# Grid.net
KiCad netlist of a schematic drawn in EAGLE
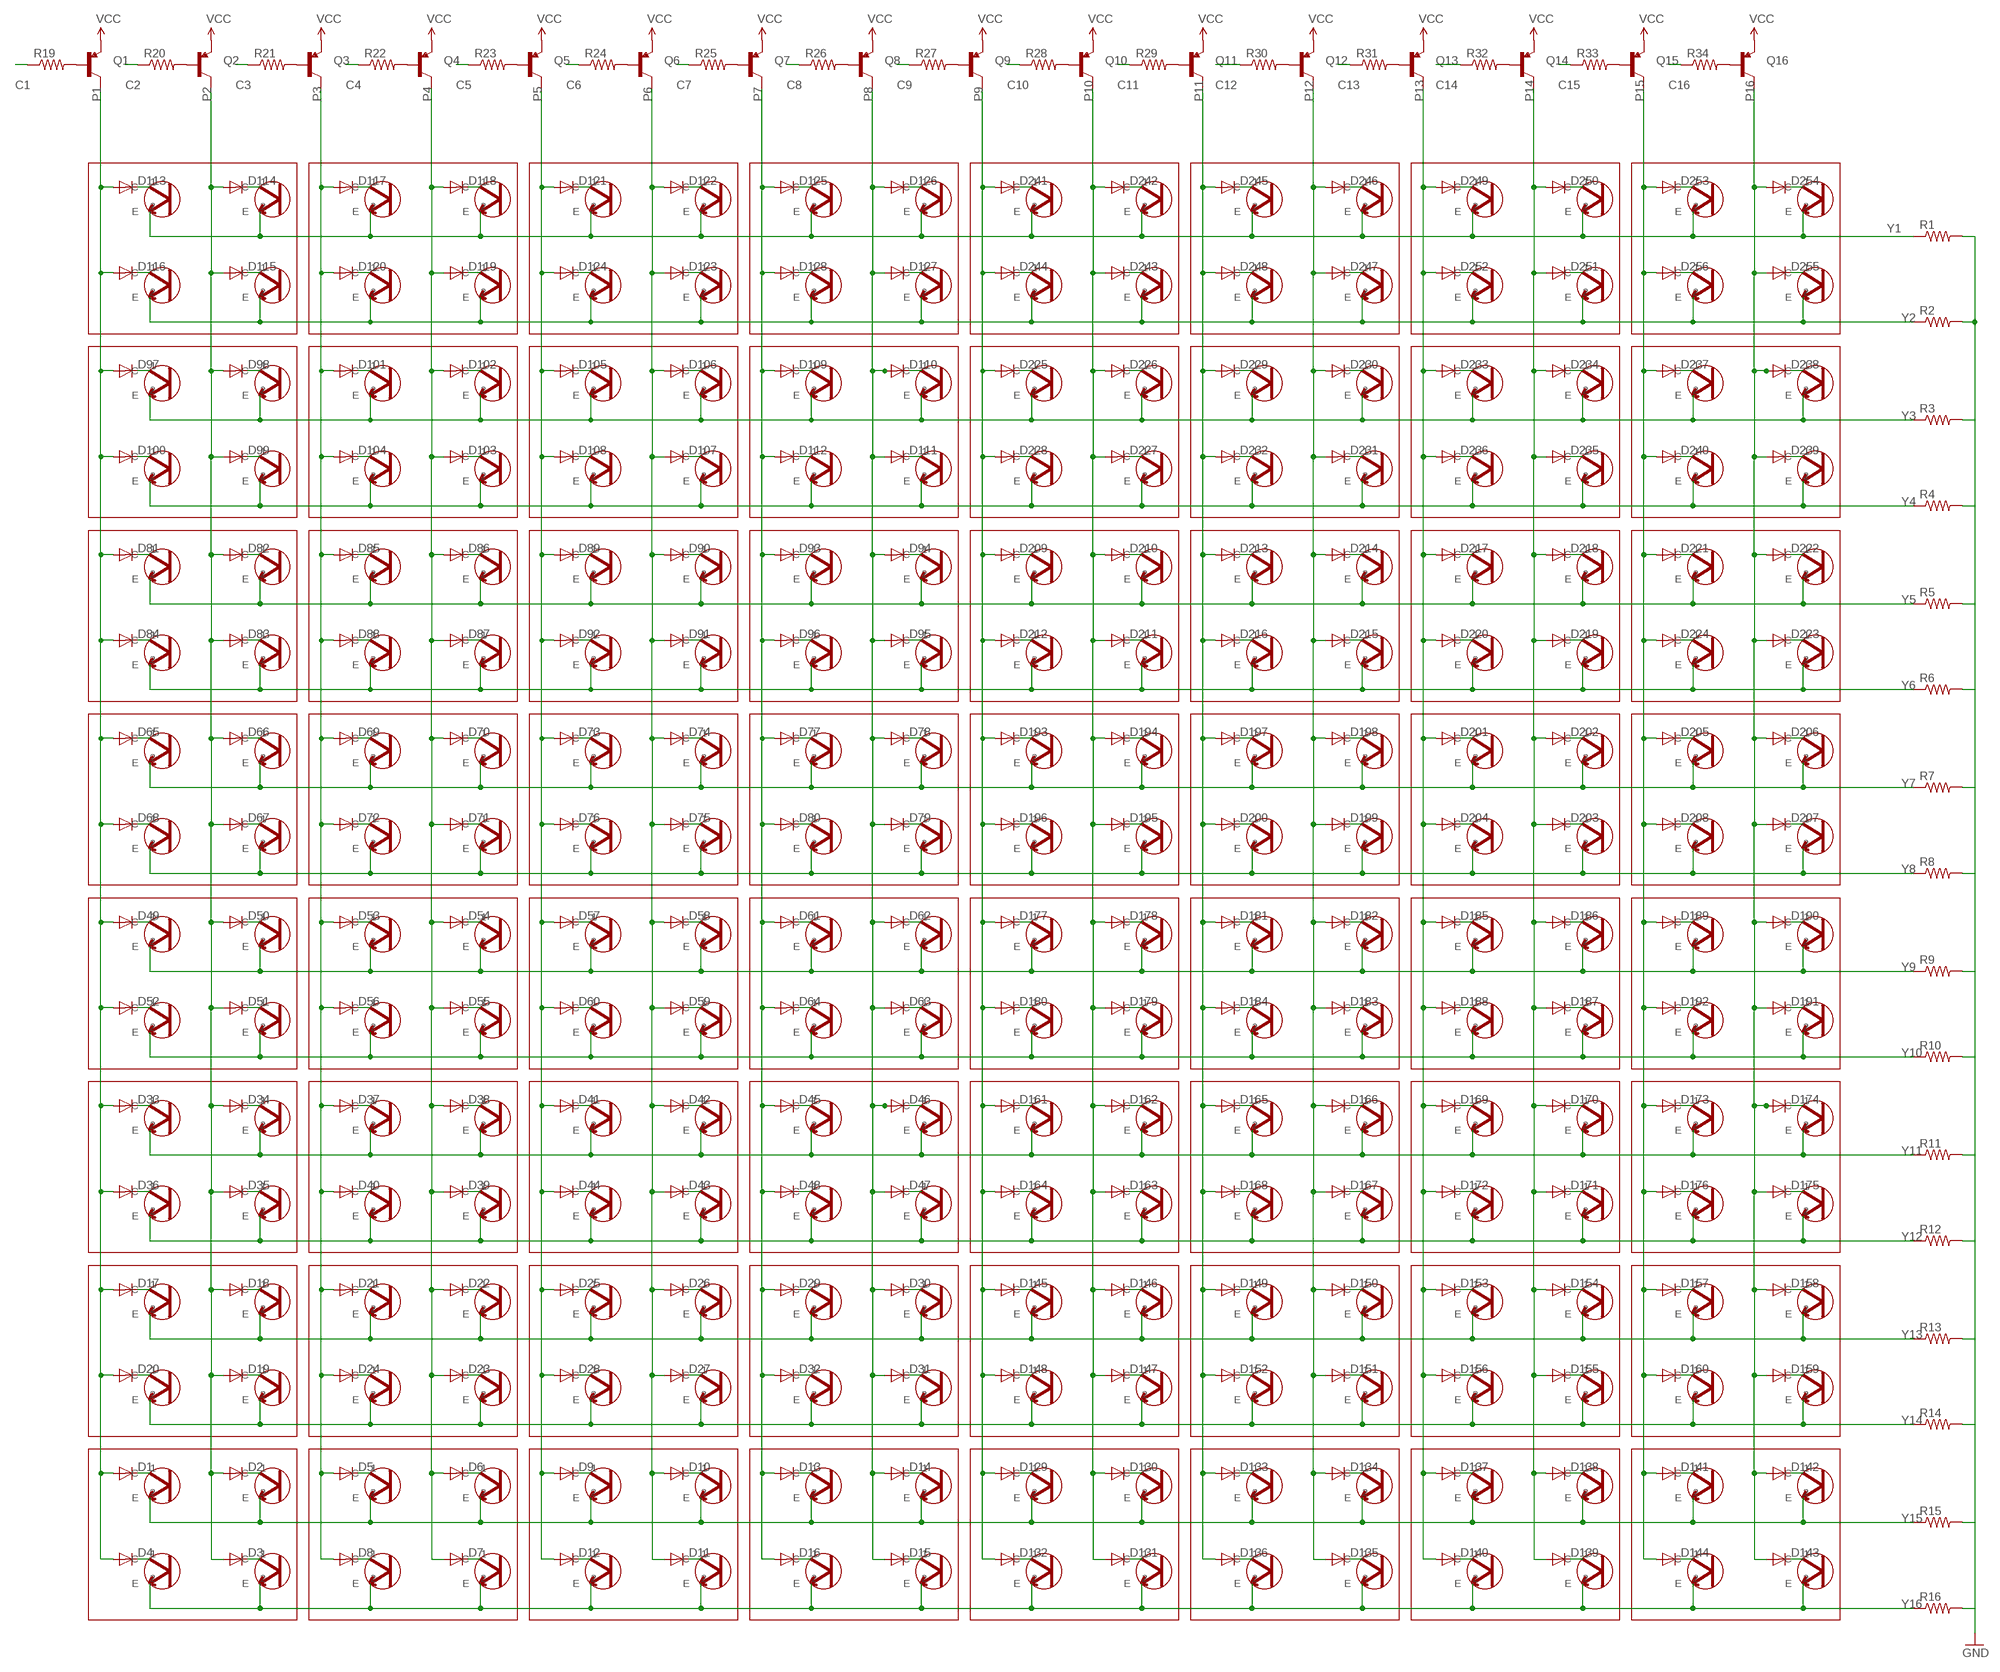
[diagram p0: schematic, sheet 1, part 1 of 2]
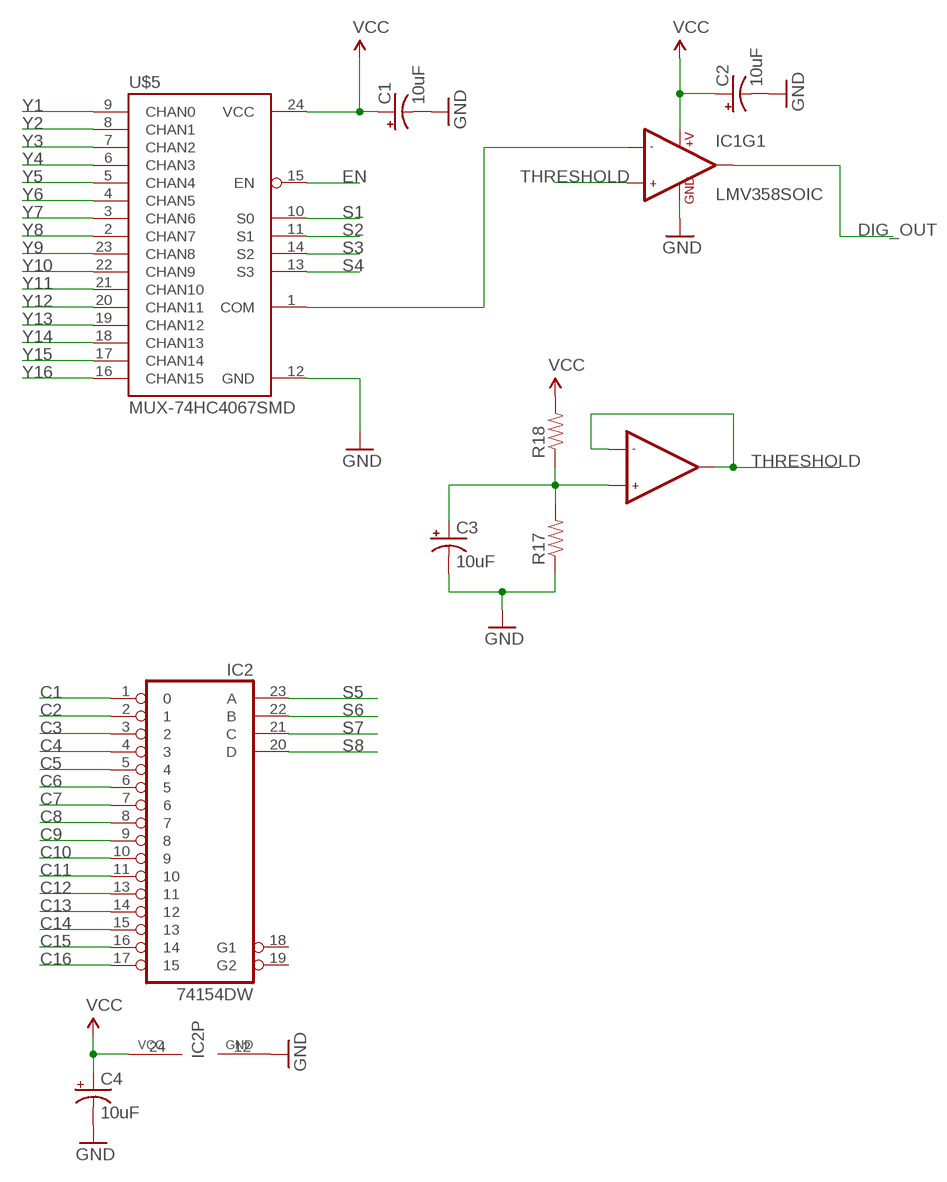
[diagram p1: schematic, sheet 1, part 2 of 2]

(export (version "E")
  (design (tool "Eeschema 10.0.6"))
  (components
    (comp (ref "C1")
      (value "10uF")
      (footprint "eagle-import:EIA3216")
      (libsource (lib "eagle-import") (part "CAP_POL1206"))
    )
    (comp (ref "C2")
      (value "10uF")
      (footprint "eagle-import:EIA3216")
      (libsource (lib "eagle-import") (part "CAP_POL1206"))
    )
    (comp (ref "C3")
      (value "10uF")
      (footprint "eagle-import:EIA3216")
      (libsource (lib "eagle-import") (part "CAP_POL1206"))
    )
    (comp (ref "C4")
      (value "10uF")
      (footprint "eagle-import:EIA3216")
      (libsource (lib "eagle-import") (part "CAP_POL1206"))
    )
    (comp (ref "D1")
      (value "DIODESOD")
      (footprint "eagle-import:SOD-323")
      (libsource (lib "eagle-import") (part "DIODESOD"))
    )
    (comp (ref "D2")
      (value "DIODESOD")
      (footprint "eagle-import:SOD-323")
      (libsource (lib "eagle-import") (part "DIODESOD"))
    )
    (comp (ref "D3")
      (value "DIODESOD")
      (footprint "eagle-import:SOD-323")
      (libsource (lib "eagle-import") (part "DIODESOD"))
    )
    (comp (ref "D4")
      (value "DIODESOD")
      (footprint "eagle-import:SOD-323")
      (libsource (lib "eagle-import") (part "DIODESOD"))
    )
    (comp (ref "D5")
      (value "DIODESOD")
      (footprint "eagle-import:SOD-323")
      (libsource (lib "eagle-import") (part "DIODESOD"))
    )
    (comp (ref "D6")
      (value "DIODESOD")
      (footprint "eagle-import:SOD-323")
      (libsource (lib "eagle-import") (part "DIODESOD"))
    )
    (comp (ref "D7")
      (value "DIODESOD")
      (footprint "eagle-import:SOD-323")
      (libsource (lib "eagle-import") (part "DIODESOD"))
    )
    (comp (ref "D8")
      (value "DIODESOD")
      (footprint "eagle-import:SOD-323")
      (libsource (lib "eagle-import") (part "DIODESOD"))
    )
    (comp (ref "D9")
      (value "DIODESOD")
      (footprint "eagle-import:SOD-323")
      (libsource (lib "eagle-import") (part "DIODESOD"))
    )
    (comp (ref "D10")
      (value "DIODESOD")
      (footprint "eagle-import:SOD-323")
      (libsource (lib "eagle-import") (part "DIODESOD"))
    )
    (comp (ref "D11")
      (value "DIODESOD")
      (footprint "eagle-import:SOD-323")
      (libsource (lib "eagle-import") (part "DIODESOD"))
    )
    (comp (ref "D12")
      (value "DIODESOD")
      (footprint "eagle-import:SOD-323")
      (libsource (lib "eagle-import") (part "DIODESOD"))
    )
    (comp (ref "D13")
      (value "DIODESOD")
      (footprint "eagle-import:SOD-323")
      (libsource (lib "eagle-import") (part "DIODESOD"))
    )
    (comp (ref "D14")
      (value "DIODESOD")
      (footprint "eagle-import:SOD-323")
      (libsource (lib "eagle-import") (part "DIODESOD"))
    )
    (comp (ref "D15")
      (value "DIODESOD")
      (footprint "eagle-import:SOD-323")
      (libsource (lib "eagle-import") (part "DIODESOD"))
    )
    (comp (ref "D16")
      (value "DIODESOD")
      (footprint "eagle-import:SOD-323")
      (libsource (lib "eagle-import") (part "DIODESOD"))
    )
    (comp (ref "D17")
      (value "DIODESOD")
      (footprint "eagle-import:SOD-323")
      (libsource (lib "eagle-import") (part "DIODESOD"))
    )
    (comp (ref "D18")
      (value "DIODESOD")
      (footprint "eagle-import:SOD-323")
      (libsource (lib "eagle-import") (part "DIODESOD"))
    )
    (comp (ref "D19")
      (value "DIODESOD")
      (footprint "eagle-import:SOD-323")
      (libsource (lib "eagle-import") (part "DIODESOD"))
    )
    (comp (ref "D20")
      (value "DIODESOD")
      (footprint "eagle-import:SOD-323")
      (libsource (lib "eagle-import") (part "DIODESOD"))
    )
    (comp (ref "D21")
      (value "DIODESOD")
      (footprint "eagle-import:SOD-323")
      (libsource (lib "eagle-import") (part "DIODESOD"))
    )
    (comp (ref "D22")
      (value "DIODESOD")
      (footprint "eagle-import:SOD-323")
      (libsource (lib "eagle-import") (part "DIODESOD"))
    )
    (comp (ref "D23")
      (value "DIODESOD")
      (footprint "eagle-import:SOD-323")
      (libsource (lib "eagle-import") (part "DIODESOD"))
    )
    (comp (ref "D24")
      (value "DIODESOD")
      (footprint "eagle-import:SOD-323")
      (libsource (lib "eagle-import") (part "DIODESOD"))
    )
    (comp (ref "D25")
      (value "DIODESOD")
      (footprint "eagle-import:SOD-323")
      (libsource (lib "eagle-import") (part "DIODESOD"))
    )
    (comp (ref "D26")
      (value "DIODESOD")
      (footprint "eagle-import:SOD-323")
      (libsource (lib "eagle-import") (part "DIODESOD"))
    )
    (comp (ref "D27")
      (value "DIODESOD")
      (footprint "eagle-import:SOD-323")
      (libsource (lib "eagle-import") (part "DIODESOD"))
    )
    (comp (ref "D28")
      (value "DIODESOD")
      (footprint "eagle-import:SOD-323")
      (libsource (lib "eagle-import") (part "DIODESOD"))
    )
    (comp (ref "D29")
      (value "DIODESOD")
      (footprint "eagle-import:SOD-323")
      (libsource (lib "eagle-import") (part "DIODESOD"))
    )
    (comp (ref "D30")
      (value "DIODESOD")
      (footprint "eagle-import:SOD-323")
      (libsource (lib "eagle-import") (part "DIODESOD"))
    )
    (comp (ref "D31")
      (value "DIODESOD")
      (footprint "eagle-import:SOD-323")
      (libsource (lib "eagle-import") (part "DIODESOD"))
    )
    (comp (ref "D32")
      (value "DIODESOD")
      (footprint "eagle-import:SOD-323")
      (libsource (lib "eagle-import") (part "DIODESOD"))
    )
    (comp (ref "D33")
      (value "DIODESOD")
      (footprint "eagle-import:SOD-323")
      (libsource (lib "eagle-import") (part "DIODESOD"))
    )
    (comp (ref "D34")
      (value "DIODESOD")
      (footprint "eagle-import:SOD-323")
      (libsource (lib "eagle-import") (part "DIODESOD"))
    )
    (comp (ref "D35")
      (value "DIODESOD")
      (footprint "eagle-import:SOD-323")
      (libsource (lib "eagle-import") (part "DIODESOD"))
    )
    (comp (ref "D36")
      (value "DIODESOD")
      (footprint "eagle-import:SOD-323")
      (libsource (lib "eagle-import") (part "DIODESOD"))
    )
    (comp (ref "D37")
      (value "DIODESOD")
      (footprint "eagle-import:SOD-323")
      (libsource (lib "eagle-import") (part "DIODESOD"))
    )
    (comp (ref "D38")
      (value "DIODESOD")
      (footprint "eagle-import:SOD-323")
      (libsource (lib "eagle-import") (part "DIODESOD"))
    )
    (comp (ref "D39")
      (value "DIODESOD")
      (footprint "eagle-import:SOD-323")
      (libsource (lib "eagle-import") (part "DIODESOD"))
    )
    (comp (ref "D40")
      (value "DIODESOD")
      (footprint "eagle-import:SOD-323")
      (libsource (lib "eagle-import") (part "DIODESOD"))
    )
    (comp (ref "D41")
      (value "DIODESOD")
      (footprint "eagle-import:SOD-323")
      (libsource (lib "eagle-import") (part "DIODESOD"))
    )
    (comp (ref "D42")
      (value "DIODESOD")
      (footprint "eagle-import:SOD-323")
      (libsource (lib "eagle-import") (part "DIODESOD"))
    )
    (comp (ref "D43")
      (value "DIODESOD")
      (footprint "eagle-import:SOD-323")
      (libsource (lib "eagle-import") (part "DIODESOD"))
    )
    (comp (ref "D44")
      (value "DIODESOD")
      (footprint "eagle-import:SOD-323")
      (libsource (lib "eagle-import") (part "DIODESOD"))
    )
    (comp (ref "D45")
      (value "DIODESOD")
      (footprint "eagle-import:SOD-323")
      (libsource (lib "eagle-import") (part "DIODESOD"))
    )
    (comp (ref "D46")
      (value "DIODESOD")
      (footprint "eagle-import:SOD-323")
      (libsource (lib "eagle-import") (part "DIODESOD"))
    )
    (comp (ref "D47")
      (value "DIODESOD")
      (footprint "eagle-import:SOD-323")
      (libsource (lib "eagle-import") (part "DIODESOD"))
    )
    (comp (ref "D48")
      (value "DIODESOD")
      (footprint "eagle-import:SOD-323")
      (libsource (lib "eagle-import") (part "DIODESOD"))
    )
    (comp (ref "D49")
      (value "DIODESOD")
      (footprint "eagle-import:SOD-323")
      (libsource (lib "eagle-import") (part "DIODESOD"))
    )
    (comp (ref "D50")
      (value "DIODESOD")
      (footprint "eagle-import:SOD-323")
      (libsource (lib "eagle-import") (part "DIODESOD"))
    )
    (comp (ref "D51")
      (value "DIODESOD")
      (footprint "eagle-import:SOD-323")
      (libsource (lib "eagle-import") (part "DIODESOD"))
    )
    (comp (ref "D52")
      (value "DIODESOD")
      (footprint "eagle-import:SOD-323")
      (libsource (lib "eagle-import") (part "DIODESOD"))
    )
    (comp (ref "D53")
      (value "DIODESOD")
      (footprint "eagle-import:SOD-323")
      (libsource (lib "eagle-import") (part "DIODESOD"))
    )
    (comp (ref "D54")
      (value "DIODESOD")
      (footprint "eagle-import:SOD-323")
      (libsource (lib "eagle-import") (part "DIODESOD"))
    )
    (comp (ref "D55")
      (value "DIODESOD")
      (footprint "eagle-import:SOD-323")
      (libsource (lib "eagle-import") (part "DIODESOD"))
    )
    (comp (ref "D56")
      (value "DIODESOD")
      (footprint "eagle-import:SOD-323")
      (libsource (lib "eagle-import") (part "DIODESOD"))
    )
    (comp (ref "D57")
      (value "DIODESOD")
      (footprint "eagle-import:SOD-323")
      (libsource (lib "eagle-import") (part "DIODESOD"))
    )
    (comp (ref "D58")
      (value "DIODESOD")
      (footprint "eagle-import:SOD-323")
      (libsource (lib "eagle-import") (part "DIODESOD"))
    )
    (comp (ref "D59")
      (value "DIODESOD")
      (footprint "eagle-import:SOD-323")
      (libsource (lib "eagle-import") (part "DIODESOD"))
    )
    (comp (ref "D60")
      (value "DIODESOD")
      (footprint "eagle-import:SOD-323")
      (libsource (lib "eagle-import") (part "DIODESOD"))
    )
    (comp (ref "D61")
      (value "DIODESOD")
      (footprint "eagle-import:SOD-323")
      (libsource (lib "eagle-import") (part "DIODESOD"))
    )
    (comp (ref "D62")
      (value "DIODESOD")
      (footprint "eagle-import:SOD-323")
      (libsource (lib "eagle-import") (part "DIODESOD"))
    )
    (comp (ref "D63")
      (value "DIODESOD")
      (footprint "eagle-import:SOD-323")
      (libsource (lib "eagle-import") (part "DIODESOD"))
    )
    (comp (ref "D64")
      (value "DIODESOD")
      (footprint "eagle-import:SOD-323")
      (libsource (lib "eagle-import") (part "DIODESOD"))
    )
    (comp (ref "D65")
      (value "DIODESOD")
      (footprint "eagle-import:SOD-323")
      (libsource (lib "eagle-import") (part "DIODESOD"))
    )
    (comp (ref "D66")
      (value "DIODESOD")
      (footprint "eagle-import:SOD-323")
      (libsource (lib "eagle-import") (part "DIODESOD"))
    )
    (comp (ref "D67")
      (value "DIODESOD")
      (footprint "eagle-import:SOD-323")
      (libsource (lib "eagle-import") (part "DIODESOD"))
    )
    (comp (ref "D68")
      (value "DIODESOD")
      (footprint "eagle-import:SOD-323")
      (libsource (lib "eagle-import") (part "DIODESOD"))
    )
    (comp (ref "D69")
      (value "DIODESOD")
      (footprint "eagle-import:SOD-323")
      (libsource (lib "eagle-import") (part "DIODESOD"))
    )
    (comp (ref "D70")
      (value "DIODESOD")
      (footprint "eagle-import:SOD-323")
      (libsource (lib "eagle-import") (part "DIODESOD"))
    )
    (comp (ref "D71")
      (value "DIODESOD")
      (footprint "eagle-import:SOD-323")
      (libsource (lib "eagle-import") (part "DIODESOD"))
    )
    (comp (ref "D72")
      (value "DIODESOD")
      (footprint "eagle-import:SOD-323")
      (libsource (lib "eagle-import") (part "DIODESOD"))
    )
    (comp (ref "D73")
      (value "DIODESOD")
      (footprint "eagle-import:SOD-323")
      (libsource (lib "eagle-import") (part "DIODESOD"))
    )
    (comp (ref "D74")
      (value "DIODESOD")
      (footprint "eagle-import:SOD-323")
      (libsource (lib "eagle-import") (part "DIODESOD"))
    )
    (comp (ref "D75")
      (value "DIODESOD")
      (footprint "eagle-import:SOD-323")
      (libsource (lib "eagle-import") (part "DIODESOD"))
    )
    (comp (ref "D76")
      (value "DIODESOD")
      (footprint "eagle-import:SOD-323")
      (libsource (lib "eagle-import") (part "DIODESOD"))
    )
    (comp (ref "D77")
      (value "DIODESOD")
      (footprint "eagle-import:SOD-323")
      (libsource (lib "eagle-import") (part "DIODESOD"))
    )
    (comp (ref "D78")
      (value "DIODESOD")
      (footprint "eagle-import:SOD-323")
      (libsource (lib "eagle-import") (part "DIODESOD"))
    )
    (comp (ref "D79")
      (value "DIODESOD")
      (footprint "eagle-import:SOD-323")
      (libsource (lib "eagle-import") (part "DIODESOD"))
    )
    (comp (ref "D80")
      (value "DIODESOD")
      (footprint "eagle-import:SOD-323")
      (libsource (lib "eagle-import") (part "DIODESOD"))
    )
    (comp (ref "D81")
      (value "DIODESOD")
      (footprint "eagle-import:SOD-323")
      (libsource (lib "eagle-import") (part "DIODESOD"))
    )
    (comp (ref "D82")
      (value "DIODESOD")
      (footprint "eagle-import:SOD-323")
      (libsource (lib "eagle-import") (part "DIODESOD"))
    )
    (comp (ref "D83")
      (value "DIODESOD")
      (footprint "eagle-import:SOD-323")
      (libsource (lib "eagle-import") (part "DIODESOD"))
    )
    (comp (ref "D84")
      (value "DIODESOD")
      (footprint "eagle-import:SOD-323")
      (libsource (lib "eagle-import") (part "DIODESOD"))
    )
    (comp (ref "D85")
      (value "DIODESOD")
      (footprint "eagle-import:SOD-323")
      (libsource (lib "eagle-import") (part "DIODESOD"))
    )
    (comp (ref "D86")
      (value "DIODESOD")
      (footprint "eagle-import:SOD-323")
      (libsource (lib "eagle-import") (part "DIODESOD"))
    )
    (comp (ref "D87")
      (value "DIODESOD")
      (footprint "eagle-import:SOD-323")
      (libsource (lib "eagle-import") (part "DIODESOD"))
    )
    (comp (ref "D88")
      (value "DIODESOD")
      (footprint "eagle-import:SOD-323")
      (libsource (lib "eagle-import") (part "DIODESOD"))
    )
    (comp (ref "D89")
      (value "DIODESOD")
      (footprint "eagle-import:SOD-323")
      (libsource (lib "eagle-import") (part "DIODESOD"))
    )
    (comp (ref "D90")
      (value "DIODESOD")
      (footprint "eagle-import:SOD-323")
      (libsource (lib "eagle-import") (part "DIODESOD"))
    )
    (comp (ref "D91")
      (value "DIODESOD")
      (footprint "eagle-import:SOD-323")
      (libsource (lib "eagle-import") (part "DIODESOD"))
    )
    (comp (ref "D92")
      (value "DIODESOD")
      (footprint "eagle-import:SOD-323")
      (libsource (lib "eagle-import") (part "DIODESOD"))
    )
    (comp (ref "D93")
      (value "DIODESOD")
      (footprint "eagle-import:SOD-323")
      (libsource (lib "eagle-import") (part "DIODESOD"))
    )
    (comp (ref "D94")
      (value "DIODESOD")
      (footprint "eagle-import:SOD-323")
      (libsource (lib "eagle-import") (part "DIODESOD"))
    )
    (comp (ref "D95")
      (value "DIODESOD")
      (footprint "eagle-import:SOD-323")
      (libsource (lib "eagle-import") (part "DIODESOD"))
    )
    (comp (ref "D96")
      (value "DIODESOD")
      (footprint "eagle-import:SOD-323")
      (libsource (lib "eagle-import") (part "DIODESOD"))
    )
    (comp (ref "D97")
      (value "DIODESOD")
      (footprint "eagle-import:SOD-323")
      (libsource (lib "eagle-import") (part "DIODESOD"))
    )
    (comp (ref "D98")
      (value "DIODESOD")
      (footprint "eagle-import:SOD-323")
      (libsource (lib "eagle-import") (part "DIODESOD"))
    )
    (comp (ref "D99")
      (value "DIODESOD")
      (footprint "eagle-import:SOD-323")
      (libsource (lib "eagle-import") (part "DIODESOD"))
    )
    (comp (ref "D100")
      (value "DIODESOD")
      (footprint "eagle-import:SOD-323")
      (libsource (lib "eagle-import") (part "DIODESOD"))
    )
    (comp (ref "D101")
      (value "DIODESOD")
      (footprint "eagle-import:SOD-323")
      (libsource (lib "eagle-import") (part "DIODESOD"))
    )
    (comp (ref "D102")
      (value "DIODESOD")
      (footprint "eagle-import:SOD-323")
      (libsource (lib "eagle-import") (part "DIODESOD"))
    )
    (comp (ref "D103")
      (value "DIODESOD")
      (footprint "eagle-import:SOD-323")
      (libsource (lib "eagle-import") (part "DIODESOD"))
    )
    (comp (ref "D104")
      (value "DIODESOD")
      (footprint "eagle-import:SOD-323")
      (libsource (lib "eagle-import") (part "DIODESOD"))
    )
    (comp (ref "D105")
      (value "DIODESOD")
      (footprint "eagle-import:SOD-323")
      (libsource (lib "eagle-import") (part "DIODESOD"))
    )
    (comp (ref "D106")
      (value "DIODESOD")
      (footprint "eagle-import:SOD-323")
      (libsource (lib "eagle-import") (part "DIODESOD"))
    )
    (comp (ref "D107")
      (value "DIODESOD")
      (footprint "eagle-import:SOD-323")
      (libsource (lib "eagle-import") (part "DIODESOD"))
    )
    (comp (ref "D108")
      (value "DIODESOD")
      (footprint "eagle-import:SOD-323")
      (libsource (lib "eagle-import") (part "DIODESOD"))
    )
    (comp (ref "D109")
      (value "DIODESOD")
      (footprint "eagle-import:SOD-323")
      (libsource (lib "eagle-import") (part "DIODESOD"))
    )
    (comp (ref "D110")
      (value "DIODESOD")
      (footprint "eagle-import:SOD-323")
      (libsource (lib "eagle-import") (part "DIODESOD"))
    )
    (comp (ref "D111")
      (value "DIODESOD")
      (footprint "eagle-import:SOD-323")
      (libsource (lib "eagle-import") (part "DIODESOD"))
    )
    (comp (ref "D112")
      (value "DIODESOD")
      (footprint "eagle-import:SOD-323")
      (libsource (lib "eagle-import") (part "DIODESOD"))
    )
    (comp (ref "D113")
      (value "DIODESOD")
      (footprint "eagle-import:SOD-323")
      (libsource (lib "eagle-import") (part "DIODESOD"))
    )
    (comp (ref "D114")
      (value "DIODESOD")
      (footprint "eagle-import:SOD-323")
      (libsource (lib "eagle-import") (part "DIODESOD"))
    )
    (comp (ref "D115")
      (value "DIODESOD")
      (footprint "eagle-import:SOD-323")
      (libsource (lib "eagle-import") (part "DIODESOD"))
    )
    (comp (ref "D116")
      (value "DIODESOD")
      (footprint "eagle-import:SOD-323")
      (libsource (lib "eagle-import") (part "DIODESOD"))
    )
    (comp (ref "D117")
      (value "DIODESOD")
      (footprint "eagle-import:SOD-323")
      (libsource (lib "eagle-import") (part "DIODESOD"))
    )
    (comp (ref "D118")
      (value "DIODESOD")
      (footprint "eagle-import:SOD-323")
      (libsource (lib "eagle-import") (part "DIODESOD"))
    )
    (comp (ref "D119")
      (value "DIODESOD")
      (footprint "eagle-import:SOD-323")
      (libsource (lib "eagle-import") (part "DIODESOD"))
    )
    (comp (ref "D120")
      (value "DIODESOD")
      (footprint "eagle-import:SOD-323")
      (libsource (lib "eagle-import") (part "DIODESOD"))
    )
    (comp (ref "D121")
      (value "DIODESOD")
      (footprint "eagle-import:SOD-323")
      (libsource (lib "eagle-import") (part "DIODESOD"))
    )
    (comp (ref "D122")
      (value "DIODESOD")
      (footprint "eagle-import:SOD-323")
      (libsource (lib "eagle-import") (part "DIODESOD"))
    )
    (comp (ref "D123")
      (value "DIODESOD")
      (footprint "eagle-import:SOD-323")
      (libsource (lib "eagle-import") (part "DIODESOD"))
    )
    (comp (ref "D124")
      (value "DIODESOD")
      (footprint "eagle-import:SOD-323")
      (libsource (lib "eagle-import") (part "DIODESOD"))
    )
    (comp (ref "D125")
      (value "DIODESOD")
      (footprint "eagle-import:SOD-323")
      (libsource (lib "eagle-import") (part "DIODESOD"))
    )
    (comp (ref "D126")
      (value "DIODESOD")
      (footprint "eagle-import:SOD-323")
      (libsource (lib "eagle-import") (part "DIODESOD"))
    )
    (comp (ref "D127")
      (value "DIODESOD")
      (footprint "eagle-import:SOD-323")
      (libsource (lib "eagle-import") (part "DIODESOD"))
    )
    (comp (ref "D128")
      (value "DIODESOD")
      (footprint "eagle-import:SOD-323")
      (libsource (lib "eagle-import") (part "DIODESOD"))
    )
    (comp (ref "D129")
      (value "DIODESOD")
      (footprint "eagle-import:SOD-323")
      (libsource (lib "eagle-import") (part "DIODESOD"))
    )
    (comp (ref "D130")
      (value "DIODESOD")
      (footprint "eagle-import:SOD-323")
      (libsource (lib "eagle-import") (part "DIODESOD"))
    )
    (comp (ref "D131")
      (value "DIODESOD")
      (footprint "eagle-import:SOD-323")
      (libsource (lib "eagle-import") (part "DIODESOD"))
    )
    (comp (ref "D132")
      (value "DIODESOD")
      (footprint "eagle-import:SOD-323")
      (libsource (lib "eagle-import") (part "DIODESOD"))
    )
    (comp (ref "D133")
      (value "DIODESOD")
      (footprint "eagle-import:SOD-323")
      (libsource (lib "eagle-import") (part "DIODESOD"))
    )
    (comp (ref "D134")
      (value "DIODESOD")
      (footprint "eagle-import:SOD-323")
      (libsource (lib "eagle-import") (part "DIODESOD"))
    )
    (comp (ref "D135")
      (value "DIODESOD")
      (footprint "eagle-import:SOD-323")
      (libsource (lib "eagle-import") (part "DIODESOD"))
    )
    (comp (ref "D136")
      (value "DIODESOD")
      (footprint "eagle-import:SOD-323")
      (libsource (lib "eagle-import") (part "DIODESOD"))
    )
    (comp (ref "D137")
      (value "DIODESOD")
      (footprint "eagle-import:SOD-323")
      (libsource (lib "eagle-import") (part "DIODESOD"))
    )
    (comp (ref "D138")
      (value "DIODESOD")
      (footprint "eagle-import:SOD-323")
      (libsource (lib "eagle-import") (part "DIODESOD"))
    )
    (comp (ref "D139")
      (value "DIODESOD")
      (footprint "eagle-import:SOD-323")
      (libsource (lib "eagle-import") (part "DIODESOD"))
    )
    (comp (ref "D140")
      (value "DIODESOD")
      (footprint "eagle-import:SOD-323")
      (libsource (lib "eagle-import") (part "DIODESOD"))
    )
    (comp (ref "D141")
      (value "DIODESOD")
      (footprint "eagle-import:SOD-323")
      (libsource (lib "eagle-import") (part "DIODESOD"))
    )
    (comp (ref "D142")
      (value "DIODESOD")
      (footprint "eagle-import:SOD-323")
      (libsource (lib "eagle-import") (part "DIODESOD"))
    )
    (comp (ref "D143")
      (value "DIODESOD")
      (footprint "eagle-import:SOD-323")
      (libsource (lib "eagle-import") (part "DIODESOD"))
    )
    (comp (ref "D144")
      (value "DIODESOD")
      (footprint "eagle-import:SOD-323")
      (libsource (lib "eagle-import") (part "DIODESOD"))
    )
    (comp (ref "D145")
      (value "DIODESOD")
      (footprint "eagle-import:SOD-323")
      (libsource (lib "eagle-import") (part "DIODESOD"))
    )
    (comp (ref "D146")
      (value "DIODESOD")
      (footprint "eagle-import:SOD-323")
      (libsource (lib "eagle-import") (part "DIODESOD"))
    )
    (comp (ref "D147")
      (value "DIODESOD")
      (footprint "eagle-import:SOD-323")
      (libsource (lib "eagle-import") (part "DIODESOD"))
    )
    (comp (ref "D148")
      (value "DIODESOD")
      (footprint "eagle-import:SOD-323")
      (libsource (lib "eagle-import") (part "DIODESOD"))
    )
    (comp (ref "D149")
      (value "DIODESOD")
      (footprint "eagle-import:SOD-323")
      (libsource (lib "eagle-import") (part "DIODESOD"))
    )
    (comp (ref "D150")
      (value "DIODESOD")
      (footprint "eagle-import:SOD-323")
      (libsource (lib "eagle-import") (part "DIODESOD"))
    )
    (comp (ref "D151")
      (value "DIODESOD")
      (footprint "eagle-import:SOD-323")
      (libsource (lib "eagle-import") (part "DIODESOD"))
    )
    (comp (ref "D152")
      (value "DIODESOD")
      (footprint "eagle-import:SOD-323")
      (libsource (lib "eagle-import") (part "DIODESOD"))
    )
    (comp (ref "D153")
      (value "DIODESOD")
      (footprint "eagle-import:SOD-323")
      (libsource (lib "eagle-import") (part "DIODESOD"))
    )
    (comp (ref "D154")
      (value "DIODESOD")
      (footprint "eagle-import:SOD-323")
      (libsource (lib "eagle-import") (part "DIODESOD"))
    )
    (comp (ref "D155")
      (value "DIODESOD")
      (footprint "eagle-import:SOD-323")
      (libsource (lib "eagle-import") (part "DIODESOD"))
    )
    (comp (ref "D156")
      (value "DIODESOD")
      (footprint "eagle-import:SOD-323")
      (libsource (lib "eagle-import") (part "DIODESOD"))
    )
    (comp (ref "D157")
      (value "DIODESOD")
      (footprint "eagle-import:SOD-323")
      (libsource (lib "eagle-import") (part "DIODESOD"))
    )
    (comp (ref "D158")
      (value "DIODESOD")
      (footprint "eagle-import:SOD-323")
      (libsource (lib "eagle-import") (part "DIODESOD"))
    )
    (comp (ref "D159")
      (value "DIODESOD")
      (footprint "eagle-import:SOD-323")
      (libsource (lib "eagle-import") (part "DIODESOD"))
    )
    (comp (ref "D160")
      (value "DIODESOD")
      (footprint "eagle-import:SOD-323")
      (libsource (lib "eagle-import") (part "DIODESOD"))
    )
    (comp (ref "D161")
      (value "DIODESOD")
      (footprint "eagle-import:SOD-323")
      (libsource (lib "eagle-import") (part "DIODESOD"))
    )
    (comp (ref "D162")
      (value "DIODESOD")
      (footprint "eagle-import:SOD-323")
      (libsource (lib "eagle-import") (part "DIODESOD"))
    )
    (comp (ref "D163")
      (value "DIODESOD")
      (footprint "eagle-import:SOD-323")
      (libsource (lib "eagle-import") (part "DIODESOD"))
    )
    (comp (ref "D164")
      (value "DIODESOD")
      (footprint "eagle-import:SOD-323")
      (libsource (lib "eagle-import") (part "DIODESOD"))
    )
    (comp (ref "D165")
      (value "DIODESOD")
      (footprint "eagle-import:SOD-323")
      (libsource (lib "eagle-import") (part "DIODESOD"))
    )
    (comp (ref "D166")
      (value "DIODESOD")
      (footprint "eagle-import:SOD-323")
      (libsource (lib "eagle-import") (part "DIODESOD"))
    )
    (comp (ref "D167")
      (value "DIODESOD")
      (footprint "eagle-import:SOD-323")
      (libsource (lib "eagle-import") (part "DIODESOD"))
    )
    (comp (ref "D168")
      (value "DIODESOD")
      (footprint "eagle-import:SOD-323")
      (libsource (lib "eagle-import") (part "DIODESOD"))
    )
    (comp (ref "D169")
      (value "DIODESOD")
      (footprint "eagle-import:SOD-323")
      (libsource (lib "eagle-import") (part "DIODESOD"))
    )
    (comp (ref "D170")
      (value "DIODESOD")
      (footprint "eagle-import:SOD-323")
      (libsource (lib "eagle-import") (part "DIODESOD"))
    )
    (comp (ref "D171")
      (value "DIODESOD")
      (footprint "eagle-import:SOD-323")
      (libsource (lib "eagle-import") (part "DIODESOD"))
    )
    (comp (ref "D172")
      (value "DIODESOD")
      (footprint "eagle-import:SOD-323")
      (libsource (lib "eagle-import") (part "DIODESOD"))
    )
    (comp (ref "D173")
      (value "DIODESOD")
      (footprint "eagle-import:SOD-323")
      (libsource (lib "eagle-import") (part "DIODESOD"))
    )
    (comp (ref "D174")
      (value "DIODESOD")
      (footprint "eagle-import:SOD-323")
      (libsource (lib "eagle-import") (part "DIODESOD"))
    )
    (comp (ref "D175")
      (value "DIODESOD")
      (footprint "eagle-import:SOD-323")
      (libsource (lib "eagle-import") (part "DIODESOD"))
    )
    (comp (ref "D176")
      (value "DIODESOD")
      (footprint "eagle-import:SOD-323")
      (libsource (lib "eagle-import") (part "DIODESOD"))
    )
    (comp (ref "D177")
      (value "DIODESOD")
      (footprint "eagle-import:SOD-323")
      (libsource (lib "eagle-import") (part "DIODESOD"))
    )
    (comp (ref "D178")
      (value "DIODESOD")
      (footprint "eagle-import:SOD-323")
      (libsource (lib "eagle-import") (part "DIODESOD"))
    )
    (comp (ref "D179")
      (value "DIODESOD")
      (footprint "eagle-import:SOD-323")
      (libsource (lib "eagle-import") (part "DIODESOD"))
    )
    (comp (ref "D180")
      (value "DIODESOD")
      (footprint "eagle-import:SOD-323")
      (libsource (lib "eagle-import") (part "DIODESOD"))
    )
    (comp (ref "D181")
      (value "DIODESOD")
      (footprint "eagle-import:SOD-323")
      (libsource (lib "eagle-import") (part "DIODESOD"))
    )
    (comp (ref "D182")
      (value "DIODESOD")
      (footprint "eagle-import:SOD-323")
      (libsource (lib "eagle-import") (part "DIODESOD"))
    )
    (comp (ref "D183")
      (value "DIODESOD")
      (footprint "eagle-import:SOD-323")
      (libsource (lib "eagle-import") (part "DIODESOD"))
    )
    (comp (ref "D184")
      (value "DIODESOD")
      (footprint "eagle-import:SOD-323")
      (libsource (lib "eagle-import") (part "DIODESOD"))
    )
    (comp (ref "D185")
      (value "DIODESOD")
      (footprint "eagle-import:SOD-323")
      (libsource (lib "eagle-import") (part "DIODESOD"))
    )
    (comp (ref "D186")
      (value "DIODESOD")
      (footprint "eagle-import:SOD-323")
      (libsource (lib "eagle-import") (part "DIODESOD"))
    )
    (comp (ref "D187")
      (value "DIODESOD")
      (footprint "eagle-import:SOD-323")
      (libsource (lib "eagle-import") (part "DIODESOD"))
    )
    (comp (ref "D188")
      (value "DIODESOD")
      (footprint "eagle-import:SOD-323")
      (libsource (lib "eagle-import") (part "DIODESOD"))
    )
    (comp (ref "D189")
      (value "DIODESOD")
      (footprint "eagle-import:SOD-323")
      (libsource (lib "eagle-import") (part "DIODESOD"))
    )
    (comp (ref "D190")
      (value "DIODESOD")
      (footprint "eagle-import:SOD-323")
      (libsource (lib "eagle-import") (part "DIODESOD"))
    )
    (comp (ref "D191")
      (value "DIODESOD")
      (footprint "eagle-import:SOD-323")
      (libsource (lib "eagle-import") (part "DIODESOD"))
    )
    (comp (ref "D192")
      (value "DIODESOD")
      (footprint "eagle-import:SOD-323")
      (libsource (lib "eagle-import") (part "DIODESOD"))
    )
    (comp (ref "D193")
      (value "DIODESOD")
      (footprint "eagle-import:SOD-323")
      (libsource (lib "eagle-import") (part "DIODESOD"))
    )
    (comp (ref "D194")
      (value "DIODESOD")
      (footprint "eagle-import:SOD-323")
      (libsource (lib "eagle-import") (part "DIODESOD"))
    )
    (comp (ref "D195")
      (value "DIODESOD")
      (footprint "eagle-import:SOD-323")
      (libsource (lib "eagle-import") (part "DIODESOD"))
    )
    (comp (ref "D196")
      (value "DIODESOD")
      (footprint "eagle-import:SOD-323")
      (libsource (lib "eagle-import") (part "DIODESOD"))
    )
    (comp (ref "D197")
      (value "DIODESOD")
      (footprint "eagle-import:SOD-323")
      (libsource (lib "eagle-import") (part "DIODESOD"))
    )
    (comp (ref "D198")
      (value "DIODESOD")
      (footprint "eagle-import:SOD-323")
      (libsource (lib "eagle-import") (part "DIODESOD"))
    )
    (comp (ref "D199")
      (value "DIODESOD")
      (footprint "eagle-import:SOD-323")
      (libsource (lib "eagle-import") (part "DIODESOD"))
    )
    (comp (ref "D200")
      (value "DIODESOD")
      (footprint "eagle-import:SOD-323")
      (libsource (lib "eagle-import") (part "DIODESOD"))
    )
    (comp (ref "D201")
      (value "DIODESOD")
      (footprint "eagle-import:SOD-323")
      (libsource (lib "eagle-import") (part "DIODESOD"))
    )
    (comp (ref "D202")
      (value "DIODESOD")
      (footprint "eagle-import:SOD-323")
      (libsource (lib "eagle-import") (part "DIODESOD"))
    )
    (comp (ref "D203")
      (value "DIODESOD")
      (footprint "eagle-import:SOD-323")
      (libsource (lib "eagle-import") (part "DIODESOD"))
    )
    (comp (ref "D204")
      (value "DIODESOD")
      (footprint "eagle-import:SOD-323")
      (libsource (lib "eagle-import") (part "DIODESOD"))
    )
    (comp (ref "D205")
      (value "DIODESOD")
      (footprint "eagle-import:SOD-323")
      (libsource (lib "eagle-import") (part "DIODESOD"))
    )
    (comp (ref "D206")
      (value "DIODESOD")
      (footprint "eagle-import:SOD-323")
      (libsource (lib "eagle-import") (part "DIODESOD"))
    )
    (comp (ref "D207")
      (value "DIODESOD")
      (footprint "eagle-import:SOD-323")
      (libsource (lib "eagle-import") (part "DIODESOD"))
    )
    (comp (ref "D208")
      (value "DIODESOD")
      (footprint "eagle-import:SOD-323")
      (libsource (lib "eagle-import") (part "DIODESOD"))
    )
    (comp (ref "D209")
      (value "DIODESOD")
      (footprint "eagle-import:SOD-323")
      (libsource (lib "eagle-import") (part "DIODESOD"))
    )
    (comp (ref "D210")
      (value "DIODESOD")
      (footprint "eagle-import:SOD-323")
      (libsource (lib "eagle-import") (part "DIODESOD"))
    )
    (comp (ref "D211")
      (value "DIODESOD")
      (footprint "eagle-import:SOD-323")
      (libsource (lib "eagle-import") (part "DIODESOD"))
    )
    (comp (ref "D212")
      (value "DIODESOD")
      (footprint "eagle-import:SOD-323")
      (libsource (lib "eagle-import") (part "DIODESOD"))
    )
    (comp (ref "D213")
      (value "DIODESOD")
      (footprint "eagle-import:SOD-323")
      (libsource (lib "eagle-import") (part "DIODESOD"))
    )
    (comp (ref "D214")
      (value "DIODESOD")
      (footprint "eagle-import:SOD-323")
      (libsource (lib "eagle-import") (part "DIODESOD"))
    )
    (comp (ref "D215")
      (value "DIODESOD")
      (footprint "eagle-import:SOD-323")
      (libsource (lib "eagle-import") (part "DIODESOD"))
    )
    (comp (ref "D216")
      (value "DIODESOD")
      (footprint "eagle-import:SOD-323")
      (libsource (lib "eagle-import") (part "DIODESOD"))
    )
    (comp (ref "D217")
      (value "DIODESOD")
      (footprint "eagle-import:SOD-323")
      (libsource (lib "eagle-import") (part "DIODESOD"))
    )
    (comp (ref "D218")
      (value "DIODESOD")
      (footprint "eagle-import:SOD-323")
      (libsource (lib "eagle-import") (part "DIODESOD"))
    )
    (comp (ref "D219")
      (value "DIODESOD")
      (footprint "eagle-import:SOD-323")
      (libsource (lib "eagle-import") (part "DIODESOD"))
    )
    (comp (ref "D220")
      (value "DIODESOD")
      (footprint "eagle-import:SOD-323")
      (libsource (lib "eagle-import") (part "DIODESOD"))
    )
    (comp (ref "D221")
      (value "DIODESOD")
      (footprint "eagle-import:SOD-323")
      (libsource (lib "eagle-import") (part "DIODESOD"))
    )
    (comp (ref "D222")
      (value "DIODESOD")
      (footprint "eagle-import:SOD-323")
      (libsource (lib "eagle-import") (part "DIODESOD"))
    )
    (comp (ref "D223")
      (value "DIODESOD")
      (footprint "eagle-import:SOD-323")
      (libsource (lib "eagle-import") (part "DIODESOD"))
    )
    (comp (ref "D224")
      (value "DIODESOD")
      (footprint "eagle-import:SOD-323")
      (libsource (lib "eagle-import") (part "DIODESOD"))
    )
    (comp (ref "D225")
      (value "DIODESOD")
      (footprint "eagle-import:SOD-323")
      (libsource (lib "eagle-import") (part "DIODESOD"))
    )
    (comp (ref "D226")
      (value "DIODESOD")
      (footprint "eagle-import:SOD-323")
      (libsource (lib "eagle-import") (part "DIODESOD"))
    )
    (comp (ref "D227")
      (value "DIODESOD")
      (footprint "eagle-import:SOD-323")
      (libsource (lib "eagle-import") (part "DIODESOD"))
    )
    (comp (ref "D228")
      (value "DIODESOD")
      (footprint "eagle-import:SOD-323")
      (libsource (lib "eagle-import") (part "DIODESOD"))
    )
    (comp (ref "D229")
      (value "DIODESOD")
      (footprint "eagle-import:SOD-323")
      (libsource (lib "eagle-import") (part "DIODESOD"))
    )
    (comp (ref "D230")
      (value "DIODESOD")
      (footprint "eagle-import:SOD-323")
      (libsource (lib "eagle-import") (part "DIODESOD"))
    )
    (comp (ref "D231")
      (value "DIODESOD")
      (footprint "eagle-import:SOD-323")
      (libsource (lib "eagle-import") (part "DIODESOD"))
    )
    (comp (ref "D232")
      (value "DIODESOD")
      (footprint "eagle-import:SOD-323")
      (libsource (lib "eagle-import") (part "DIODESOD"))
    )
    (comp (ref "D233")
      (value "DIODESOD")
      (footprint "eagle-import:SOD-323")
      (libsource (lib "eagle-import") (part "DIODESOD"))
    )
    (comp (ref "D234")
      (value "DIODESOD")
      (footprint "eagle-import:SOD-323")
      (libsource (lib "eagle-import") (part "DIODESOD"))
    )
    (comp (ref "D235")
      (value "DIODESOD")
      (footprint "eagle-import:SOD-323")
      (libsource (lib "eagle-import") (part "DIODESOD"))
    )
    (comp (ref "D236")
      (value "DIODESOD")
      (footprint "eagle-import:SOD-323")
      (libsource (lib "eagle-import") (part "DIODESOD"))
    )
    (comp (ref "D237")
      (value "DIODESOD")
      (footprint "eagle-import:SOD-323")
      (libsource (lib "eagle-import") (part "DIODESOD"))
    )
    (comp (ref "D238")
      (value "DIODESOD")
      (footprint "eagle-import:SOD-323")
      (libsource (lib "eagle-import") (part "DIODESOD"))
    )
    (comp (ref "D239")
      (value "DIODESOD")
      (footprint "eagle-import:SOD-323")
      (libsource (lib "eagle-import") (part "DIODESOD"))
    )
    (comp (ref "D240")
      (value "DIODESOD")
      (footprint "eagle-import:SOD-323")
      (libsource (lib "eagle-import") (part "DIODESOD"))
    )
    (comp (ref "D241")
      (value "DIODESOD")
      (footprint "eagle-import:SOD-323")
      (libsource (lib "eagle-import") (part "DIODESOD"))
    )
    (comp (ref "D242")
      (value "DIODESOD")
      (footprint "eagle-import:SOD-323")
      (libsource (lib "eagle-import") (part "DIODESOD"))
    )
    (comp (ref "D243")
      (value "DIODESOD")
      (footprint "eagle-import:SOD-323")
      (libsource (lib "eagle-import") (part "DIODESOD"))
    )
    (comp (ref "D244")
      (value "DIODESOD")
      (footprint "eagle-import:SOD-323")
      (libsource (lib "eagle-import") (part "DIODESOD"))
    )
    (comp (ref "D245")
      (value "DIODESOD")
      (footprint "eagle-import:SOD-323")
      (libsource (lib "eagle-import") (part "DIODESOD"))
    )
    (comp (ref "D246")
      (value "DIODESOD")
      (footprint "eagle-import:SOD-323")
      (libsource (lib "eagle-import") (part "DIODESOD"))
    )
    (comp (ref "D247")
      (value "DIODESOD")
      (footprint "eagle-import:SOD-323")
      (libsource (lib "eagle-import") (part "DIODESOD"))
    )
    (comp (ref "D248")
      (value "DIODESOD")
      (footprint "eagle-import:SOD-323")
      (libsource (lib "eagle-import") (part "DIODESOD"))
    )
    (comp (ref "D249")
      (value "DIODESOD")
      (footprint "eagle-import:SOD-323")
      (libsource (lib "eagle-import") (part "DIODESOD"))
    )
    (comp (ref "D250")
      (value "DIODESOD")
      (footprint "eagle-import:SOD-323")
      (libsource (lib "eagle-import") (part "DIODESOD"))
    )
    (comp (ref "D251")
      (value "DIODESOD")
      (footprint "eagle-import:SOD-323")
      (libsource (lib "eagle-import") (part "DIODESOD"))
    )
    (comp (ref "D252")
      (value "DIODESOD")
      (footprint "eagle-import:SOD-323")
      (libsource (lib "eagle-import") (part "DIODESOD"))
    )
    (comp (ref "D253")
      (value "DIODESOD")
      (footprint "eagle-import:SOD-323")
      (libsource (lib "eagle-import") (part "DIODESOD"))
    )
    (comp (ref "D254")
      (value "DIODESOD")
      (footprint "eagle-import:SOD-323")
      (libsource (lib "eagle-import") (part "DIODESOD"))
    )
    (comp (ref "D255")
      (value "DIODESOD")
      (footprint "eagle-import:SOD-323")
      (libsource (lib "eagle-import") (part "DIODESOD"))
    )
    (comp (ref "D256")
      (value "DIODESOD")
      (footprint "eagle-import:SOD-323")
      (libsource (lib "eagle-import") (part "DIODESOD"))
    )
    (comp (ref "IC1")
      (value "LMV358SOIC")
      (footprint "eagle-import:SO08")
      (libsource (lib "eagle-import") (part "LMV358SOIC"))
    )
    (comp (ref "IC2")
      (value "74154DW")
      (footprint "eagle-import:SO24W")
      (libsource (lib "eagle-import") (part "74154DW"))
    )
    (comp (ref "Q1")
      (value "TRANSISTOR_PNPSMD")
      (footprint "eagle-import:SOT23-3")
      (libsource (lib "eagle-import") (part "TRANSISTOR_PNPSMD"))
    )
    (comp (ref "Q2")
      (value "TRANSISTOR_PNPSMD")
      (footprint "eagle-import:SOT23-3")
      (libsource (lib "eagle-import") (part "TRANSISTOR_PNPSMD"))
    )
    (comp (ref "Q3")
      (value "TRANSISTOR_PNPSMD")
      (footprint "eagle-import:SOT23-3")
      (libsource (lib "eagle-import") (part "TRANSISTOR_PNPSMD"))
    )
    (comp (ref "Q4")
      (value "TRANSISTOR_PNPSMD")
      (footprint "eagle-import:SOT23-3")
      (libsource (lib "eagle-import") (part "TRANSISTOR_PNPSMD"))
    )
    (comp (ref "Q5")
      (value "TRANSISTOR_PNPSMD")
      (footprint "eagle-import:SOT23-3")
      (libsource (lib "eagle-import") (part "TRANSISTOR_PNPSMD"))
    )
    (comp (ref "Q6")
      (value "TRANSISTOR_PNPSMD")
      (footprint "eagle-import:SOT23-3")
      (libsource (lib "eagle-import") (part "TRANSISTOR_PNPSMD"))
    )
    (comp (ref "Q7")
      (value "TRANSISTOR_PNPSMD")
      (footprint "eagle-import:SOT23-3")
      (libsource (lib "eagle-import") (part "TRANSISTOR_PNPSMD"))
    )
    (comp (ref "Q8")
      (value "TRANSISTOR_PNPSMD")
      (footprint "eagle-import:SOT23-3")
      (libsource (lib "eagle-import") (part "TRANSISTOR_PNPSMD"))
    )
    (comp (ref "Q9")
      (value "TRANSISTOR_PNPSMD")
      (footprint "eagle-import:SOT23-3")
      (libsource (lib "eagle-import") (part "TRANSISTOR_PNPSMD"))
    )
    (comp (ref "Q10")
      (value "TRANSISTOR_PNPSMD")
      (footprint "eagle-import:SOT23-3")
      (libsource (lib "eagle-import") (part "TRANSISTOR_PNPSMD"))
    )
    (comp (ref "Q11")
      (value "TRANSISTOR_PNPSMD")
      (footprint "eagle-import:SOT23-3")
      (libsource (lib "eagle-import") (part "TRANSISTOR_PNPSMD"))
    )
    (comp (ref "Q12")
      (value "TRANSISTOR_PNPSMD")
      (footprint "eagle-import:SOT23-3")
      (libsource (lib "eagle-import") (part "TRANSISTOR_PNPSMD"))
    )
    (comp (ref "Q13")
      (value "TRANSISTOR_PNPSMD")
      (footprint "eagle-import:SOT23-3")
      (libsource (lib "eagle-import") (part "TRANSISTOR_PNPSMD"))
    )
    (comp (ref "Q14")
      (value "TRANSISTOR_PNPSMD")
      (footprint "eagle-import:SOT23-3")
      (libsource (lib "eagle-import") (part "TRANSISTOR_PNPSMD"))
    )
    (comp (ref "Q15")
      (value "TRANSISTOR_PNPSMD")
      (footprint "eagle-import:SOT23-3")
      (libsource (lib "eagle-import") (part "TRANSISTOR_PNPSMD"))
    )
    (comp (ref "Q16")
      (value "TRANSISTOR_PNPSMD")
      (footprint "eagle-import:SOT23-3")
      (libsource (lib "eagle-import") (part "TRANSISTOR_PNPSMD"))
    )
    (comp (ref "R1")
      (value "RESISTOR0603")
      (footprint "eagle-import:0603-RES")
      (libsource (lib "eagle-import") (part "RESISTOR0603"))
    )
    (comp (ref "R2")
      (value "RESISTOR0603")
      (footprint "eagle-import:0603-RES")
      (libsource (lib "eagle-import") (part "RESISTOR0603"))
    )
    (comp (ref "R3")
      (value "RESISTOR0603")
      (footprint "eagle-import:0603-RES")
      (libsource (lib "eagle-import") (part "RESISTOR0603"))
    )
    (comp (ref "R4")
      (value "RESISTOR0603")
      (footprint "eagle-import:0603-RES")
      (libsource (lib "eagle-import") (part "RESISTOR0603"))
    )
    (comp (ref "R5")
      (value "RESISTOR0603")
      (footprint "eagle-import:0603-RES")
      (libsource (lib "eagle-import") (part "RESISTOR0603"))
    )
    (comp (ref "R6")
      (value "RESISTOR0603")
      (footprint "eagle-import:0603-RES")
      (libsource (lib "eagle-import") (part "RESISTOR0603"))
    )
    (comp (ref "R7")
      (value "RESISTOR0603")
      (footprint "eagle-import:0603-RES")
      (libsource (lib "eagle-import") (part "RESISTOR0603"))
    )
    (comp (ref "R8")
      (value "RESISTOR0603")
      (footprint "eagle-import:0603-RES")
      (libsource (lib "eagle-import") (part "RESISTOR0603"))
    )
    (comp (ref "R9")
      (value "RESISTOR0603")
      (footprint "eagle-import:0603-RES")
      (libsource (lib "eagle-import") (part "RESISTOR0603"))
    )
    (comp (ref "R10")
      (value "RESISTOR0603")
      (footprint "eagle-import:0603-RES")
      (libsource (lib "eagle-import") (part "RESISTOR0603"))
    )
    (comp (ref "R11")
      (value "RESISTOR0603")
      (footprint "eagle-import:0603-RES")
      (libsource (lib "eagle-import") (part "RESISTOR0603"))
    )
    (comp (ref "R12")
      (value "RESISTOR0603")
      (footprint "eagle-import:0603-RES")
      (libsource (lib "eagle-import") (part "RESISTOR0603"))
    )
    (comp (ref "R13")
      (value "RESISTOR0603")
      (footprint "eagle-import:0603-RES")
      (libsource (lib "eagle-import") (part "RESISTOR0603"))
    )
    (comp (ref "R14")
      (value "RESISTOR0603")
      (footprint "eagle-import:0603-RES")
      (libsource (lib "eagle-import") (part "RESISTOR0603"))
    )
    (comp (ref "R15")
      (value "RESISTOR0603")
      (footprint "eagle-import:0603-RES")
      (libsource (lib "eagle-import") (part "RESISTOR0603"))
    )
    (comp (ref "R16")
      (value "RESISTOR0603")
      (footprint "eagle-import:0603-RES")
      (libsource (lib "eagle-import") (part "RESISTOR0603"))
    )
    (comp (ref "R17")
      (value "RESISTOR0603")
      (footprint "eagle-import:0603-RES")
      (libsource (lib "eagle-import") (part "RESISTOR0603"))
    )
    (comp (ref "R18")
      (value "RESISTOR0603")
      (footprint "eagle-import:0603-RES")
      (libsource (lib "eagle-import") (part "RESISTOR0603"))
    )
    (comp (ref "R19")
      (value "RESISTOR0603")
      (footprint "eagle-import:0603-RES")
      (libsource (lib "eagle-import") (part "RESISTOR0603"))
    )
    (comp (ref "R20")
      (value "RESISTOR0603")
      (footprint "eagle-import:0603-RES")
      (libsource (lib "eagle-import") (part "RESISTOR0603"))
    )
    (comp (ref "R21")
      (value "RESISTOR0603")
      (footprint "eagle-import:0603-RES")
      (libsource (lib "eagle-import") (part "RESISTOR0603"))
    )
    (comp (ref "R22")
      (value "RESISTOR0603")
      (footprint "eagle-import:0603-RES")
      (libsource (lib "eagle-import") (part "RESISTOR0603"))
    )
    (comp (ref "R23")
      (value "RESISTOR0603")
      (footprint "eagle-import:0603-RES")
      (libsource (lib "eagle-import") (part "RESISTOR0603"))
    )
    (comp (ref "R24")
      (value "RESISTOR0603")
      (footprint "eagle-import:0603-RES")
      (libsource (lib "eagle-import") (part "RESISTOR0603"))
    )
    (comp (ref "R25")
      (value "RESISTOR0603")
      (footprint "eagle-import:0603-RES")
      (libsource (lib "eagle-import") (part "RESISTOR0603"))
    )
    (comp (ref "R26")
      (value "RESISTOR0603")
      (footprint "eagle-import:0603-RES")
      (libsource (lib "eagle-import") (part "RESISTOR0603"))
    )
    (comp (ref "R27")
      (value "RESISTOR0603")
      (footprint "eagle-import:0603-RES")
      (libsource (lib "eagle-import") (part "RESISTOR0603"))
    )
    (comp (ref "R28")
      (value "RESISTOR0603")
      (footprint "eagle-import:0603-RES")
      (libsource (lib "eagle-import") (part "RESISTOR0603"))
    )
    (comp (ref "R29")
      (value "RESISTOR0603")
      (footprint "eagle-import:0603-RES")
      (libsource (lib "eagle-import") (part "RESISTOR0603"))
    )
    (comp (ref "R30")
      (value "RESISTOR0603")
      (footprint "eagle-import:0603-RES")
      (libsource (lib "eagle-import") (part "RESISTOR0603"))
    )
    (comp (ref "R31")
      (value "RESISTOR0603")
      (footprint "eagle-import:0603-RES")
      (libsource (lib "eagle-import") (part "RESISTOR0603"))
    )
    (comp (ref "R32")
      (value "RESISTOR0603")
      (footprint "eagle-import:0603-RES")
      (libsource (lib "eagle-import") (part "RESISTOR0603"))
    )
    (comp (ref "R33")
      (value "RESISTOR0603")
      (footprint "eagle-import:0603-RES")
      (libsource (lib "eagle-import") (part "RESISTOR0603"))
    )
    (comp (ref "R34")
      (value "RESISTOR0603")
      (footprint "eagle-import:0603-RES")
      (libsource (lib "eagle-import") (part "RESISTOR0603"))
    )
    (comp (ref "U$1")
      (value "PT15-21B")
      (footprint "eagle-import:1206")
      (libsource (lib "eagle-import") (part "PT15-21B"))
    )
    (comp (ref "U$2")
      (value "PT15-21B")
      (footprint "eagle-import:1206")
      (libsource (lib "eagle-import") (part "PT15-21B"))
    )
    (comp (ref "U$3")
      (value "PT15-21B")
      (footprint "eagle-import:1206")
      (libsource (lib "eagle-import") (part "PT15-21B"))
    )
    (comp (ref "U$4")
      (value "PT15-21B")
      (footprint "eagle-import:1206")
      (libsource (lib "eagle-import") (part "PT15-21B"))
    )
    (comp (ref "U$5")
      (value "MUX-74HC4067SMD")
      (footprint "eagle-import:SSOP24")
      (libsource (lib "eagle-import") (part "MUX-74HC4067SMD"))
    )
    (comp (ref "U$6")
      (value "PT15-21B")
      (footprint "eagle-import:1206")
      (libsource (lib "eagle-import") (part "PT15-21B"))
    )
    (comp (ref "U$7")
      (value "PT15-21B")
      (footprint "eagle-import:1206")
      (libsource (lib "eagle-import") (part "PT15-21B"))
    )
    (comp (ref "U$8")
      (value "PT15-21B")
      (footprint "eagle-import:1206")
      (libsource (lib "eagle-import") (part "PT15-21B"))
    )
    (comp (ref "U$9")
      (value "PT15-21B")
      (footprint "eagle-import:1206")
      (libsource (lib "eagle-import") (part "PT15-21B"))
    )
    (comp (ref "U$10")
      (value "PT15-21B")
      (footprint "eagle-import:1206")
      (libsource (lib "eagle-import") (part "PT15-21B"))
    )
    (comp (ref "U$11")
      (value "PT15-21B")
      (footprint "eagle-import:1206")
      (libsource (lib "eagle-import") (part "PT15-21B"))
    )
    (comp (ref "U$12")
      (value "PT15-21B")
      (footprint "eagle-import:1206")
      (libsource (lib "eagle-import") (part "PT15-21B"))
    )
    (comp (ref "U$13")
      (value "PT15-21B")
      (footprint "eagle-import:1206")
      (libsource (lib "eagle-import") (part "PT15-21B"))
    )
    (comp (ref "U$14")
      (value "PT15-21B")
      (footprint "eagle-import:1206")
      (libsource (lib "eagle-import") (part "PT15-21B"))
    )
    (comp (ref "U$15")
      (value "PT15-21B")
      (footprint "eagle-import:1206")
      (libsource (lib "eagle-import") (part "PT15-21B"))
    )
    (comp (ref "U$16")
      (value "PT15-21B")
      (footprint "eagle-import:1206")
      (libsource (lib "eagle-import") (part "PT15-21B"))
    )
    (comp (ref "U$17")
      (value "PT15-21B")
      (footprint "eagle-import:1206")
      (libsource (lib "eagle-import") (part "PT15-21B"))
    )
    (comp (ref "U$18")
      (value "PT15-21B")
      (footprint "eagle-import:1206")
      (libsource (lib "eagle-import") (part "PT15-21B"))
    )
    (comp (ref "U$19")
      (value "PT15-21B")
      (footprint "eagle-import:1206")
      (libsource (lib "eagle-import") (part "PT15-21B"))
    )
    (comp (ref "U$20")
      (value "PT15-21B")
      (footprint "eagle-import:1206")
      (libsource (lib "eagle-import") (part "PT15-21B"))
    )
    (comp (ref "U$21")
      (value "PT15-21B")
      (footprint "eagle-import:1206")
      (libsource (lib "eagle-import") (part "PT15-21B"))
    )
    (comp (ref "U$22")
      (value "PT15-21B")
      (footprint "eagle-import:1206")
      (libsource (lib "eagle-import") (part "PT15-21B"))
    )
    (comp (ref "U$23")
      (value "PT15-21B")
      (footprint "eagle-import:1206")
      (libsource (lib "eagle-import") (part "PT15-21B"))
    )
    (comp (ref "U$24")
      (value "PT15-21B")
      (footprint "eagle-import:1206")
      (libsource (lib "eagle-import") (part "PT15-21B"))
    )
    (comp (ref "U$25")
      (value "PT15-21B")
      (footprint "eagle-import:1206")
      (libsource (lib "eagle-import") (part "PT15-21B"))
    )
    (comp (ref "U$26")
      (value "PT15-21B")
      (footprint "eagle-import:1206")
      (libsource (lib "eagle-import") (part "PT15-21B"))
    )
    (comp (ref "U$27")
      (value "PT15-21B")
      (footprint "eagle-import:1206")
      (libsource (lib "eagle-import") (part "PT15-21B"))
    )
    (comp (ref "U$28")
      (value "PT15-21B")
      (footprint "eagle-import:1206")
      (libsource (lib "eagle-import") (part "PT15-21B"))
    )
    (comp (ref "U$29")
      (value "PT15-21B")
      (footprint "eagle-import:1206")
      (libsource (lib "eagle-import") (part "PT15-21B"))
    )
    (comp (ref "U$30")
      (value "PT15-21B")
      (footprint "eagle-import:1206")
      (libsource (lib "eagle-import") (part "PT15-21B"))
    )
    (comp (ref "U$31")
      (value "PT15-21B")
      (footprint "eagle-import:1206")
      (libsource (lib "eagle-import") (part "PT15-21B"))
    )
    (comp (ref "U$32")
      (value "PT15-21B")
      (footprint "eagle-import:1206")
      (libsource (lib "eagle-import") (part "PT15-21B"))
    )
    (comp (ref "U$33")
      (value "PT15-21B")
      (footprint "eagle-import:1206")
      (libsource (lib "eagle-import") (part "PT15-21B"))
    )
    (comp (ref "U$34")
      (value "PT15-21B")
      (footprint "eagle-import:1206")
      (libsource (lib "eagle-import") (part "PT15-21B"))
    )
    (comp (ref "U$35")
      (value "PT15-21B")
      (footprint "eagle-import:1206")
      (libsource (lib "eagle-import") (part "PT15-21B"))
    )
    (comp (ref "U$36")
      (value "PT15-21B")
      (footprint "eagle-import:1206")
      (libsource (lib "eagle-import") (part "PT15-21B"))
    )
    (comp (ref "U$37")
      (value "PT15-21B")
      (footprint "eagle-import:1206")
      (libsource (lib "eagle-import") (part "PT15-21B"))
    )
    (comp (ref "U$38")
      (value "PT15-21B")
      (footprint "eagle-import:1206")
      (libsource (lib "eagle-import") (part "PT15-21B"))
    )
    (comp (ref "U$39")
      (value "PT15-21B")
      (footprint "eagle-import:1206")
      (libsource (lib "eagle-import") (part "PT15-21B"))
    )
    (comp (ref "U$40")
      (value "PT15-21B")
      (footprint "eagle-import:1206")
      (libsource (lib "eagle-import") (part "PT15-21B"))
    )
    (comp (ref "U$41")
      (value "PT15-21B")
      (footprint "eagle-import:1206")
      (libsource (lib "eagle-import") (part "PT15-21B"))
    )
    (comp (ref "U$42")
      (value "PT15-21B")
      (footprint "eagle-import:1206")
      (libsource (lib "eagle-import") (part "PT15-21B"))
    )
    (comp (ref "U$43")
      (value "PT15-21B")
      (footprint "eagle-import:1206")
      (libsource (lib "eagle-import") (part "PT15-21B"))
    )
    (comp (ref "U$44")
      (value "PT15-21B")
      (footprint "eagle-import:1206")
      (libsource (lib "eagle-import") (part "PT15-21B"))
    )
    (comp (ref "U$45")
      (value "PT15-21B")
      (footprint "eagle-import:1206")
      (libsource (lib "eagle-import") (part "PT15-21B"))
    )
    (comp (ref "U$46")
      (value "PT15-21B")
      (footprint "eagle-import:1206")
      (libsource (lib "eagle-import") (part "PT15-21B"))
    )
    (comp (ref "U$47")
      (value "PT15-21B")
      (footprint "eagle-import:1206")
      (libsource (lib "eagle-import") (part "PT15-21B"))
    )
    (comp (ref "U$48")
      (value "PT15-21B")
      (footprint "eagle-import:1206")
      (libsource (lib "eagle-import") (part "PT15-21B"))
    )
    (comp (ref "U$49")
      (value "PT15-21B")
      (footprint "eagle-import:1206")
      (libsource (lib "eagle-import") (part "PT15-21B"))
    )
    (comp (ref "U$50")
      (value "PT15-21B")
      (footprint "eagle-import:1206")
      (libsource (lib "eagle-import") (part "PT15-21B"))
    )
    (comp (ref "U$51")
      (value "PT15-21B")
      (footprint "eagle-import:1206")
      (libsource (lib "eagle-import") (part "PT15-21B"))
    )
    (comp (ref "U$52")
      (value "PT15-21B")
      (footprint "eagle-import:1206")
      (libsource (lib "eagle-import") (part "PT15-21B"))
    )
    (comp (ref "U$53")
      (value "PT15-21B")
      (footprint "eagle-import:1206")
      (libsource (lib "eagle-import") (part "PT15-21B"))
    )
    (comp (ref "U$54")
      (value "PT15-21B")
      (footprint "eagle-import:1206")
      (libsource (lib "eagle-import") (part "PT15-21B"))
    )
    (comp (ref "U$55")
      (value "PT15-21B")
      (footprint "eagle-import:1206")
      (libsource (lib "eagle-import") (part "PT15-21B"))
    )
    (comp (ref "U$56")
      (value "PT15-21B")
      (footprint "eagle-import:1206")
      (libsource (lib "eagle-import") (part "PT15-21B"))
    )
    (comp (ref "U$57")
      (value "PT15-21B")
      (footprint "eagle-import:1206")
      (libsource (lib "eagle-import") (part "PT15-21B"))
    )
    (comp (ref "U$58")
      (value "PT15-21B")
      (footprint "eagle-import:1206")
      (libsource (lib "eagle-import") (part "PT15-21B"))
    )
    (comp (ref "U$59")
      (value "PT15-21B")
      (footprint "eagle-import:1206")
      (libsource (lib "eagle-import") (part "PT15-21B"))
    )
    (comp (ref "U$60")
      (value "PT15-21B")
      (footprint "eagle-import:1206")
      (libsource (lib "eagle-import") (part "PT15-21B"))
    )
    (comp (ref "U$61")
      (value "PT15-21B")
      (footprint "eagle-import:1206")
      (libsource (lib "eagle-import") (part "PT15-21B"))
    )
    (comp (ref "U$62")
      (value "PT15-21B")
      (footprint "eagle-import:1206")
      (libsource (lib "eagle-import") (part "PT15-21B"))
    )
    (comp (ref "U$63")
      (value "PT15-21B")
      (footprint "eagle-import:1206")
      (libsource (lib "eagle-import") (part "PT15-21B"))
    )
    (comp (ref "U$64")
      (value "PT15-21B")
      (footprint "eagle-import:1206")
      (libsource (lib "eagle-import") (part "PT15-21B"))
    )
    (comp (ref "U$65")
      (value "PT15-21B")
      (footprint "eagle-import:1206")
      (libsource (lib "eagle-import") (part "PT15-21B"))
    )
    (comp (ref "U$66")
      (value "PT15-21B")
      (footprint "eagle-import:1206")
      (libsource (lib "eagle-import") (part "PT15-21B"))
    )
    (comp (ref "U$67")
      (value "PT15-21B")
      (footprint "eagle-import:1206")
      (libsource (lib "eagle-import") (part "PT15-21B"))
    )
    (comp (ref "U$68")
      (value "PT15-21B")
      (footprint "eagle-import:1206")
      (libsource (lib "eagle-import") (part "PT15-21B"))
    )
    (comp (ref "U$69")
      (value "PT15-21B")
      (footprint "eagle-import:1206")
      (libsource (lib "eagle-import") (part "PT15-21B"))
    )
    (comp (ref "U$70")
      (value "PT15-21B")
      (footprint "eagle-import:1206")
      (libsource (lib "eagle-import") (part "PT15-21B"))
    )
    (comp (ref "U$71")
      (value "PT15-21B")
      (footprint "eagle-import:1206")
      (libsource (lib "eagle-import") (part "PT15-21B"))
    )
    (comp (ref "U$72")
      (value "PT15-21B")
      (footprint "eagle-import:1206")
      (libsource (lib "eagle-import") (part "PT15-21B"))
    )
    (comp (ref "U$73")
      (value "PT15-21B")
      (footprint "eagle-import:1206")
      (libsource (lib "eagle-import") (part "PT15-21B"))
    )
    (comp (ref "U$74")
      (value "PT15-21B")
      (footprint "eagle-import:1206")
      (libsource (lib "eagle-import") (part "PT15-21B"))
    )
    (comp (ref "U$75")
      (value "PT15-21B")
      (footprint "eagle-import:1206")
      (libsource (lib "eagle-import") (part "PT15-21B"))
    )
    (comp (ref "U$76")
      (value "PT15-21B")
      (footprint "eagle-import:1206")
      (libsource (lib "eagle-import") (part "PT15-21B"))
    )
    (comp (ref "U$77")
      (value "PT15-21B")
      (footprint "eagle-import:1206")
      (libsource (lib "eagle-import") (part "PT15-21B"))
    )
    (comp (ref "U$78")
      (value "PT15-21B")
      (footprint "eagle-import:1206")
      (libsource (lib "eagle-import") (part "PT15-21B"))
    )
    (comp (ref "U$79")
      (value "PT15-21B")
      (footprint "eagle-import:1206")
      (libsource (lib "eagle-import") (part "PT15-21B"))
    )
    (comp (ref "U$80")
      (value "PT15-21B")
      (footprint "eagle-import:1206")
      (libsource (lib "eagle-import") (part "PT15-21B"))
    )
    (comp (ref "U$81")
      (value "PT15-21B")
      (footprint "eagle-import:1206")
      (libsource (lib "eagle-import") (part "PT15-21B"))
    )
    (comp (ref "U$82")
      (value "PT15-21B")
      (footprint "eagle-import:1206")
      (libsource (lib "eagle-import") (part "PT15-21B"))
    )
    (comp (ref "U$83")
      (value "PT15-21B")
      (footprint "eagle-import:1206")
      (libsource (lib "eagle-import") (part "PT15-21B"))
    )
    (comp (ref "U$84")
      (value "PT15-21B")
      (footprint "eagle-import:1206")
      (libsource (lib "eagle-import") (part "PT15-21B"))
    )
    (comp (ref "U$85")
      (value "PT15-21B")
      (footprint "eagle-import:1206")
      (libsource (lib "eagle-import") (part "PT15-21B"))
    )
    (comp (ref "U$86")
      (value "PT15-21B")
      (footprint "eagle-import:1206")
      (libsource (lib "eagle-import") (part "PT15-21B"))
    )
    (comp (ref "U$87")
      (value "PT15-21B")
      (footprint "eagle-import:1206")
      (libsource (lib "eagle-import") (part "PT15-21B"))
    )
    (comp (ref "U$88")
      (value "PT15-21B")
      (footprint "eagle-import:1206")
      (libsource (lib "eagle-import") (part "PT15-21B"))
    )
    (comp (ref "U$89")
      (value "PT15-21B")
      (footprint "eagle-import:1206")
      (libsource (lib "eagle-import") (part "PT15-21B"))
    )
    (comp (ref "U$90")
      (value "PT15-21B")
      (footprint "eagle-import:1206")
      (libsource (lib "eagle-import") (part "PT15-21B"))
    )
    (comp (ref "U$91")
      (value "PT15-21B")
      (footprint "eagle-import:1206")
      (libsource (lib "eagle-import") (part "PT15-21B"))
    )
    (comp (ref "U$92")
      (value "PT15-21B")
      (footprint "eagle-import:1206")
      (libsource (lib "eagle-import") (part "PT15-21B"))
    )
    (comp (ref "U$93")
      (value "PT15-21B")
      (footprint "eagle-import:1206")
      (libsource (lib "eagle-import") (part "PT15-21B"))
    )
    (comp (ref "U$94")
      (value "PT15-21B")
      (footprint "eagle-import:1206")
      (libsource (lib "eagle-import") (part "PT15-21B"))
    )
    (comp (ref "U$95")
      (value "PT15-21B")
      (footprint "eagle-import:1206")
      (libsource (lib "eagle-import") (part "PT15-21B"))
    )
    (comp (ref "U$96")
      (value "PT15-21B")
      (footprint "eagle-import:1206")
      (libsource (lib "eagle-import") (part "PT15-21B"))
    )
    (comp (ref "U$97")
      (value "PT15-21B")
      (footprint "eagle-import:1206")
      (libsource (lib "eagle-import") (part "PT15-21B"))
    )
    (comp (ref "U$98")
      (value "PT15-21B")
      (footprint "eagle-import:1206")
      (libsource (lib "eagle-import") (part "PT15-21B"))
    )
    (comp (ref "U$99")
      (value "PT15-21B")
      (footprint "eagle-import:1206")
      (libsource (lib "eagle-import") (part "PT15-21B"))
    )
    (comp (ref "U$100")
      (value "PT15-21B")
      (footprint "eagle-import:1206")
      (libsource (lib "eagle-import") (part "PT15-21B"))
    )
    (comp (ref "U$101")
      (value "PT15-21B")
      (footprint "eagle-import:1206")
      (libsource (lib "eagle-import") (part "PT15-21B"))
    )
    (comp (ref "U$102")
      (value "PT15-21B")
      (footprint "eagle-import:1206")
      (libsource (lib "eagle-import") (part "PT15-21B"))
    )
    (comp (ref "U$103")
      (value "PT15-21B")
      (footprint "eagle-import:1206")
      (libsource (lib "eagle-import") (part "PT15-21B"))
    )
    (comp (ref "U$104")
      (value "PT15-21B")
      (footprint "eagle-import:1206")
      (libsource (lib "eagle-import") (part "PT15-21B"))
    )
    (comp (ref "U$105")
      (value "PT15-21B")
      (footprint "eagle-import:1206")
      (libsource (lib "eagle-import") (part "PT15-21B"))
    )
    (comp (ref "U$106")
      (value "PT15-21B")
      (footprint "eagle-import:1206")
      (libsource (lib "eagle-import") (part "PT15-21B"))
    )
    (comp (ref "U$107")
      (value "PT15-21B")
      (footprint "eagle-import:1206")
      (libsource (lib "eagle-import") (part "PT15-21B"))
    )
    (comp (ref "U$108")
      (value "PT15-21B")
      (footprint "eagle-import:1206")
      (libsource (lib "eagle-import") (part "PT15-21B"))
    )
    (comp (ref "U$109")
      (value "PT15-21B")
      (footprint "eagle-import:1206")
      (libsource (lib "eagle-import") (part "PT15-21B"))
    )
    (comp (ref "U$110")
      (value "PT15-21B")
      (footprint "eagle-import:1206")
      (libsource (lib "eagle-import") (part "PT15-21B"))
    )
    (comp (ref "U$111")
      (value "PT15-21B")
      (footprint "eagle-import:1206")
      (libsource (lib "eagle-import") (part "PT15-21B"))
    )
    (comp (ref "U$112")
      (value "PT15-21B")
      (footprint "eagle-import:1206")
      (libsource (lib "eagle-import") (part "PT15-21B"))
    )
    (comp (ref "U$113")
      (value "PT15-21B")
      (footprint "eagle-import:1206")
      (libsource (lib "eagle-import") (part "PT15-21B"))
    )
    (comp (ref "U$114")
      (value "PT15-21B")
      (footprint "eagle-import:1206")
      (libsource (lib "eagle-import") (part "PT15-21B"))
    )
    (comp (ref "U$115")
      (value "PT15-21B")
      (footprint "eagle-import:1206")
      (libsource (lib "eagle-import") (part "PT15-21B"))
    )
    (comp (ref "U$116")
      (value "PT15-21B")
      (footprint "eagle-import:1206")
      (libsource (lib "eagle-import") (part "PT15-21B"))
    )
    (comp (ref "U$117")
      (value "PT15-21B")
      (footprint "eagle-import:1206")
      (libsource (lib "eagle-import") (part "PT15-21B"))
    )
    (comp (ref "U$118")
      (value "PT15-21B")
      (footprint "eagle-import:1206")
      (libsource (lib "eagle-import") (part "PT15-21B"))
    )
    (comp (ref "U$119")
      (value "PT15-21B")
      (footprint "eagle-import:1206")
      (libsource (lib "eagle-import") (part "PT15-21B"))
    )
    (comp (ref "U$120")
      (value "PT15-21B")
      (footprint "eagle-import:1206")
      (libsource (lib "eagle-import") (part "PT15-21B"))
    )
    (comp (ref "U$121")
      (value "PT15-21B")
      (footprint "eagle-import:1206")
      (libsource (lib "eagle-import") (part "PT15-21B"))
    )
    (comp (ref "U$122")
      (value "PT15-21B")
      (footprint "eagle-import:1206")
      (libsource (lib "eagle-import") (part "PT15-21B"))
    )
    (comp (ref "U$123")
      (value "PT15-21B")
      (footprint "eagle-import:1206")
      (libsource (lib "eagle-import") (part "PT15-21B"))
    )
    (comp (ref "U$124")
      (value "PT15-21B")
      (footprint "eagle-import:1206")
      (libsource (lib "eagle-import") (part "PT15-21B"))
    )
    (comp (ref "U$125")
      (value "PT15-21B")
      (footprint "eagle-import:1206")
      (libsource (lib "eagle-import") (part "PT15-21B"))
    )
    (comp (ref "U$126")
      (value "PT15-21B")
      (footprint "eagle-import:1206")
      (libsource (lib "eagle-import") (part "PT15-21B"))
    )
    (comp (ref "U$127")
      (value "PT15-21B")
      (footprint "eagle-import:1206")
      (libsource (lib "eagle-import") (part "PT15-21B"))
    )
    (comp (ref "U$128")
      (value "PT15-21B")
      (footprint "eagle-import:1206")
      (libsource (lib "eagle-import") (part "PT15-21B"))
    )
    (comp (ref "U$129")
      (value "PT15-21B")
      (footprint "eagle-import:1206")
      (libsource (lib "eagle-import") (part "PT15-21B"))
    )
    (comp (ref "U$130")
      (value "PT15-21B")
      (footprint "eagle-import:1206")
      (libsource (lib "eagle-import") (part "PT15-21B"))
    )
    (comp (ref "U$131")
      (value "PT15-21B")
      (footprint "eagle-import:1206")
      (libsource (lib "eagle-import") (part "PT15-21B"))
    )
    (comp (ref "U$132")
      (value "PT15-21B")
      (footprint "eagle-import:1206")
      (libsource (lib "eagle-import") (part "PT15-21B"))
    )
    (comp (ref "U$133")
      (value "PT15-21B")
      (footprint "eagle-import:1206")
      (libsource (lib "eagle-import") (part "PT15-21B"))
    )
    (comp (ref "U$134")
      (value "PT15-21B")
      (footprint "eagle-import:1206")
      (libsource (lib "eagle-import") (part "PT15-21B"))
    )
    (comp (ref "U$135")
      (value "PT15-21B")
      (footprint "eagle-import:1206")
      (libsource (lib "eagle-import") (part "PT15-21B"))
    )
    (comp (ref "U$136")
      (value "PT15-21B")
      (footprint "eagle-import:1206")
      (libsource (lib "eagle-import") (part "PT15-21B"))
    )
    (comp (ref "U$137")
      (value "PT15-21B")
      (footprint "eagle-import:1206")
      (libsource (lib "eagle-import") (part "PT15-21B"))
    )
    (comp (ref "U$138")
      (value "PT15-21B")
      (footprint "eagle-import:1206")
      (libsource (lib "eagle-import") (part "PT15-21B"))
    )
    (comp (ref "U$139")
      (value "PT15-21B")
      (footprint "eagle-import:1206")
      (libsource (lib "eagle-import") (part "PT15-21B"))
    )
    (comp (ref "U$140")
      (value "PT15-21B")
      (footprint "eagle-import:1206")
      (libsource (lib "eagle-import") (part "PT15-21B"))
    )
    (comp (ref "U$141")
      (value "PT15-21B")
      (footprint "eagle-import:1206")
      (libsource (lib "eagle-import") (part "PT15-21B"))
    )
    (comp (ref "U$142")
      (value "PT15-21B")
      (footprint "eagle-import:1206")
      (libsource (lib "eagle-import") (part "PT15-21B"))
    )
    (comp (ref "U$143")
      (value "PT15-21B")
      (footprint "eagle-import:1206")
      (libsource (lib "eagle-import") (part "PT15-21B"))
    )
    (comp (ref "U$144")
      (value "PT15-21B")
      (footprint "eagle-import:1206")
      (libsource (lib "eagle-import") (part "PT15-21B"))
    )
    (comp (ref "U$145")
      (value "PT15-21B")
      (footprint "eagle-import:1206")
      (libsource (lib "eagle-import") (part "PT15-21B"))
    )
    (comp (ref "U$146")
      (value "PT15-21B")
      (footprint "eagle-import:1206")
      (libsource (lib "eagle-import") (part "PT15-21B"))
    )
    (comp (ref "U$147")
      (value "PT15-21B")
      (footprint "eagle-import:1206")
      (libsource (lib "eagle-import") (part "PT15-21B"))
    )
    (comp (ref "U$148")
      (value "PT15-21B")
      (footprint "eagle-import:1206")
      (libsource (lib "eagle-import") (part "PT15-21B"))
    )
    (comp (ref "U$149")
      (value "PT15-21B")
      (footprint "eagle-import:1206")
      (libsource (lib "eagle-import") (part "PT15-21B"))
    )
    (comp (ref "U$150")
      (value "PT15-21B")
      (footprint "eagle-import:1206")
      (libsource (lib "eagle-import") (part "PT15-21B"))
    )
    (comp (ref "U$151")
      (value "PT15-21B")
      (footprint "eagle-import:1206")
      (libsource (lib "eagle-import") (part "PT15-21B"))
    )
    (comp (ref "U$152")
      (value "PT15-21B")
      (footprint "eagle-import:1206")
      (libsource (lib "eagle-import") (part "PT15-21B"))
    )
    (comp (ref "U$153")
      (value "PT15-21B")
      (footprint "eagle-import:1206")
      (libsource (lib "eagle-import") (part "PT15-21B"))
    )
    (comp (ref "U$154")
      (value "PT15-21B")
      (footprint "eagle-import:1206")
      (libsource (lib "eagle-import") (part "PT15-21B"))
    )
    (comp (ref "U$155")
      (value "PT15-21B")
      (footprint "eagle-import:1206")
      (libsource (lib "eagle-import") (part "PT15-21B"))
    )
    (comp (ref "U$156")
      (value "PT15-21B")
      (footprint "eagle-import:1206")
      (libsource (lib "eagle-import") (part "PT15-21B"))
    )
    (comp (ref "U$157")
      (value "PT15-21B")
      (footprint "eagle-import:1206")
      (libsource (lib "eagle-import") (part "PT15-21B"))
    )
    (comp (ref "U$158")
      (value "PT15-21B")
      (footprint "eagle-import:1206")
      (libsource (lib "eagle-import") (part "PT15-21B"))
    )
    (comp (ref "U$159")
      (value "PT15-21B")
      (footprint "eagle-import:1206")
      (libsource (lib "eagle-import") (part "PT15-21B"))
    )
    (comp (ref "U$160")
      (value "PT15-21B")
      (footprint "eagle-import:1206")
      (libsource (lib "eagle-import") (part "PT15-21B"))
    )
    (comp (ref "U$161")
      (value "PT15-21B")
      (footprint "eagle-import:1206")
      (libsource (lib "eagle-import") (part "PT15-21B"))
    )
    (comp (ref "U$162")
      (value "PT15-21B")
      (footprint "eagle-import:1206")
      (libsource (lib "eagle-import") (part "PT15-21B"))
    )
    (comp (ref "U$163")
      (value "PT15-21B")
      (footprint "eagle-import:1206")
      (libsource (lib "eagle-import") (part "PT15-21B"))
    )
    (comp (ref "U$164")
      (value "PT15-21B")
      (footprint "eagle-import:1206")
      (libsource (lib "eagle-import") (part "PT15-21B"))
    )
    (comp (ref "U$165")
      (value "PT15-21B")
      (footprint "eagle-import:1206")
      (libsource (lib "eagle-import") (part "PT15-21B"))
    )
    (comp (ref "U$166")
      (value "PT15-21B")
      (footprint "eagle-import:1206")
      (libsource (lib "eagle-import") (part "PT15-21B"))
    )
    (comp (ref "U$167")
      (value "PT15-21B")
      (footprint "eagle-import:1206")
      (libsource (lib "eagle-import") (part "PT15-21B"))
    )
    (comp (ref "U$168")
      (value "PT15-21B")
      (footprint "eagle-import:1206")
      (libsource (lib "eagle-import") (part "PT15-21B"))
    )
    (comp (ref "U$169")
      (value "PT15-21B")
      (footprint "eagle-import:1206")
      (libsource (lib "eagle-import") (part "PT15-21B"))
    )
    (comp (ref "U$170")
      (value "PT15-21B")
      (footprint "eagle-import:1206")
      (libsource (lib "eagle-import") (part "PT15-21B"))
    )
    (comp (ref "U$171")
      (value "PT15-21B")
      (footprint "eagle-import:1206")
      (libsource (lib "eagle-import") (part "PT15-21B"))
    )
    (comp (ref "U$172")
      (value "PT15-21B")
      (footprint "eagle-import:1206")
      (libsource (lib "eagle-import") (part "PT15-21B"))
    )
    (comp (ref "U$173")
      (value "PT15-21B")
      (footprint "eagle-import:1206")
      (libsource (lib "eagle-import") (part "PT15-21B"))
    )
    (comp (ref "U$174")
      (value "PT15-21B")
      (footprint "eagle-import:1206")
      (libsource (lib "eagle-import") (part "PT15-21B"))
    )
    (comp (ref "U$175")
      (value "PT15-21B")
      (footprint "eagle-import:1206")
      (libsource (lib "eagle-import") (part "PT15-21B"))
    )
    (comp (ref "U$176")
      (value "PT15-21B")
      (footprint "eagle-import:1206")
      (libsource (lib "eagle-import") (part "PT15-21B"))
    )
    (comp (ref "U$177")
      (value "PT15-21B")
      (footprint "eagle-import:1206")
      (libsource (lib "eagle-import") (part "PT15-21B"))
    )
    (comp (ref "U$178")
      (value "PT15-21B")
      (footprint "eagle-import:1206")
      (libsource (lib "eagle-import") (part "PT15-21B"))
    )
    (comp (ref "U$179")
      (value "PT15-21B")
      (footprint "eagle-import:1206")
      (libsource (lib "eagle-import") (part "PT15-21B"))
    )
    (comp (ref "U$180")
      (value "PT15-21B")
      (footprint "eagle-import:1206")
      (libsource (lib "eagle-import") (part "PT15-21B"))
    )
    (comp (ref "U$181")
      (value "PT15-21B")
      (footprint "eagle-import:1206")
      (libsource (lib "eagle-import") (part "PT15-21B"))
    )
    (comp (ref "U$182")
      (value "PT15-21B")
      (footprint "eagle-import:1206")
      (libsource (lib "eagle-import") (part "PT15-21B"))
    )
    (comp (ref "U$183")
      (value "PT15-21B")
      (footprint "eagle-import:1206")
      (libsource (lib "eagle-import") (part "PT15-21B"))
    )
    (comp (ref "U$184")
      (value "PT15-21B")
      (footprint "eagle-import:1206")
      (libsource (lib "eagle-import") (part "PT15-21B"))
    )
    (comp (ref "U$185")
      (value "PT15-21B")
      (footprint "eagle-import:1206")
      (libsource (lib "eagle-import") (part "PT15-21B"))
    )
    (comp (ref "U$186")
      (value "PT15-21B")
      (footprint "eagle-import:1206")
      (libsource (lib "eagle-import") (part "PT15-21B"))
    )
    (comp (ref "U$187")
      (value "PT15-21B")
      (footprint "eagle-import:1206")
      (libsource (lib "eagle-import") (part "PT15-21B"))
    )
    (comp (ref "U$188")
      (value "PT15-21B")
      (footprint "eagle-import:1206")
      (libsource (lib "eagle-import") (part "PT15-21B"))
    )
    (comp (ref "U$189")
      (value "PT15-21B")
      (footprint "eagle-import:1206")
      (libsource (lib "eagle-import") (part "PT15-21B"))
    )
    (comp (ref "U$190")
      (value "PT15-21B")
      (footprint "eagle-import:1206")
      (libsource (lib "eagle-import") (part "PT15-21B"))
    )
    (comp (ref "U$191")
      (value "PT15-21B")
      (footprint "eagle-import:1206")
      (libsource (lib "eagle-import") (part "PT15-21B"))
    )
    (comp (ref "U$192")
      (value "PT15-21B")
      (footprint "eagle-import:1206")
      (libsource (lib "eagle-import") (part "PT15-21B"))
    )
    (comp (ref "U$193")
      (value "PT15-21B")
      (footprint "eagle-import:1206")
      (libsource (lib "eagle-import") (part "PT15-21B"))
    )
    (comp (ref "U$194")
      (value "PT15-21B")
      (footprint "eagle-import:1206")
      (libsource (lib "eagle-import") (part "PT15-21B"))
    )
    (comp (ref "U$195")
      (value "PT15-21B")
      (footprint "eagle-import:1206")
      (libsource (lib "eagle-import") (part "PT15-21B"))
    )
    (comp (ref "U$196")
      (value "PT15-21B")
      (footprint "eagle-import:1206")
      (libsource (lib "eagle-import") (part "PT15-21B"))
    )
    (comp (ref "U$197")
      (value "PT15-21B")
      (footprint "eagle-import:1206")
      (libsource (lib "eagle-import") (part "PT15-21B"))
    )
    (comp (ref "U$198")
      (value "PT15-21B")
      (footprint "eagle-import:1206")
      (libsource (lib "eagle-import") (part "PT15-21B"))
    )
    (comp (ref "U$199")
      (value "PT15-21B")
      (footprint "eagle-import:1206")
      (libsource (lib "eagle-import") (part "PT15-21B"))
    )
    (comp (ref "U$200")
      (value "PT15-21B")
      (footprint "eagle-import:1206")
      (libsource (lib "eagle-import") (part "PT15-21B"))
    )
    (comp (ref "U$201")
      (value "PT15-21B")
      (footprint "eagle-import:1206")
      (libsource (lib "eagle-import") (part "PT15-21B"))
    )
    (comp (ref "U$202")
      (value "PT15-21B")
      (footprint "eagle-import:1206")
      (libsource (lib "eagle-import") (part "PT15-21B"))
    )
    (comp (ref "U$203")
      (value "PT15-21B")
      (footprint "eagle-import:1206")
      (libsource (lib "eagle-import") (part "PT15-21B"))
    )
    (comp (ref "U$204")
      (value "PT15-21B")
      (footprint "eagle-import:1206")
      (libsource (lib "eagle-import") (part "PT15-21B"))
    )
    (comp (ref "U$205")
      (value "PT15-21B")
      (footprint "eagle-import:1206")
      (libsource (lib "eagle-import") (part "PT15-21B"))
    )
    (comp (ref "U$206")
      (value "PT15-21B")
      (footprint "eagle-import:1206")
      (libsource (lib "eagle-import") (part "PT15-21B"))
    )
    (comp (ref "U$207")
      (value "PT15-21B")
      (footprint "eagle-import:1206")
      (libsource (lib "eagle-import") (part "PT15-21B"))
    )
    (comp (ref "U$208")
      (value "PT15-21B")
      (footprint "eagle-import:1206")
      (libsource (lib "eagle-import") (part "PT15-21B"))
    )
    (comp (ref "U$209")
      (value "PT15-21B")
      (footprint "eagle-import:1206")
      (libsource (lib "eagle-import") (part "PT15-21B"))
    )
    (comp (ref "U$210")
      (value "PT15-21B")
      (footprint "eagle-import:1206")
      (libsource (lib "eagle-import") (part "PT15-21B"))
    )
    (comp (ref "U$211")
      (value "PT15-21B")
      (footprint "eagle-import:1206")
      (libsource (lib "eagle-import") (part "PT15-21B"))
    )
    (comp (ref "U$212")
      (value "PT15-21B")
      (footprint "eagle-import:1206")
      (libsource (lib "eagle-import") (part "PT15-21B"))
    )
    (comp (ref "U$213")
      (value "PT15-21B")
      (footprint "eagle-import:1206")
      (libsource (lib "eagle-import") (part "PT15-21B"))
    )
    (comp (ref "U$214")
      (value "PT15-21B")
      (footprint "eagle-import:1206")
      (libsource (lib "eagle-import") (part "PT15-21B"))
    )
    (comp (ref "U$215")
      (value "PT15-21B")
      (footprint "eagle-import:1206")
      (libsource (lib "eagle-import") (part "PT15-21B"))
    )
    (comp (ref "U$216")
      (value "PT15-21B")
      (footprint "eagle-import:1206")
      (libsource (lib "eagle-import") (part "PT15-21B"))
    )
    (comp (ref "U$217")
      (value "PT15-21B")
      (footprint "eagle-import:1206")
      (libsource (lib "eagle-import") (part "PT15-21B"))
    )
    (comp (ref "U$218")
      (value "PT15-21B")
      (footprint "eagle-import:1206")
      (libsource (lib "eagle-import") (part "PT15-21B"))
    )
    (comp (ref "U$219")
      (value "PT15-21B")
      (footprint "eagle-import:1206")
      (libsource (lib "eagle-import") (part "PT15-21B"))
    )
    (comp (ref "U$220")
      (value "PT15-21B")
      (footprint "eagle-import:1206")
      (libsource (lib "eagle-import") (part "PT15-21B"))
    )
    (comp (ref "U$221")
      (value "PT15-21B")
      (footprint "eagle-import:1206")
      (libsource (lib "eagle-import") (part "PT15-21B"))
    )
    (comp (ref "U$222")
      (value "PT15-21B")
      (footprint "eagle-import:1206")
      (libsource (lib "eagle-import") (part "PT15-21B"))
    )
    (comp (ref "U$223")
      (value "PT15-21B")
      (footprint "eagle-import:1206")
      (libsource (lib "eagle-import") (part "PT15-21B"))
    )
    (comp (ref "U$224")
      (value "PT15-21B")
      (footprint "eagle-import:1206")
      (libsource (lib "eagle-import") (part "PT15-21B"))
    )
    (comp (ref "U$225")
      (value "PT15-21B")
      (footprint "eagle-import:1206")
      (libsource (lib "eagle-import") (part "PT15-21B"))
    )
    (comp (ref "U$226")
      (value "PT15-21B")
      (footprint "eagle-import:1206")
      (libsource (lib "eagle-import") (part "PT15-21B"))
    )
    (comp (ref "U$227")
      (value "PT15-21B")
      (footprint "eagle-import:1206")
      (libsource (lib "eagle-import") (part "PT15-21B"))
    )
    (comp (ref "U$228")
      (value "PT15-21B")
      (footprint "eagle-import:1206")
      (libsource (lib "eagle-import") (part "PT15-21B"))
    )
    (comp (ref "U$229")
      (value "PT15-21B")
      (footprint "eagle-import:1206")
      (libsource (lib "eagle-import") (part "PT15-21B"))
    )
    (comp (ref "U$230")
      (value "PT15-21B")
      (footprint "eagle-import:1206")
      (libsource (lib "eagle-import") (part "PT15-21B"))
    )
    (comp (ref "U$231")
      (value "PT15-21B")
      (footprint "eagle-import:1206")
      (libsource (lib "eagle-import") (part "PT15-21B"))
    )
    (comp (ref "U$232")
      (value "PT15-21B")
      (footprint "eagle-import:1206")
      (libsource (lib "eagle-import") (part "PT15-21B"))
    )
    (comp (ref "U$233")
      (value "PT15-21B")
      (footprint "eagle-import:1206")
      (libsource (lib "eagle-import") (part "PT15-21B"))
    )
    (comp (ref "U$234")
      (value "PT15-21B")
      (footprint "eagle-import:1206")
      (libsource (lib "eagle-import") (part "PT15-21B"))
    )
    (comp (ref "U$235")
      (value "PT15-21B")
      (footprint "eagle-import:1206")
      (libsource (lib "eagle-import") (part "PT15-21B"))
    )
    (comp (ref "U$236")
      (value "PT15-21B")
      (footprint "eagle-import:1206")
      (libsource (lib "eagle-import") (part "PT15-21B"))
    )
    (comp (ref "U$237")
      (value "PT15-21B")
      (footprint "eagle-import:1206")
      (libsource (lib "eagle-import") (part "PT15-21B"))
    )
    (comp (ref "U$238")
      (value "PT15-21B")
      (footprint "eagle-import:1206")
      (libsource (lib "eagle-import") (part "PT15-21B"))
    )
    (comp (ref "U$239")
      (value "PT15-21B")
      (footprint "eagle-import:1206")
      (libsource (lib "eagle-import") (part "PT15-21B"))
    )
    (comp (ref "U$240")
      (value "PT15-21B")
      (footprint "eagle-import:1206")
      (libsource (lib "eagle-import") (part "PT15-21B"))
    )
    (comp (ref "U$241")
      (value "PT15-21B")
      (footprint "eagle-import:1206")
      (libsource (lib "eagle-import") (part "PT15-21B"))
    )
    (comp (ref "U$242")
      (value "PT15-21B")
      (footprint "eagle-import:1206")
      (libsource (lib "eagle-import") (part "PT15-21B"))
    )
    (comp (ref "U$243")
      (value "PT15-21B")
      (footprint "eagle-import:1206")
      (libsource (lib "eagle-import") (part "PT15-21B"))
    )
    (comp (ref "U$244")
      (value "PT15-21B")
      (footprint "eagle-import:1206")
      (libsource (lib "eagle-import") (part "PT15-21B"))
    )
    (comp (ref "U$245")
      (value "PT15-21B")
      (footprint "eagle-import:1206")
      (libsource (lib "eagle-import") (part "PT15-21B"))
    )
    (comp (ref "U$246")
      (value "PT15-21B")
      (footprint "eagle-import:1206")
      (libsource (lib "eagle-import") (part "PT15-21B"))
    )
    (comp (ref "U$247")
      (value "PT15-21B")
      (footprint "eagle-import:1206")
      (libsource (lib "eagle-import") (part "PT15-21B"))
    )
    (comp (ref "U$248")
      (value "PT15-21B")
      (footprint "eagle-import:1206")
      (libsource (lib "eagle-import") (part "PT15-21B"))
    )
    (comp (ref "U$249")
      (value "PT15-21B")
      (footprint "eagle-import:1206")
      (libsource (lib "eagle-import") (part "PT15-21B"))
    )
    (comp (ref "U$250")
      (value "PT15-21B")
      (footprint "eagle-import:1206")
      (libsource (lib "eagle-import") (part "PT15-21B"))
    )
    (comp (ref "U$251")
      (value "PT15-21B")
      (footprint "eagle-import:1206")
      (libsource (lib "eagle-import") (part "PT15-21B"))
    )
    (comp (ref "U$252")
      (value "PT15-21B")
      (footprint "eagle-import:1206")
      (libsource (lib "eagle-import") (part "PT15-21B"))
    )
    (comp (ref "U$253")
      (value "PT15-21B")
      (footprint "eagle-import:1206")
      (libsource (lib "eagle-import") (part "PT15-21B"))
    )
    (comp (ref "U$254")
      (value "PT15-21B")
      (footprint "eagle-import:1206")
      (libsource (lib "eagle-import") (part "PT15-21B"))
    )
    (comp (ref "U$255")
      (value "PT15-21B")
      (footprint "eagle-import:1206")
      (libsource (lib "eagle-import") (part "PT15-21B"))
    )
    (comp (ref "U$256")
      (value "PT15-21B")
      (footprint "eagle-import:1206")
      (libsource (lib "eagle-import") (part "PT15-21B"))
    )
    (comp (ref "U$257")
      (value "PT15-21B")
      (footprint "eagle-import:1206")
      (libsource (lib "eagle-import") (part "PT15-21B"))
    )
  )
  (nets
    (net (code "1") (name "/C1") (class "Default")
      (node (ref "IC2") (pin "1") (pinfunction "0_1") (pintype "output"))
      (node (ref "R19") (pin "1") (pinfunction "1_1") (pintype "passive"))
    )
    (net (code "2") (name "/C2") (class "Default")
      (node (ref "IC2") (pin "2") (pinfunction "1_2") (pintype "output"))
      (node (ref "R20") (pin "1") (pinfunction "1_1") (pintype "passive"))
    )
    (net (code "3") (name "/C3") (class "Default")
      (node (ref "IC2") (pin "3") (pinfunction "2_3") (pintype "output"))
      (node (ref "R21") (pin "1") (pinfunction "1_1") (pintype "passive"))
    )
    (net (code "4") (name "/C4") (class "Default")
      (node (ref "IC2") (pin "4") (pinfunction "3_4") (pintype "output"))
      (node (ref "R22") (pin "1") (pinfunction "1_1") (pintype "passive"))
    )
    (net (code "5") (name "/C5") (class "Default")
      (node (ref "IC2") (pin "5") (pinfunction "4_5") (pintype "output"))
      (node (ref "R23") (pin "1") (pinfunction "1_1") (pintype "passive"))
    )
    (net (code "6") (name "/C6") (class "Default")
      (node (ref "IC2") (pin "6") (pinfunction "5_6") (pintype "output"))
      (node (ref "R24") (pin "1") (pinfunction "1_1") (pintype "passive"))
    )
    (net (code "7") (name "/C7") (class "Default")
      (node (ref "IC2") (pin "7") (pinfunction "6_7") (pintype "output"))
      (node (ref "R25") (pin "1") (pinfunction "1_1") (pintype "passive"))
    )
    (net (code "8") (name "/C8") (class "Default")
      (node (ref "IC2") (pin "8") (pinfunction "7_8") (pintype "output"))
      (node (ref "R26") (pin "1") (pinfunction "1_1") (pintype "passive"))
    )
    (net (code "9") (name "/C9") (class "Default")
      (node (ref "IC2") (pin "9") (pinfunction "8_9") (pintype "output"))
      (node (ref "R27") (pin "1") (pinfunction "1_1") (pintype "passive"))
    )
    (net (code "10") (name "/C10") (class "Default")
      (node (ref "IC2") (pin "10") (pinfunction "9_10") (pintype "output"))
      (node (ref "R28") (pin "1") (pinfunction "1_1") (pintype "passive"))
    )
    (net (code "11") (name "/C11") (class "Default")
      (node (ref "IC2") (pin "11") (pinfunction "10_11") (pintype "output"))
      (node (ref "R29") (pin "1") (pinfunction "1_1") (pintype "passive"))
    )
    (net (code "12") (name "/C12") (class "Default")
      (node (ref "IC2") (pin "13") (pinfunction "11_13") (pintype "output"))
      (node (ref "R30") (pin "1") (pinfunction "1_1") (pintype "passive"))
    )
    (net (code "13") (name "/C13") (class "Default")
      (node (ref "IC2") (pin "14") (pinfunction "12_14") (pintype "output"))
      (node (ref "R31") (pin "1") (pinfunction "1_1") (pintype "passive"))
    )
    (net (code "14") (name "/C14") (class "Default")
      (node (ref "IC2") (pin "15") (pinfunction "13_15") (pintype "output"))
      (node (ref "R32") (pin "1") (pinfunction "1_1") (pintype "passive"))
    )
    (net (code "15") (name "/C15") (class "Default")
      (node (ref "IC2") (pin "16") (pinfunction "14_16") (pintype "output"))
      (node (ref "R33") (pin "1") (pinfunction "1_1") (pintype "passive"))
    )
    (net (code "16") (name "/C16") (class "Default")
      (node (ref "IC2") (pin "17") (pinfunction "15_17") (pintype "output"))
      (node (ref "R34") (pin "1") (pinfunction "1_1") (pintype "passive"))
    )
    (net (code "17") (name "/DIG_OUT") (class "Default")
      (node (ref "IC1") (pin "1") (pinfunction "OUT1_1") (pintype "output"))
    )
    (net (code "18") (name "/EN") (class "Default")
      (node (ref "U$5") (pin "15") (pinfunction "EN_15") (pintype "input"))
    )
    (net (code "19") (name "/P1") (class "Default")
      (node (ref "D1") (pin "2") (pinfunction "A_2") (pintype "passive"))
      (node (ref "D100") (pin "2") (pinfunction "A_2") (pintype "passive"))
      (node (ref "D113") (pin "2") (pinfunction "A_2") (pintype "passive"))
      (node (ref "D116") (pin "2") (pinfunction "A_2") (pintype "passive"))
      (node (ref "D17") (pin "2") (pinfunction "A_2") (pintype "passive"))
      (node (ref "D20") (pin "2") (pinfunction "A_2") (pintype "passive"))
      (node (ref "D33") (pin "2") (pinfunction "A_2") (pintype "passive"))
      (node (ref "D36") (pin "2") (pinfunction "A_2") (pintype "passive"))
      (node (ref "D4") (pin "2") (pinfunction "A_2") (pintype "passive"))
      (node (ref "D49") (pin "2") (pinfunction "A_2") (pintype "passive"))
      (node (ref "D52") (pin "2") (pinfunction "A_2") (pintype "passive"))
      (node (ref "D65") (pin "2") (pinfunction "A_2") (pintype "passive"))
      (node (ref "D68") (pin "2") (pinfunction "A_2") (pintype "passive"))
      (node (ref "D81") (pin "2") (pinfunction "A_2") (pintype "passive"))
      (node (ref "D84") (pin "2") (pinfunction "A_2") (pintype "passive"))
      (node (ref "D97") (pin "2") (pinfunction "A_2") (pintype "passive"))
      (node (ref "Q1") (pin "3") (pinfunction "C_3") (pintype "passive"))
    )
    (net (code "20") (name "/P2") (class "Default")
      (node (ref "D114") (pin "2") (pinfunction "A_2") (pintype "passive"))
      (node (ref "D115") (pin "2") (pinfunction "A_2") (pintype "passive"))
      (node (ref "D18") (pin "2") (pinfunction "A_2") (pintype "passive"))
      (node (ref "D19") (pin "2") (pinfunction "A_2") (pintype "passive"))
      (node (ref "D2") (pin "2") (pinfunction "A_2") (pintype "passive"))
      (node (ref "D3") (pin "2") (pinfunction "A_2") (pintype "passive"))
      (node (ref "D34") (pin "2") (pinfunction "A_2") (pintype "passive"))
      (node (ref "D35") (pin "2") (pinfunction "A_2") (pintype "passive"))
      (node (ref "D50") (pin "2") (pinfunction "A_2") (pintype "passive"))
      (node (ref "D51") (pin "2") (pinfunction "A_2") (pintype "passive"))
      (node (ref "D66") (pin "2") (pinfunction "A_2") (pintype "passive"))
      (node (ref "D67") (pin "2") (pinfunction "A_2") (pintype "passive"))
      (node (ref "D82") (pin "2") (pinfunction "A_2") (pintype "passive"))
      (node (ref "D83") (pin "2") (pinfunction "A_2") (pintype "passive"))
      (node (ref "D98") (pin "2") (pinfunction "A_2") (pintype "passive"))
      (node (ref "D99") (pin "2") (pinfunction "A_2") (pintype "passive"))
      (node (ref "Q2") (pin "3") (pinfunction "C_3") (pintype "passive"))
    )
    (net (code "21") (name "/P3") (class "Default")
      (node (ref "D101") (pin "2") (pinfunction "A_2") (pintype "passive"))
      (node (ref "D104") (pin "2") (pinfunction "A_2") (pintype "passive"))
      (node (ref "D117") (pin "2") (pinfunction "A_2") (pintype "passive"))
      (node (ref "D120") (pin "2") (pinfunction "A_2") (pintype "passive"))
      (node (ref "D21") (pin "2") (pinfunction "A_2") (pintype "passive"))
      (node (ref "D24") (pin "2") (pinfunction "A_2") (pintype "passive"))
      (node (ref "D37") (pin "2") (pinfunction "A_2") (pintype "passive"))
      (node (ref "D40") (pin "2") (pinfunction "A_2") (pintype "passive"))
      (node (ref "D5") (pin "2") (pinfunction "A_2") (pintype "passive"))
      (node (ref "D53") (pin "2") (pinfunction "A_2") (pintype "passive"))
      (node (ref "D56") (pin "2") (pinfunction "A_2") (pintype "passive"))
      (node (ref "D69") (pin "2") (pinfunction "A_2") (pintype "passive"))
      (node (ref "D72") (pin "2") (pinfunction "A_2") (pintype "passive"))
      (node (ref "D8") (pin "2") (pinfunction "A_2") (pintype "passive"))
      (node (ref "D85") (pin "2") (pinfunction "A_2") (pintype "passive"))
      (node (ref "D88") (pin "2") (pinfunction "A_2") (pintype "passive"))
      (node (ref "Q3") (pin "3") (pinfunction "C_3") (pintype "passive"))
    )
    (net (code "22") (name "/P4") (class "Default")
      (node (ref "D102") (pin "2") (pinfunction "A_2") (pintype "passive"))
      (node (ref "D103") (pin "2") (pinfunction "A_2") (pintype "passive"))
      (node (ref "D118") (pin "2") (pinfunction "A_2") (pintype "passive"))
      (node (ref "D119") (pin "2") (pinfunction "A_2") (pintype "passive"))
      (node (ref "D22") (pin "2") (pinfunction "A_2") (pintype "passive"))
      (node (ref "D23") (pin "2") (pinfunction "A_2") (pintype "passive"))
      (node (ref "D38") (pin "2") (pinfunction "A_2") (pintype "passive"))
      (node (ref "D39") (pin "2") (pinfunction "A_2") (pintype "passive"))
      (node (ref "D54") (pin "2") (pinfunction "A_2") (pintype "passive"))
      (node (ref "D55") (pin "2") (pinfunction "A_2") (pintype "passive"))
      (node (ref "D6") (pin "2") (pinfunction "A_2") (pintype "passive"))
      (node (ref "D7") (pin "2") (pinfunction "A_2") (pintype "passive"))
      (node (ref "D70") (pin "2") (pinfunction "A_2") (pintype "passive"))
      (node (ref "D71") (pin "2") (pinfunction "A_2") (pintype "passive"))
      (node (ref "D86") (pin "2") (pinfunction "A_2") (pintype "passive"))
      (node (ref "D87") (pin "2") (pinfunction "A_2") (pintype "passive"))
      (node (ref "Q4") (pin "3") (pinfunction "C_3") (pintype "passive"))
    )
    (net (code "23") (name "/P5") (class "Default")
      (node (ref "D105") (pin "2") (pinfunction "A_2") (pintype "passive"))
      (node (ref "D108") (pin "2") (pinfunction "A_2") (pintype "passive"))
      (node (ref "D12") (pin "2") (pinfunction "A_2") (pintype "passive"))
      (node (ref "D121") (pin "2") (pinfunction "A_2") (pintype "passive"))
      (node (ref "D124") (pin "2") (pinfunction "A_2") (pintype "passive"))
      (node (ref "D25") (pin "2") (pinfunction "A_2") (pintype "passive"))
      (node (ref "D28") (pin "2") (pinfunction "A_2") (pintype "passive"))
      (node (ref "D41") (pin "2") (pinfunction "A_2") (pintype "passive"))
      (node (ref "D44") (pin "2") (pinfunction "A_2") (pintype "passive"))
      (node (ref "D57") (pin "2") (pinfunction "A_2") (pintype "passive"))
      (node (ref "D60") (pin "2") (pinfunction "A_2") (pintype "passive"))
      (node (ref "D73") (pin "2") (pinfunction "A_2") (pintype "passive"))
      (node (ref "D76") (pin "2") (pinfunction "A_2") (pintype "passive"))
      (node (ref "D89") (pin "2") (pinfunction "A_2") (pintype "passive"))
      (node (ref "D9") (pin "2") (pinfunction "A_2") (pintype "passive"))
      (node (ref "D92") (pin "2") (pinfunction "A_2") (pintype "passive"))
      (node (ref "Q5") (pin "3") (pinfunction "C_3") (pintype "passive"))
    )
    (net (code "24") (name "/P6") (class "Default")
      (node (ref "D10") (pin "2") (pinfunction "A_2") (pintype "passive"))
      (node (ref "D106") (pin "2") (pinfunction "A_2") (pintype "passive"))
      (node (ref "D107") (pin "2") (pinfunction "A_2") (pintype "passive"))
      (node (ref "D11") (pin "2") (pinfunction "A_2") (pintype "passive"))
      (node (ref "D122") (pin "2") (pinfunction "A_2") (pintype "passive"))
      (node (ref "D123") (pin "2") (pinfunction "A_2") (pintype "passive"))
      (node (ref "D26") (pin "2") (pinfunction "A_2") (pintype "passive"))
      (node (ref "D27") (pin "2") (pinfunction "A_2") (pintype "passive"))
      (node (ref "D42") (pin "2") (pinfunction "A_2") (pintype "passive"))
      (node (ref "D43") (pin "2") (pinfunction "A_2") (pintype "passive"))
      (node (ref "D58") (pin "2") (pinfunction "A_2") (pintype "passive"))
      (node (ref "D59") (pin "2") (pinfunction "A_2") (pintype "passive"))
      (node (ref "D74") (pin "2") (pinfunction "A_2") (pintype "passive"))
      (node (ref "D75") (pin "2") (pinfunction "A_2") (pintype "passive"))
      (node (ref "D90") (pin "2") (pinfunction "A_2") (pintype "passive"))
      (node (ref "D91") (pin "2") (pinfunction "A_2") (pintype "passive"))
      (node (ref "Q6") (pin "3") (pinfunction "C_3") (pintype "passive"))
    )
    (net (code "25") (name "/P7") (class "Default")
      (node (ref "D109") (pin "2") (pinfunction "A_2") (pintype "passive"))
      (node (ref "D112") (pin "2") (pinfunction "A_2") (pintype "passive"))
      (node (ref "D125") (pin "2") (pinfunction "A_2") (pintype "passive"))
      (node (ref "D128") (pin "2") (pinfunction "A_2") (pintype "passive"))
      (node (ref "D13") (pin "2") (pinfunction "A_2") (pintype "passive"))
      (node (ref "D16") (pin "2") (pinfunction "A_2") (pintype "passive"))
      (node (ref "D29") (pin "2") (pinfunction "A_2") (pintype "passive"))
      (node (ref "D32") (pin "2") (pinfunction "A_2") (pintype "passive"))
      (node (ref "D45") (pin "2") (pinfunction "A_2") (pintype "passive"))
      (node (ref "D48") (pin "2") (pinfunction "A_2") (pintype "passive"))
      (node (ref "D61") (pin "2") (pinfunction "A_2") (pintype "passive"))
      (node (ref "D64") (pin "2") (pinfunction "A_2") (pintype "passive"))
      (node (ref "D77") (pin "2") (pinfunction "A_2") (pintype "passive"))
      (node (ref "D80") (pin "2") (pinfunction "A_2") (pintype "passive"))
      (node (ref "D93") (pin "2") (pinfunction "A_2") (pintype "passive"))
      (node (ref "D96") (pin "2") (pinfunction "A_2") (pintype "passive"))
      (node (ref "Q7") (pin "3") (pinfunction "C_3") (pintype "passive"))
    )
    (net (code "26") (name "/P8") (class "Default")
      (node (ref "D110") (pin "2") (pinfunction "A_2") (pintype "passive"))
      (node (ref "D111") (pin "2") (pinfunction "A_2") (pintype "passive"))
      (node (ref "D126") (pin "2") (pinfunction "A_2") (pintype "passive"))
      (node (ref "D127") (pin "2") (pinfunction "A_2") (pintype "passive"))
      (node (ref "D14") (pin "2") (pinfunction "A_2") (pintype "passive"))
      (node (ref "D15") (pin "2") (pinfunction "A_2") (pintype "passive"))
      (node (ref "D30") (pin "2") (pinfunction "A_2") (pintype "passive"))
      (node (ref "D31") (pin "2") (pinfunction "A_2") (pintype "passive"))
      (node (ref "D46") (pin "2") (pinfunction "A_2") (pintype "passive"))
      (node (ref "D47") (pin "2") (pinfunction "A_2") (pintype "passive"))
      (node (ref "D62") (pin "2") (pinfunction "A_2") (pintype "passive"))
      (node (ref "D63") (pin "2") (pinfunction "A_2") (pintype "passive"))
      (node (ref "D78") (pin "2") (pinfunction "A_2") (pintype "passive"))
      (node (ref "D79") (pin "2") (pinfunction "A_2") (pintype "passive"))
      (node (ref "D94") (pin "2") (pinfunction "A_2") (pintype "passive"))
      (node (ref "D95") (pin "2") (pinfunction "A_2") (pintype "passive"))
      (node (ref "Q8") (pin "3") (pinfunction "C_3") (pintype "passive"))
    )
    (net (code "27") (name "/P9") (class "Default")
      (node (ref "D129") (pin "2") (pinfunction "A_2") (pintype "passive"))
      (node (ref "D132") (pin "2") (pinfunction "A_2") (pintype "passive"))
      (node (ref "D145") (pin "2") (pinfunction "A_2") (pintype "passive"))
      (node (ref "D148") (pin "2") (pinfunction "A_2") (pintype "passive"))
      (node (ref "D161") (pin "2") (pinfunction "A_2") (pintype "passive"))
      (node (ref "D164") (pin "2") (pinfunction "A_2") (pintype "passive"))
      (node (ref "D177") (pin "2") (pinfunction "A_2") (pintype "passive"))
      (node (ref "D180") (pin "2") (pinfunction "A_2") (pintype "passive"))
      (node (ref "D193") (pin "2") (pinfunction "A_2") (pintype "passive"))
      (node (ref "D196") (pin "2") (pinfunction "A_2") (pintype "passive"))
      (node (ref "D209") (pin "2") (pinfunction "A_2") (pintype "passive"))
      (node (ref "D212") (pin "2") (pinfunction "A_2") (pintype "passive"))
      (node (ref "D225") (pin "2") (pinfunction "A_2") (pintype "passive"))
      (node (ref "D228") (pin "2") (pinfunction "A_2") (pintype "passive"))
      (node (ref "D241") (pin "2") (pinfunction "A_2") (pintype "passive"))
      (node (ref "D244") (pin "2") (pinfunction "A_2") (pintype "passive"))
      (node (ref "Q9") (pin "3") (pinfunction "C_3") (pintype "passive"))
    )
    (net (code "28") (name "/P10") (class "Default")
      (node (ref "D130") (pin "2") (pinfunction "A_2") (pintype "passive"))
      (node (ref "D131") (pin "2") (pinfunction "A_2") (pintype "passive"))
      (node (ref "D146") (pin "2") (pinfunction "A_2") (pintype "passive"))
      (node (ref "D147") (pin "2") (pinfunction "A_2") (pintype "passive"))
      (node (ref "D162") (pin "2") (pinfunction "A_2") (pintype "passive"))
      (node (ref "D163") (pin "2") (pinfunction "A_2") (pintype "passive"))
      (node (ref "D178") (pin "2") (pinfunction "A_2") (pintype "passive"))
      (node (ref "D179") (pin "2") (pinfunction "A_2") (pintype "passive"))
      (node (ref "D194") (pin "2") (pinfunction "A_2") (pintype "passive"))
      (node (ref "D195") (pin "2") (pinfunction "A_2") (pintype "passive"))
      (node (ref "D210") (pin "2") (pinfunction "A_2") (pintype "passive"))
      (node (ref "D211") (pin "2") (pinfunction "A_2") (pintype "passive"))
      (node (ref "D226") (pin "2") (pinfunction "A_2") (pintype "passive"))
      (node (ref "D227") (pin "2") (pinfunction "A_2") (pintype "passive"))
      (node (ref "D242") (pin "2") (pinfunction "A_2") (pintype "passive"))
      (node (ref "D243") (pin "2") (pinfunction "A_2") (pintype "passive"))
      (node (ref "Q10") (pin "3") (pinfunction "C_3") (pintype "passive"))
    )
    (net (code "29") (name "/P11") (class "Default")
      (node (ref "D133") (pin "2") (pinfunction "A_2") (pintype "passive"))
      (node (ref "D136") (pin "2") (pinfunction "A_2") (pintype "passive"))
      (node (ref "D149") (pin "2") (pinfunction "A_2") (pintype "passive"))
      (node (ref "D152") (pin "2") (pinfunction "A_2") (pintype "passive"))
      (node (ref "D165") (pin "2") (pinfunction "A_2") (pintype "passive"))
      (node (ref "D168") (pin "2") (pinfunction "A_2") (pintype "passive"))
      (node (ref "D181") (pin "2") (pinfunction "A_2") (pintype "passive"))
      (node (ref "D184") (pin "2") (pinfunction "A_2") (pintype "passive"))
      (node (ref "D197") (pin "2") (pinfunction "A_2") (pintype "passive"))
      (node (ref "D200") (pin "2") (pinfunction "A_2") (pintype "passive"))
      (node (ref "D213") (pin "2") (pinfunction "A_2") (pintype "passive"))
      (node (ref "D216") (pin "2") (pinfunction "A_2") (pintype "passive"))
      (node (ref "D229") (pin "2") (pinfunction "A_2") (pintype "passive"))
      (node (ref "D232") (pin "2") (pinfunction "A_2") (pintype "passive"))
      (node (ref "D245") (pin "2") (pinfunction "A_2") (pintype "passive"))
      (node (ref "D248") (pin "2") (pinfunction "A_2") (pintype "passive"))
      (node (ref "Q11") (pin "3") (pinfunction "C_3") (pintype "passive"))
    )
    (net (code "30") (name "/P12") (class "Default")
      (node (ref "D134") (pin "2") (pinfunction "A_2") (pintype "passive"))
      (node (ref "D135") (pin "2") (pinfunction "A_2") (pintype "passive"))
      (node (ref "D150") (pin "2") (pinfunction "A_2") (pintype "passive"))
      (node (ref "D151") (pin "2") (pinfunction "A_2") (pintype "passive"))
      (node (ref "D166") (pin "2") (pinfunction "A_2") (pintype "passive"))
      (node (ref "D167") (pin "2") (pinfunction "A_2") (pintype "passive"))
      (node (ref "D182") (pin "2") (pinfunction "A_2") (pintype "passive"))
      (node (ref "D183") (pin "2") (pinfunction "A_2") (pintype "passive"))
      (node (ref "D198") (pin "2") (pinfunction "A_2") (pintype "passive"))
      (node (ref "D199") (pin "2") (pinfunction "A_2") (pintype "passive"))
      (node (ref "D214") (pin "2") (pinfunction "A_2") (pintype "passive"))
      (node (ref "D215") (pin "2") (pinfunction "A_2") (pintype "passive"))
      (node (ref "D230") (pin "2") (pinfunction "A_2") (pintype "passive"))
      (node (ref "D231") (pin "2") (pinfunction "A_2") (pintype "passive"))
      (node (ref "D246") (pin "2") (pinfunction "A_2") (pintype "passive"))
      (node (ref "D247") (pin "2") (pinfunction "A_2") (pintype "passive"))
      (node (ref "Q12") (pin "3") (pinfunction "C_3") (pintype "passive"))
    )
    (net (code "31") (name "/P13") (class "Default")
      (node (ref "D137") (pin "2") (pinfunction "A_2") (pintype "passive"))
      (node (ref "D140") (pin "2") (pinfunction "A_2") (pintype "passive"))
      (node (ref "D153") (pin "2") (pinfunction "A_2") (pintype "passive"))
      (node (ref "D156") (pin "2") (pinfunction "A_2") (pintype "passive"))
      (node (ref "D169") (pin "2") (pinfunction "A_2") (pintype "passive"))
      (node (ref "D172") (pin "2") (pinfunction "A_2") (pintype "passive"))
      (node (ref "D185") (pin "2") (pinfunction "A_2") (pintype "passive"))
      (node (ref "D188") (pin "2") (pinfunction "A_2") (pintype "passive"))
      (node (ref "D201") (pin "2") (pinfunction "A_2") (pintype "passive"))
      (node (ref "D204") (pin "2") (pinfunction "A_2") (pintype "passive"))
      (node (ref "D217") (pin "2") (pinfunction "A_2") (pintype "passive"))
      (node (ref "D220") (pin "2") (pinfunction "A_2") (pintype "passive"))
      (node (ref "D233") (pin "2") (pinfunction "A_2") (pintype "passive"))
      (node (ref "D236") (pin "2") (pinfunction "A_2") (pintype "passive"))
      (node (ref "D249") (pin "2") (pinfunction "A_2") (pintype "passive"))
      (node (ref "D252") (pin "2") (pinfunction "A_2") (pintype "passive"))
      (node (ref "Q13") (pin "3") (pinfunction "C_3") (pintype "passive"))
    )
    (net (code "32") (name "/P14") (class "Default")
      (node (ref "D138") (pin "2") (pinfunction "A_2") (pintype "passive"))
      (node (ref "D139") (pin "2") (pinfunction "A_2") (pintype "passive"))
      (node (ref "D154") (pin "2") (pinfunction "A_2") (pintype "passive"))
      (node (ref "D155") (pin "2") (pinfunction "A_2") (pintype "passive"))
      (node (ref "D170") (pin "2") (pinfunction "A_2") (pintype "passive"))
      (node (ref "D171") (pin "2") (pinfunction "A_2") (pintype "passive"))
      (node (ref "D186") (pin "2") (pinfunction "A_2") (pintype "passive"))
      (node (ref "D187") (pin "2") (pinfunction "A_2") (pintype "passive"))
      (node (ref "D202") (pin "2") (pinfunction "A_2") (pintype "passive"))
      (node (ref "D203") (pin "2") (pinfunction "A_2") (pintype "passive"))
      (node (ref "D218") (pin "2") (pinfunction "A_2") (pintype "passive"))
      (node (ref "D219") (pin "2") (pinfunction "A_2") (pintype "passive"))
      (node (ref "D234") (pin "2") (pinfunction "A_2") (pintype "passive"))
      (node (ref "D235") (pin "2") (pinfunction "A_2") (pintype "passive"))
      (node (ref "D250") (pin "2") (pinfunction "A_2") (pintype "passive"))
      (node (ref "D251") (pin "2") (pinfunction "A_2") (pintype "passive"))
      (node (ref "Q14") (pin "3") (pinfunction "C_3") (pintype "passive"))
    )
    (net (code "33") (name "/P15") (class "Default")
      (node (ref "D141") (pin "2") (pinfunction "A_2") (pintype "passive"))
      (node (ref "D144") (pin "2") (pinfunction "A_2") (pintype "passive"))
      (node (ref "D157") (pin "2") (pinfunction "A_2") (pintype "passive"))
      (node (ref "D160") (pin "2") (pinfunction "A_2") (pintype "passive"))
      (node (ref "D173") (pin "2") (pinfunction "A_2") (pintype "passive"))
      (node (ref "D176") (pin "2") (pinfunction "A_2") (pintype "passive"))
      (node (ref "D189") (pin "2") (pinfunction "A_2") (pintype "passive"))
      (node (ref "D192") (pin "2") (pinfunction "A_2") (pintype "passive"))
      (node (ref "D205") (pin "2") (pinfunction "A_2") (pintype "passive"))
      (node (ref "D208") (pin "2") (pinfunction "A_2") (pintype "passive"))
      (node (ref "D221") (pin "2") (pinfunction "A_2") (pintype "passive"))
      (node (ref "D224") (pin "2") (pinfunction "A_2") (pintype "passive"))
      (node (ref "D237") (pin "2") (pinfunction "A_2") (pintype "passive"))
      (node (ref "D240") (pin "2") (pinfunction "A_2") (pintype "passive"))
      (node (ref "D253") (pin "2") (pinfunction "A_2") (pintype "passive"))
      (node (ref "D256") (pin "2") (pinfunction "A_2") (pintype "passive"))
      (node (ref "Q15") (pin "3") (pinfunction "C_3") (pintype "passive"))
    )
    (net (code "34") (name "/P16") (class "Default")
      (node (ref "D142") (pin "2") (pinfunction "A_2") (pintype "passive"))
      (node (ref "D143") (pin "2") (pinfunction "A_2") (pintype "passive"))
      (node (ref "D158") (pin "2") (pinfunction "A_2") (pintype "passive"))
      (node (ref "D159") (pin "2") (pinfunction "A_2") (pintype "passive"))
      (node (ref "D174") (pin "2") (pinfunction "A_2") (pintype "passive"))
      (node (ref "D175") (pin "2") (pinfunction "A_2") (pintype "passive"))
      (node (ref "D190") (pin "2") (pinfunction "A_2") (pintype "passive"))
      (node (ref "D191") (pin "2") (pinfunction "A_2") (pintype "passive"))
      (node (ref "D206") (pin "2") (pinfunction "A_2") (pintype "passive"))
      (node (ref "D207") (pin "2") (pinfunction "A_2") (pintype "passive"))
      (node (ref "D222") (pin "2") (pinfunction "A_2") (pintype "passive"))
      (node (ref "D223") (pin "2") (pinfunction "A_2") (pintype "passive"))
      (node (ref "D238") (pin "2") (pinfunction "A_2") (pintype "passive"))
      (node (ref "D239") (pin "2") (pinfunction "A_2") (pintype "passive"))
      (node (ref "D254") (pin "2") (pinfunction "A_2") (pintype "passive"))
      (node (ref "D255") (pin "2") (pinfunction "A_2") (pintype "passive"))
      (node (ref "Q16") (pin "3") (pinfunction "C_3") (pintype "passive"))
    )
    (net (code "35") (name "/S1") (class "Default")
      (node (ref "U$5") (pin "10") (pinfunction "S0_10") (pintype "input"))
    )
    (net (code "36") (name "/S2") (class "Default")
      (node (ref "U$5") (pin "11") (pinfunction "S1_11") (pintype "input"))
    )
    (net (code "37") (name "/S3") (class "Default")
      (node (ref "U$5") (pin "14") (pinfunction "S2_14") (pintype "input"))
    )
    (net (code "38") (name "/S4") (class "Default")
      (node (ref "U$5") (pin "13") (pinfunction "S3_13") (pintype "input"))
    )
    (net (code "39") (name "/S5") (class "Default")
      (node (ref "IC2") (pin "23") (pinfunction "A_23") (pintype "input"))
    )
    (net (code "40") (name "/S6") (class "Default")
      (node (ref "IC2") (pin "22") (pinfunction "B_22") (pintype "input"))
    )
    (net (code "41") (name "/S7") (class "Default")
      (node (ref "IC2") (pin "21") (pinfunction "C_21") (pintype "input"))
    )
    (net (code "42") (name "/S8") (class "Default")
      (node (ref "IC2") (pin "20") (pinfunction "D_20") (pintype "input"))
    )
    (net (code "43") (name "/THRESHOLD") (class "Default")
      (node (ref "IC1") (pin "3") (pinfunction "+IN1_3") (pintype "input"))
      (node (ref "IC1") (pin "6") (pinfunction "-IN2_6") (pintype "input"))
      (node (ref "IC1") (pin "7") (pinfunction "OUT2_7") (pintype "output"))
    )
    (net (code "44") (name "/Y1") (class "Default")
      (node (ref "R1") (pin "1") (pinfunction "1_1") (pintype "passive"))
      (node (ref "U$114") (pin "2") (pinfunction "E_2") (pintype "bidirectional"))
      (node (ref "U$115") (pin "2") (pinfunction "E_2") (pintype "bidirectional"))
      (node (ref "U$118") (pin "2") (pinfunction "E_2") (pintype "bidirectional"))
      (node (ref "U$119") (pin "2") (pinfunction "E_2") (pintype "bidirectional"))
      (node (ref "U$122") (pin "2") (pinfunction "E_2") (pintype "bidirectional"))
      (node (ref "U$123") (pin "2") (pinfunction "E_2") (pintype "bidirectional"))
      (node (ref "U$126") (pin "2") (pinfunction "E_2") (pintype "bidirectional"))
      (node (ref "U$127") (pin "2") (pinfunction "E_2") (pintype "bidirectional"))
      (node (ref "U$242") (pin "2") (pinfunction "E_2") (pintype "bidirectional"))
      (node (ref "U$243") (pin "2") (pinfunction "E_2") (pintype "bidirectional"))
      (node (ref "U$246") (pin "2") (pinfunction "E_2") (pintype "bidirectional"))
      (node (ref "U$247") (pin "2") (pinfunction "E_2") (pintype "bidirectional"))
      (node (ref "U$250") (pin "2") (pinfunction "E_2") (pintype "bidirectional"))
      (node (ref "U$251") (pin "2") (pinfunction "E_2") (pintype "bidirectional"))
      (node (ref "U$254") (pin "2") (pinfunction "E_2") (pintype "bidirectional"))
      (node (ref "U$255") (pin "2") (pinfunction "E_2") (pintype "bidirectional"))
      (node (ref "U$5") (pin "9") (pinfunction "CHAN0_9") (pintype "bidirectional"))
    )
    (net (code "45") (name "/Y2") (class "Default")
      (node (ref "R2") (pin "1") (pinfunction "1_1") (pintype "passive"))
      (node (ref "U$116") (pin "2") (pinfunction "E_2") (pintype "bidirectional"))
      (node (ref "U$117") (pin "2") (pinfunction "E_2") (pintype "bidirectional"))
      (node (ref "U$120") (pin "2") (pinfunction "E_2") (pintype "bidirectional"))
      (node (ref "U$121") (pin "2") (pinfunction "E_2") (pintype "bidirectional"))
      (node (ref "U$124") (pin "2") (pinfunction "E_2") (pintype "bidirectional"))
      (node (ref "U$125") (pin "2") (pinfunction "E_2") (pintype "bidirectional"))
      (node (ref "U$128") (pin "2") (pinfunction "E_2") (pintype "bidirectional"))
      (node (ref "U$129") (pin "2") (pinfunction "E_2") (pintype "bidirectional"))
      (node (ref "U$244") (pin "2") (pinfunction "E_2") (pintype "bidirectional"))
      (node (ref "U$245") (pin "2") (pinfunction "E_2") (pintype "bidirectional"))
      (node (ref "U$248") (pin "2") (pinfunction "E_2") (pintype "bidirectional"))
      (node (ref "U$249") (pin "2") (pinfunction "E_2") (pintype "bidirectional"))
      (node (ref "U$252") (pin "2") (pinfunction "E_2") (pintype "bidirectional"))
      (node (ref "U$253") (pin "2") (pinfunction "E_2") (pintype "bidirectional"))
      (node (ref "U$256") (pin "2") (pinfunction "E_2") (pintype "bidirectional"))
      (node (ref "U$257") (pin "2") (pinfunction "E_2") (pintype "bidirectional"))
      (node (ref "U$5") (pin "8") (pinfunction "CHAN1_8") (pintype "bidirectional"))
    )
    (net (code "46") (name "/Y3") (class "Default")
      (node (ref "R3") (pin "1") (pinfunction "1_1") (pintype "passive"))
      (node (ref "U$102") (pin "2") (pinfunction "E_2") (pintype "bidirectional"))
      (node (ref "U$103") (pin "2") (pinfunction "E_2") (pintype "bidirectional"))
      (node (ref "U$106") (pin "2") (pinfunction "E_2") (pintype "bidirectional"))
      (node (ref "U$107") (pin "2") (pinfunction "E_2") (pintype "bidirectional"))
      (node (ref "U$110") (pin "2") (pinfunction "E_2") (pintype "bidirectional"))
      (node (ref "U$111") (pin "2") (pinfunction "E_2") (pintype "bidirectional"))
      (node (ref "U$226") (pin "2") (pinfunction "E_2") (pintype "bidirectional"))
      (node (ref "U$227") (pin "2") (pinfunction "E_2") (pintype "bidirectional"))
      (node (ref "U$230") (pin "2") (pinfunction "E_2") (pintype "bidirectional"))
      (node (ref "U$231") (pin "2") (pinfunction "E_2") (pintype "bidirectional"))
      (node (ref "U$234") (pin "2") (pinfunction "E_2") (pintype "bidirectional"))
      (node (ref "U$235") (pin "2") (pinfunction "E_2") (pintype "bidirectional"))
      (node (ref "U$238") (pin "2") (pinfunction "E_2") (pintype "bidirectional"))
      (node (ref "U$239") (pin "2") (pinfunction "E_2") (pintype "bidirectional"))
      (node (ref "U$5") (pin "7") (pinfunction "CHAN2_7") (pintype "bidirectional"))
      (node (ref "U$98") (pin "2") (pinfunction "E_2") (pintype "bidirectional"))
      (node (ref "U$99") (pin "2") (pinfunction "E_2") (pintype "bidirectional"))
    )
    (net (code "47") (name "/Y4") (class "Default")
      (node (ref "R4") (pin "1") (pinfunction "1_1") (pintype "passive"))
      (node (ref "U$100") (pin "2") (pinfunction "E_2") (pintype "bidirectional"))
      (node (ref "U$101") (pin "2") (pinfunction "E_2") (pintype "bidirectional"))
      (node (ref "U$104") (pin "2") (pinfunction "E_2") (pintype "bidirectional"))
      (node (ref "U$105") (pin "2") (pinfunction "E_2") (pintype "bidirectional"))
      (node (ref "U$108") (pin "2") (pinfunction "E_2") (pintype "bidirectional"))
      (node (ref "U$109") (pin "2") (pinfunction "E_2") (pintype "bidirectional"))
      (node (ref "U$112") (pin "2") (pinfunction "E_2") (pintype "bidirectional"))
      (node (ref "U$113") (pin "2") (pinfunction "E_2") (pintype "bidirectional"))
      (node (ref "U$228") (pin "2") (pinfunction "E_2") (pintype "bidirectional"))
      (node (ref "U$229") (pin "2") (pinfunction "E_2") (pintype "bidirectional"))
      (node (ref "U$232") (pin "2") (pinfunction "E_2") (pintype "bidirectional"))
      (node (ref "U$233") (pin "2") (pinfunction "E_2") (pintype "bidirectional"))
      (node (ref "U$236") (pin "2") (pinfunction "E_2") (pintype "bidirectional"))
      (node (ref "U$237") (pin "2") (pinfunction "E_2") (pintype "bidirectional"))
      (node (ref "U$240") (pin "2") (pinfunction "E_2") (pintype "bidirectional"))
      (node (ref "U$241") (pin "2") (pinfunction "E_2") (pintype "bidirectional"))
      (node (ref "U$5") (pin "6") (pinfunction "CHAN3_6") (pintype "bidirectional"))
    )
    (net (code "48") (name "/Y5") (class "Default")
      (node (ref "R5") (pin "1") (pinfunction "1_1") (pintype "passive"))
      (node (ref "U$210") (pin "2") (pinfunction "E_2") (pintype "bidirectional"))
      (node (ref "U$211") (pin "2") (pinfunction "E_2") (pintype "bidirectional"))
      (node (ref "U$214") (pin "2") (pinfunction "E_2") (pintype "bidirectional"))
      (node (ref "U$215") (pin "2") (pinfunction "E_2") (pintype "bidirectional"))
      (node (ref "U$218") (pin "2") (pinfunction "E_2") (pintype "bidirectional"))
      (node (ref "U$219") (pin "2") (pinfunction "E_2") (pintype "bidirectional"))
      (node (ref "U$222") (pin "2") (pinfunction "E_2") (pintype "bidirectional"))
      (node (ref "U$223") (pin "2") (pinfunction "E_2") (pintype "bidirectional"))
      (node (ref "U$5") (pin "5") (pinfunction "CHAN4_5") (pintype "bidirectional"))
      (node (ref "U$82") (pin "2") (pinfunction "E_2") (pintype "bidirectional"))
      (node (ref "U$83") (pin "2") (pinfunction "E_2") (pintype "bidirectional"))
      (node (ref "U$86") (pin "2") (pinfunction "E_2") (pintype "bidirectional"))
      (node (ref "U$87") (pin "2") (pinfunction "E_2") (pintype "bidirectional"))
      (node (ref "U$90") (pin "2") (pinfunction "E_2") (pintype "bidirectional"))
      (node (ref "U$91") (pin "2") (pinfunction "E_2") (pintype "bidirectional"))
      (node (ref "U$94") (pin "2") (pinfunction "E_2") (pintype "bidirectional"))
      (node (ref "U$95") (pin "2") (pinfunction "E_2") (pintype "bidirectional"))
    )
    (net (code "49") (name "/Y6") (class "Default")
      (node (ref "R6") (pin "1") (pinfunction "1_1") (pintype "passive"))
      (node (ref "U$212") (pin "2") (pinfunction "E_2") (pintype "bidirectional"))
      (node (ref "U$213") (pin "2") (pinfunction "E_2") (pintype "bidirectional"))
      (node (ref "U$216") (pin "2") (pinfunction "E_2") (pintype "bidirectional"))
      (node (ref "U$217") (pin "2") (pinfunction "E_2") (pintype "bidirectional"))
      (node (ref "U$220") (pin "2") (pinfunction "E_2") (pintype "bidirectional"))
      (node (ref "U$221") (pin "2") (pinfunction "E_2") (pintype "bidirectional"))
      (node (ref "U$224") (pin "2") (pinfunction "E_2") (pintype "bidirectional"))
      (node (ref "U$225") (pin "2") (pinfunction "E_2") (pintype "bidirectional"))
      (node (ref "U$5") (pin "4") (pinfunction "CHAN5_4") (pintype "bidirectional"))
      (node (ref "U$84") (pin "2") (pinfunction "E_2") (pintype "bidirectional"))
      (node (ref "U$85") (pin "2") (pinfunction "E_2") (pintype "bidirectional"))
      (node (ref "U$88") (pin "2") (pinfunction "E_2") (pintype "bidirectional"))
      (node (ref "U$89") (pin "2") (pinfunction "E_2") (pintype "bidirectional"))
      (node (ref "U$92") (pin "2") (pinfunction "E_2") (pintype "bidirectional"))
      (node (ref "U$93") (pin "2") (pinfunction "E_2") (pintype "bidirectional"))
      (node (ref "U$96") (pin "2") (pinfunction "E_2") (pintype "bidirectional"))
      (node (ref "U$97") (pin "2") (pinfunction "E_2") (pintype "bidirectional"))
    )
    (net (code "50") (name "/Y7") (class "Default")
      (node (ref "R7") (pin "1") (pinfunction "1_1") (pintype "passive"))
      (node (ref "U$194") (pin "2") (pinfunction "E_2") (pintype "bidirectional"))
      (node (ref "U$195") (pin "2") (pinfunction "E_2") (pintype "bidirectional"))
      (node (ref "U$198") (pin "2") (pinfunction "E_2") (pintype "bidirectional"))
      (node (ref "U$199") (pin "2") (pinfunction "E_2") (pintype "bidirectional"))
      (node (ref "U$202") (pin "2") (pinfunction "E_2") (pintype "bidirectional"))
      (node (ref "U$203") (pin "2") (pinfunction "E_2") (pintype "bidirectional"))
      (node (ref "U$206") (pin "2") (pinfunction "E_2") (pintype "bidirectional"))
      (node (ref "U$207") (pin "2") (pinfunction "E_2") (pintype "bidirectional"))
      (node (ref "U$5") (pin "3") (pinfunction "CHAN6_3") (pintype "bidirectional"))
      (node (ref "U$66") (pin "2") (pinfunction "E_2") (pintype "bidirectional"))
      (node (ref "U$67") (pin "2") (pinfunction "E_2") (pintype "bidirectional"))
      (node (ref "U$70") (pin "2") (pinfunction "E_2") (pintype "bidirectional"))
      (node (ref "U$71") (pin "2") (pinfunction "E_2") (pintype "bidirectional"))
      (node (ref "U$74") (pin "2") (pinfunction "E_2") (pintype "bidirectional"))
      (node (ref "U$75") (pin "2") (pinfunction "E_2") (pintype "bidirectional"))
      (node (ref "U$78") (pin "2") (pinfunction "E_2") (pintype "bidirectional"))
      (node (ref "U$79") (pin "2") (pinfunction "E_2") (pintype "bidirectional"))
    )
    (net (code "51") (name "/Y8") (class "Default")
      (node (ref "R8") (pin "1") (pinfunction "1_1") (pintype "passive"))
      (node (ref "U$196") (pin "2") (pinfunction "E_2") (pintype "bidirectional"))
      (node (ref "U$197") (pin "2") (pinfunction "E_2") (pintype "bidirectional"))
      (node (ref "U$200") (pin "2") (pinfunction "E_2") (pintype "bidirectional"))
      (node (ref "U$201") (pin "2") (pinfunction "E_2") (pintype "bidirectional"))
      (node (ref "U$204") (pin "2") (pinfunction "E_2") (pintype "bidirectional"))
      (node (ref "U$205") (pin "2") (pinfunction "E_2") (pintype "bidirectional"))
      (node (ref "U$208") (pin "2") (pinfunction "E_2") (pintype "bidirectional"))
      (node (ref "U$209") (pin "2") (pinfunction "E_2") (pintype "bidirectional"))
      (node (ref "U$5") (pin "2") (pinfunction "CHAN7_2") (pintype "bidirectional"))
      (node (ref "U$68") (pin "2") (pinfunction "E_2") (pintype "bidirectional"))
      (node (ref "U$69") (pin "2") (pinfunction "E_2") (pintype "bidirectional"))
      (node (ref "U$72") (pin "2") (pinfunction "E_2") (pintype "bidirectional"))
      (node (ref "U$73") (pin "2") (pinfunction "E_2") (pintype "bidirectional"))
      (node (ref "U$76") (pin "2") (pinfunction "E_2") (pintype "bidirectional"))
      (node (ref "U$77") (pin "2") (pinfunction "E_2") (pintype "bidirectional"))
      (node (ref "U$80") (pin "2") (pinfunction "E_2") (pintype "bidirectional"))
      (node (ref "U$81") (pin "2") (pinfunction "E_2") (pintype "bidirectional"))
    )
    (net (code "52") (name "/Y9") (class "Default")
      (node (ref "R9") (pin "1") (pinfunction "1_1") (pintype "passive"))
      (node (ref "U$178") (pin "2") (pinfunction "E_2") (pintype "bidirectional"))
      (node (ref "U$179") (pin "2") (pinfunction "E_2") (pintype "bidirectional"))
      (node (ref "U$182") (pin "2") (pinfunction "E_2") (pintype "bidirectional"))
      (node (ref "U$183") (pin "2") (pinfunction "E_2") (pintype "bidirectional"))
      (node (ref "U$186") (pin "2") (pinfunction "E_2") (pintype "bidirectional"))
      (node (ref "U$187") (pin "2") (pinfunction "E_2") (pintype "bidirectional"))
      (node (ref "U$190") (pin "2") (pinfunction "E_2") (pintype "bidirectional"))
      (node (ref "U$191") (pin "2") (pinfunction "E_2") (pintype "bidirectional"))
      (node (ref "U$5") (pin "23") (pinfunction "CHAN8_23") (pintype "bidirectional"))
      (node (ref "U$50") (pin "2") (pinfunction "E_2") (pintype "bidirectional"))
      (node (ref "U$51") (pin "2") (pinfunction "E_2") (pintype "bidirectional"))
      (node (ref "U$54") (pin "2") (pinfunction "E_2") (pintype "bidirectional"))
      (node (ref "U$55") (pin "2") (pinfunction "E_2") (pintype "bidirectional"))
      (node (ref "U$58") (pin "2") (pinfunction "E_2") (pintype "bidirectional"))
      (node (ref "U$59") (pin "2") (pinfunction "E_2") (pintype "bidirectional"))
      (node (ref "U$62") (pin "2") (pinfunction "E_2") (pintype "bidirectional"))
      (node (ref "U$63") (pin "2") (pinfunction "E_2") (pintype "bidirectional"))
    )
    (net (code "53") (name "/Y10") (class "Default")
      (node (ref "R10") (pin "1") (pinfunction "1_1") (pintype "passive"))
      (node (ref "U$180") (pin "2") (pinfunction "E_2") (pintype "bidirectional"))
      (node (ref "U$181") (pin "2") (pinfunction "E_2") (pintype "bidirectional"))
      (node (ref "U$184") (pin "2") (pinfunction "E_2") (pintype "bidirectional"))
      (node (ref "U$185") (pin "2") (pinfunction "E_2") (pintype "bidirectional"))
      (node (ref "U$188") (pin "2") (pinfunction "E_2") (pintype "bidirectional"))
      (node (ref "U$189") (pin "2") (pinfunction "E_2") (pintype "bidirectional"))
      (node (ref "U$192") (pin "2") (pinfunction "E_2") (pintype "bidirectional"))
      (node (ref "U$193") (pin "2") (pinfunction "E_2") (pintype "bidirectional"))
      (node (ref "U$5") (pin "22") (pinfunction "CHAN9_22") (pintype "bidirectional"))
      (node (ref "U$52") (pin "2") (pinfunction "E_2") (pintype "bidirectional"))
      (node (ref "U$53") (pin "2") (pinfunction "E_2") (pintype "bidirectional"))
      (node (ref "U$56") (pin "2") (pinfunction "E_2") (pintype "bidirectional"))
      (node (ref "U$57") (pin "2") (pinfunction "E_2") (pintype "bidirectional"))
      (node (ref "U$60") (pin "2") (pinfunction "E_2") (pintype "bidirectional"))
      (node (ref "U$61") (pin "2") (pinfunction "E_2") (pintype "bidirectional"))
      (node (ref "U$64") (pin "2") (pinfunction "E_2") (pintype "bidirectional"))
      (node (ref "U$65") (pin "2") (pinfunction "E_2") (pintype "bidirectional"))
    )
    (net (code "54") (name "/Y11") (class "Default")
      (node (ref "R11") (pin "1") (pinfunction "1_1") (pintype "passive"))
      (node (ref "U$162") (pin "2") (pinfunction "E_2") (pintype "bidirectional"))
      (node (ref "U$163") (pin "2") (pinfunction "E_2") (pintype "bidirectional"))
      (node (ref "U$166") (pin "2") (pinfunction "E_2") (pintype "bidirectional"))
      (node (ref "U$167") (pin "2") (pinfunction "E_2") (pintype "bidirectional"))
      (node (ref "U$170") (pin "2") (pinfunction "E_2") (pintype "bidirectional"))
      (node (ref "U$171") (pin "2") (pinfunction "E_2") (pintype "bidirectional"))
      (node (ref "U$174") (pin "2") (pinfunction "E_2") (pintype "bidirectional"))
      (node (ref "U$175") (pin "2") (pinfunction "E_2") (pintype "bidirectional"))
      (node (ref "U$34") (pin "2") (pinfunction "E_2") (pintype "bidirectional"))
      (node (ref "U$35") (pin "2") (pinfunction "E_2") (pintype "bidirectional"))
      (node (ref "U$38") (pin "2") (pinfunction "E_2") (pintype "bidirectional"))
      (node (ref "U$39") (pin "2") (pinfunction "E_2") (pintype "bidirectional"))
      (node (ref "U$42") (pin "2") (pinfunction "E_2") (pintype "bidirectional"))
      (node (ref "U$43") (pin "2") (pinfunction "E_2") (pintype "bidirectional"))
      (node (ref "U$46") (pin "2") (pinfunction "E_2") (pintype "bidirectional"))
      (node (ref "U$47") (pin "2") (pinfunction "E_2") (pintype "bidirectional"))
      (node (ref "U$5") (pin "21") (pinfunction "CHAN10_21") (pintype "bidirectional"))
    )
    (net (code "55") (name "/Y12") (class "Default")
      (node (ref "R12") (pin "1") (pinfunction "1_1") (pintype "passive"))
      (node (ref "U$164") (pin "2") (pinfunction "E_2") (pintype "bidirectional"))
      (node (ref "U$165") (pin "2") (pinfunction "E_2") (pintype "bidirectional"))
      (node (ref "U$168") (pin "2") (pinfunction "E_2") (pintype "bidirectional"))
      (node (ref "U$169") (pin "2") (pinfunction "E_2") (pintype "bidirectional"))
      (node (ref "U$172") (pin "2") (pinfunction "E_2") (pintype "bidirectional"))
      (node (ref "U$173") (pin "2") (pinfunction "E_2") (pintype "bidirectional"))
      (node (ref "U$176") (pin "2") (pinfunction "E_2") (pintype "bidirectional"))
      (node (ref "U$177") (pin "2") (pinfunction "E_2") (pintype "bidirectional"))
      (node (ref "U$36") (pin "2") (pinfunction "E_2") (pintype "bidirectional"))
      (node (ref "U$37") (pin "2") (pinfunction "E_2") (pintype "bidirectional"))
      (node (ref "U$40") (pin "2") (pinfunction "E_2") (pintype "bidirectional"))
      (node (ref "U$41") (pin "2") (pinfunction "E_2") (pintype "bidirectional"))
      (node (ref "U$44") (pin "2") (pinfunction "E_2") (pintype "bidirectional"))
      (node (ref "U$45") (pin "2") (pinfunction "E_2") (pintype "bidirectional"))
      (node (ref "U$48") (pin "2") (pinfunction "E_2") (pintype "bidirectional"))
      (node (ref "U$49") (pin "2") (pinfunction "E_2") (pintype "bidirectional"))
      (node (ref "U$5") (pin "20") (pinfunction "CHAN11_20") (pintype "bidirectional"))
    )
    (net (code "56") (name "/Y13") (class "Default")
      (node (ref "R13") (pin "1") (pinfunction "1_1") (pintype "passive"))
      (node (ref "U$146") (pin "2") (pinfunction "E_2") (pintype "bidirectional"))
      (node (ref "U$147") (pin "2") (pinfunction "E_2") (pintype "bidirectional"))
      (node (ref "U$150") (pin "2") (pinfunction "E_2") (pintype "bidirectional"))
      (node (ref "U$151") (pin "2") (pinfunction "E_2") (pintype "bidirectional"))
      (node (ref "U$154") (pin "2") (pinfunction "E_2") (pintype "bidirectional"))
      (node (ref "U$155") (pin "2") (pinfunction "E_2") (pintype "bidirectional"))
      (node (ref "U$158") (pin "2") (pinfunction "E_2") (pintype "bidirectional"))
      (node (ref "U$159") (pin "2") (pinfunction "E_2") (pintype "bidirectional"))
      (node (ref "U$18") (pin "2") (pinfunction "E_2") (pintype "bidirectional"))
      (node (ref "U$19") (pin "2") (pinfunction "E_2") (pintype "bidirectional"))
      (node (ref "U$22") (pin "2") (pinfunction "E_2") (pintype "bidirectional"))
      (node (ref "U$23") (pin "2") (pinfunction "E_2") (pintype "bidirectional"))
      (node (ref "U$26") (pin "2") (pinfunction "E_2") (pintype "bidirectional"))
      (node (ref "U$27") (pin "2") (pinfunction "E_2") (pintype "bidirectional"))
      (node (ref "U$30") (pin "2") (pinfunction "E_2") (pintype "bidirectional"))
      (node (ref "U$31") (pin "2") (pinfunction "E_2") (pintype "bidirectional"))
      (node (ref "U$5") (pin "19") (pinfunction "CHAN12_19") (pintype "bidirectional"))
    )
    (net (code "57") (name "/Y14") (class "Default")
      (node (ref "R14") (pin "1") (pinfunction "1_1") (pintype "passive"))
      (node (ref "U$148") (pin "2") (pinfunction "E_2") (pintype "bidirectional"))
      (node (ref "U$149") (pin "2") (pinfunction "E_2") (pintype "bidirectional"))
      (node (ref "U$152") (pin "2") (pinfunction "E_2") (pintype "bidirectional"))
      (node (ref "U$153") (pin "2") (pinfunction "E_2") (pintype "bidirectional"))
      (node (ref "U$156") (pin "2") (pinfunction "E_2") (pintype "bidirectional"))
      (node (ref "U$157") (pin "2") (pinfunction "E_2") (pintype "bidirectional"))
      (node (ref "U$160") (pin "2") (pinfunction "E_2") (pintype "bidirectional"))
      (node (ref "U$161") (pin "2") (pinfunction "E_2") (pintype "bidirectional"))
      (node (ref "U$20") (pin "2") (pinfunction "E_2") (pintype "bidirectional"))
      (node (ref "U$21") (pin "2") (pinfunction "E_2") (pintype "bidirectional"))
      (node (ref "U$24") (pin "2") (pinfunction "E_2") (pintype "bidirectional"))
      (node (ref "U$25") (pin "2") (pinfunction "E_2") (pintype "bidirectional"))
      (node (ref "U$28") (pin "2") (pinfunction "E_2") (pintype "bidirectional"))
      (node (ref "U$29") (pin "2") (pinfunction "E_2") (pintype "bidirectional"))
      (node (ref "U$32") (pin "2") (pinfunction "E_2") (pintype "bidirectional"))
      (node (ref "U$33") (pin "2") (pinfunction "E_2") (pintype "bidirectional"))
      (node (ref "U$5") (pin "18") (pinfunction "CHAN13_18") (pintype "bidirectional"))
    )
    (net (code "58") (name "/Y15") (class "Default")
      (node (ref "R15") (pin "1") (pinfunction "1_1") (pintype "passive"))
      (node (ref "U$1") (pin "2") (pinfunction "E_2") (pintype "bidirectional"))
      (node (ref "U$10") (pin "2") (pinfunction "E_2") (pintype "bidirectional"))
      (node (ref "U$11") (pin "2") (pinfunction "E_2") (pintype "bidirectional"))
      (node (ref "U$130") (pin "2") (pinfunction "E_2") (pintype "bidirectional"))
      (node (ref "U$131") (pin "2") (pinfunction "E_2") (pintype "bidirectional"))
      (node (ref "U$134") (pin "2") (pinfunction "E_2") (pintype "bidirectional"))
      (node (ref "U$135") (pin "2") (pinfunction "E_2") (pintype "bidirectional"))
      (node (ref "U$138") (pin "2") (pinfunction "E_2") (pintype "bidirectional"))
      (node (ref "U$139") (pin "2") (pinfunction "E_2") (pintype "bidirectional"))
      (node (ref "U$14") (pin "2") (pinfunction "E_2") (pintype "bidirectional"))
      (node (ref "U$142") (pin "2") (pinfunction "E_2") (pintype "bidirectional"))
      (node (ref "U$143") (pin "2") (pinfunction "E_2") (pintype "bidirectional"))
      (node (ref "U$15") (pin "2") (pinfunction "E_2") (pintype "bidirectional"))
      (node (ref "U$2") (pin "2") (pinfunction "E_2") (pintype "bidirectional"))
      (node (ref "U$5") (pin "17") (pinfunction "CHAN14_17") (pintype "bidirectional"))
      (node (ref "U$6") (pin "2") (pinfunction "E_2") (pintype "bidirectional"))
      (node (ref "U$7") (pin "2") (pinfunction "E_2") (pintype "bidirectional"))
    )
    (net (code "59") (name "/Y16") (class "Default")
      (node (ref "R16") (pin "1") (pinfunction "1_1") (pintype "passive"))
      (node (ref "U$12") (pin "2") (pinfunction "E_2") (pintype "bidirectional"))
      (node (ref "U$13") (pin "2") (pinfunction "E_2") (pintype "bidirectional"))
      (node (ref "U$132") (pin "2") (pinfunction "E_2") (pintype "bidirectional"))
      (node (ref "U$133") (pin "2") (pinfunction "E_2") (pintype "bidirectional"))
      (node (ref "U$136") (pin "2") (pinfunction "E_2") (pintype "bidirectional"))
      (node (ref "U$137") (pin "2") (pinfunction "E_2") (pintype "bidirectional"))
      (node (ref "U$140") (pin "2") (pinfunction "E_2") (pintype "bidirectional"))
      (node (ref "U$141") (pin "2") (pinfunction "E_2") (pintype "bidirectional"))
      (node (ref "U$144") (pin "2") (pinfunction "E_2") (pintype "bidirectional"))
      (node (ref "U$145") (pin "2") (pinfunction "E_2") (pintype "bidirectional"))
      (node (ref "U$16") (pin "2") (pinfunction "E_2") (pintype "bidirectional"))
      (node (ref "U$17") (pin "2") (pinfunction "E_2") (pintype "bidirectional"))
      (node (ref "U$3") (pin "2") (pinfunction "E_2") (pintype "bidirectional"))
      (node (ref "U$4") (pin "2") (pinfunction "E_2") (pintype "bidirectional"))
      (node (ref "U$5") (pin "16") (pinfunction "CHAN15_16") (pintype "bidirectional"))
      (node (ref "U$8") (pin "2") (pinfunction "E_2") (pintype "bidirectional"))
      (node (ref "U$9") (pin "2") (pinfunction "E_2") (pintype "bidirectional"))
    )
    (net (code "60") (name "GND") (class "Default")
      (node (ref "C1") (pin "C") (pinfunction "-_C") (pintype "passive"))
      (node (ref "C2") (pin "C") (pinfunction "-_C") (pintype "passive"))
      (node (ref "C3") (pin "C") (pinfunction "-_C") (pintype "passive"))
      (node (ref "C4") (pin "C") (pinfunction "-_C") (pintype "passive"))
      (node (ref "IC1") (pin "4") (pinfunction "GND_4") (pintype "power_in"))
      (node (ref "IC2") (pin "12") (pinfunction "GND_12") (pintype "power_in"))
      (node (ref "R1") (pin "2") (pinfunction "2_2") (pintype "passive"))
      (node (ref "R10") (pin "2") (pinfunction "2_2") (pintype "passive"))
      (node (ref "R11") (pin "2") (pinfunction "2_2") (pintype "passive"))
      (node (ref "R12") (pin "2") (pinfunction "2_2") (pintype "passive"))
      (node (ref "R13") (pin "2") (pinfunction "2_2") (pintype "passive"))
      (node (ref "R14") (pin "2") (pinfunction "2_2") (pintype "passive"))
      (node (ref "R15") (pin "2") (pinfunction "2_2") (pintype "passive"))
      (node (ref "R16") (pin "2") (pinfunction "2_2") (pintype "passive"))
      (node (ref "R17") (pin "1") (pinfunction "1_1") (pintype "passive"))
      (node (ref "R2") (pin "2") (pinfunction "2_2") (pintype "passive"))
      (node (ref "R3") (pin "2") (pinfunction "2_2") (pintype "passive"))
      (node (ref "R4") (pin "2") (pinfunction "2_2") (pintype "passive"))
      (node (ref "R5") (pin "2") (pinfunction "2_2") (pintype "passive"))
      (node (ref "R6") (pin "2") (pinfunction "2_2") (pintype "passive"))
      (node (ref "R7") (pin "2") (pinfunction "2_2") (pintype "passive"))
      (node (ref "R8") (pin "2") (pinfunction "2_2") (pintype "passive"))
      (node (ref "R9") (pin "2") (pinfunction "2_2") (pintype "passive"))
      (node (ref "U$5") (pin "12") (pinfunction "GND_12") (pintype "bidirectional"))
    )
    (net (code "61") (name "Net-(C3-+)") (class "Default")
      (node (ref "C3") (pin "A") (pinfunction "+_A") (pintype "passive"))
      (node (ref "IC1") (pin "5") (pinfunction "+IN2_5") (pintype "input"))
      (node (ref "R17") (pin "2") (pinfunction "2_2") (pintype "passive"))
      (node (ref "R18") (pin "1") (pinfunction "1_1") (pintype "passive"))
    )
    (net (code "62") (name "Net-(D1-C)") (class "Default")
      (node (ref "D1") (pin "1") (pinfunction "C_1") (pintype "passive"))
      (node (ref "U$1") (pin "1") (pinfunction "C_1") (pintype "bidirectional"))
    )
    (net (code "63") (name "Net-(D2-C)") (class "Default")
      (node (ref "D2") (pin "1") (pinfunction "C_1") (pintype "passive"))
      (node (ref "U$2") (pin "1") (pinfunction "C_1") (pintype "bidirectional"))
    )
    (net (code "64") (name "Net-(D3-C)") (class "Default")
      (node (ref "D3") (pin "1") (pinfunction "C_1") (pintype "passive"))
      (node (ref "U$3") (pin "1") (pinfunction "C_1") (pintype "bidirectional"))
    )
    (net (code "65") (name "Net-(D4-C)") (class "Default")
      (node (ref "D4") (pin "1") (pinfunction "C_1") (pintype "passive"))
      (node (ref "U$4") (pin "1") (pinfunction "C_1") (pintype "bidirectional"))
    )
    (net (code "66") (name "Net-(D5-C)") (class "Default")
      (node (ref "D5") (pin "1") (pinfunction "C_1") (pintype "passive"))
      (node (ref "U$6") (pin "1") (pinfunction "C_1") (pintype "bidirectional"))
    )
    (net (code "67") (name "Net-(D6-C)") (class "Default")
      (node (ref "D6") (pin "1") (pinfunction "C_1") (pintype "passive"))
      (node (ref "U$7") (pin "1") (pinfunction "C_1") (pintype "bidirectional"))
    )
    (net (code "68") (name "Net-(D7-C)") (class "Default")
      (node (ref "D7") (pin "1") (pinfunction "C_1") (pintype "passive"))
      (node (ref "U$8") (pin "1") (pinfunction "C_1") (pintype "bidirectional"))
    )
    (net (code "69") (name "Net-(D8-C)") (class "Default")
      (node (ref "D8") (pin "1") (pinfunction "C_1") (pintype "passive"))
      (node (ref "U$9") (pin "1") (pinfunction "C_1") (pintype "bidirectional"))
    )
    (net (code "70") (name "Net-(D9-C)") (class "Default")
      (node (ref "D9") (pin "1") (pinfunction "C_1") (pintype "passive"))
      (node (ref "U$10") (pin "1") (pinfunction "C_1") (pintype "bidirectional"))
    )
    (net (code "71") (name "Net-(D10-C)") (class "Default")
      (node (ref "D10") (pin "1") (pinfunction "C_1") (pintype "passive"))
      (node (ref "U$11") (pin "1") (pinfunction "C_1") (pintype "bidirectional"))
    )
    (net (code "72") (name "Net-(D11-C)") (class "Default")
      (node (ref "D11") (pin "1") (pinfunction "C_1") (pintype "passive"))
      (node (ref "U$12") (pin "1") (pinfunction "C_1") (pintype "bidirectional"))
    )
    (net (code "73") (name "Net-(D12-C)") (class "Default")
      (node (ref "D12") (pin "1") (pinfunction "C_1") (pintype "passive"))
      (node (ref "U$13") (pin "1") (pinfunction "C_1") (pintype "bidirectional"))
    )
    (net (code "74") (name "Net-(D13-C)") (class "Default")
      (node (ref "D13") (pin "1") (pinfunction "C_1") (pintype "passive"))
      (node (ref "U$14") (pin "1") (pinfunction "C_1") (pintype "bidirectional"))
    )
    (net (code "75") (name "Net-(D14-C)") (class "Default")
      (node (ref "D14") (pin "1") (pinfunction "C_1") (pintype "passive"))
      (node (ref "U$15") (pin "1") (pinfunction "C_1") (pintype "bidirectional"))
    )
    (net (code "76") (name "Net-(D15-C)") (class "Default")
      (node (ref "D15") (pin "1") (pinfunction "C_1") (pintype "passive"))
      (node (ref "U$16") (pin "1") (pinfunction "C_1") (pintype "bidirectional"))
    )
    (net (code "77") (name "Net-(D16-C)") (class "Default")
      (node (ref "D16") (pin "1") (pinfunction "C_1") (pintype "passive"))
      (node (ref "U$17") (pin "1") (pinfunction "C_1") (pintype "bidirectional"))
    )
    (net (code "78") (name "Net-(D17-C)") (class "Default")
      (node (ref "D17") (pin "1") (pinfunction "C_1") (pintype "passive"))
      (node (ref "U$18") (pin "1") (pinfunction "C_1") (pintype "bidirectional"))
    )
    (net (code "79") (name "Net-(D18-C)") (class "Default")
      (node (ref "D18") (pin "1") (pinfunction "C_1") (pintype "passive"))
      (node (ref "U$19") (pin "1") (pinfunction "C_1") (pintype "bidirectional"))
    )
    (net (code "80") (name "Net-(D19-C)") (class "Default")
      (node (ref "D19") (pin "1") (pinfunction "C_1") (pintype "passive"))
      (node (ref "U$20") (pin "1") (pinfunction "C_1") (pintype "bidirectional"))
    )
    (net (code "81") (name "Net-(D20-C)") (class "Default")
      (node (ref "D20") (pin "1") (pinfunction "C_1") (pintype "passive"))
      (node (ref "U$21") (pin "1") (pinfunction "C_1") (pintype "bidirectional"))
    )
    (net (code "82") (name "Net-(D21-C)") (class "Default")
      (node (ref "D21") (pin "1") (pinfunction "C_1") (pintype "passive"))
      (node (ref "U$22") (pin "1") (pinfunction "C_1") (pintype "bidirectional"))
    )
    (net (code "83") (name "Net-(D22-C)") (class "Default")
      (node (ref "D22") (pin "1") (pinfunction "C_1") (pintype "passive"))
      (node (ref "U$23") (pin "1") (pinfunction "C_1") (pintype "bidirectional"))
    )
    (net (code "84") (name "Net-(D23-C)") (class "Default")
      (node (ref "D23") (pin "1") (pinfunction "C_1") (pintype "passive"))
      (node (ref "U$24") (pin "1") (pinfunction "C_1") (pintype "bidirectional"))
    )
    (net (code "85") (name "Net-(D24-C)") (class "Default")
      (node (ref "D24") (pin "1") (pinfunction "C_1") (pintype "passive"))
      (node (ref "U$25") (pin "1") (pinfunction "C_1") (pintype "bidirectional"))
    )
    (net (code "86") (name "Net-(D25-C)") (class "Default")
      (node (ref "D25") (pin "1") (pinfunction "C_1") (pintype "passive"))
      (node (ref "U$26") (pin "1") (pinfunction "C_1") (pintype "bidirectional"))
    )
    (net (code "87") (name "Net-(D26-C)") (class "Default")
      (node (ref "D26") (pin "1") (pinfunction "C_1") (pintype "passive"))
      (node (ref "U$27") (pin "1") (pinfunction "C_1") (pintype "bidirectional"))
    )
    (net (code "88") (name "Net-(D27-C)") (class "Default")
      (node (ref "D27") (pin "1") (pinfunction "C_1") (pintype "passive"))
      (node (ref "U$28") (pin "1") (pinfunction "C_1") (pintype "bidirectional"))
    )
    (net (code "89") (name "Net-(D28-C)") (class "Default")
      (node (ref "D28") (pin "1") (pinfunction "C_1") (pintype "passive"))
      (node (ref "U$29") (pin "1") (pinfunction "C_1") (pintype "bidirectional"))
    )
    (net (code "90") (name "Net-(D29-C)") (class "Default")
      (node (ref "D29") (pin "1") (pinfunction "C_1") (pintype "passive"))
      (node (ref "U$30") (pin "1") (pinfunction "C_1") (pintype "bidirectional"))
    )
    (net (code "91") (name "Net-(D30-C)") (class "Default")
      (node (ref "D30") (pin "1") (pinfunction "C_1") (pintype "passive"))
      (node (ref "U$31") (pin "1") (pinfunction "C_1") (pintype "bidirectional"))
    )
    (net (code "92") (name "Net-(D31-C)") (class "Default")
      (node (ref "D31") (pin "1") (pinfunction "C_1") (pintype "passive"))
      (node (ref "U$32") (pin "1") (pinfunction "C_1") (pintype "bidirectional"))
    )
    (net (code "93") (name "Net-(D32-C)") (class "Default")
      (node (ref "D32") (pin "1") (pinfunction "C_1") (pintype "passive"))
      (node (ref "U$33") (pin "1") (pinfunction "C_1") (pintype "bidirectional"))
    )
    (net (code "94") (name "Net-(D33-C)") (class "Default")
      (node (ref "D33") (pin "1") (pinfunction "C_1") (pintype "passive"))
      (node (ref "U$34") (pin "1") (pinfunction "C_1") (pintype "bidirectional"))
    )
    (net (code "95") (name "Net-(D34-C)") (class "Default")
      (node (ref "D34") (pin "1") (pinfunction "C_1") (pintype "passive"))
      (node (ref "U$35") (pin "1") (pinfunction "C_1") (pintype "bidirectional"))
    )
    (net (code "96") (name "Net-(D35-C)") (class "Default")
      (node (ref "D35") (pin "1") (pinfunction "C_1") (pintype "passive"))
      (node (ref "U$36") (pin "1") (pinfunction "C_1") (pintype "bidirectional"))
    )
    (net (code "97") (name "Net-(D36-C)") (class "Default")
      (node (ref "D36") (pin "1") (pinfunction "C_1") (pintype "passive"))
      (node (ref "U$37") (pin "1") (pinfunction "C_1") (pintype "bidirectional"))
    )
    (net (code "98") (name "Net-(D37-C)") (class "Default")
      (node (ref "D37") (pin "1") (pinfunction "C_1") (pintype "passive"))
      (node (ref "U$38") (pin "1") (pinfunction "C_1") (pintype "bidirectional"))
    )
    (net (code "99") (name "Net-(D38-C)") (class "Default")
      (node (ref "D38") (pin "1") (pinfunction "C_1") (pintype "passive"))
      (node (ref "U$39") (pin "1") (pinfunction "C_1") (pintype "bidirectional"))
    )
    (net (code "100") (name "Net-(D39-C)") (class "Default")
      (node (ref "D39") (pin "1") (pinfunction "C_1") (pintype "passive"))
      (node (ref "U$40") (pin "1") (pinfunction "C_1") (pintype "bidirectional"))
    )
    (net (code "101") (name "Net-(D40-C)") (class "Default")
      (node (ref "D40") (pin "1") (pinfunction "C_1") (pintype "passive"))
      (node (ref "U$41") (pin "1") (pinfunction "C_1") (pintype "bidirectional"))
    )
    (net (code "102") (name "Net-(D41-C)") (class "Default")
      (node (ref "D41") (pin "1") (pinfunction "C_1") (pintype "passive"))
      (node (ref "U$42") (pin "1") (pinfunction "C_1") (pintype "bidirectional"))
    )
    (net (code "103") (name "Net-(D42-C)") (class "Default")
      (node (ref "D42") (pin "1") (pinfunction "C_1") (pintype "passive"))
      (node (ref "U$43") (pin "1") (pinfunction "C_1") (pintype "bidirectional"))
    )
    (net (code "104") (name "Net-(D43-C)") (class "Default")
      (node (ref "D43") (pin "1") (pinfunction "C_1") (pintype "passive"))
      (node (ref "U$44") (pin "1") (pinfunction "C_1") (pintype "bidirectional"))
    )
    (net (code "105") (name "Net-(D44-C)") (class "Default")
      (node (ref "D44") (pin "1") (pinfunction "C_1") (pintype "passive"))
      (node (ref "U$45") (pin "1") (pinfunction "C_1") (pintype "bidirectional"))
    )
    (net (code "106") (name "Net-(D45-C)") (class "Default")
      (node (ref "D45") (pin "1") (pinfunction "C_1") (pintype "passive"))
      (node (ref "U$46") (pin "1") (pinfunction "C_1") (pintype "bidirectional"))
    )
    (net (code "107") (name "Net-(D46-C)") (class "Default")
      (node (ref "D46") (pin "1") (pinfunction "C_1") (pintype "passive"))
      (node (ref "U$47") (pin "1") (pinfunction "C_1") (pintype "bidirectional"))
    )
    (net (code "108") (name "Net-(D47-C)") (class "Default")
      (node (ref "D47") (pin "1") (pinfunction "C_1") (pintype "passive"))
      (node (ref "U$48") (pin "1") (pinfunction "C_1") (pintype "bidirectional"))
    )
    (net (code "109") (name "Net-(D48-C)") (class "Default")
      (node (ref "D48") (pin "1") (pinfunction "C_1") (pintype "passive"))
      (node (ref "U$49") (pin "1") (pinfunction "C_1") (pintype "bidirectional"))
    )
    (net (code "110") (name "Net-(D49-C)") (class "Default")
      (node (ref "D49") (pin "1") (pinfunction "C_1") (pintype "passive"))
      (node (ref "U$50") (pin "1") (pinfunction "C_1") (pintype "bidirectional"))
    )
    (net (code "111") (name "Net-(D50-C)") (class "Default")
      (node (ref "D50") (pin "1") (pinfunction "C_1") (pintype "passive"))
      (node (ref "U$51") (pin "1") (pinfunction "C_1") (pintype "bidirectional"))
    )
    (net (code "112") (name "Net-(D51-C)") (class "Default")
      (node (ref "D51") (pin "1") (pinfunction "C_1") (pintype "passive"))
      (node (ref "U$52") (pin "1") (pinfunction "C_1") (pintype "bidirectional"))
    )
    (net (code "113") (name "Net-(D52-C)") (class "Default")
      (node (ref "D52") (pin "1") (pinfunction "C_1") (pintype "passive"))
      (node (ref "U$53") (pin "1") (pinfunction "C_1") (pintype "bidirectional"))
    )
    (net (code "114") (name "Net-(D53-C)") (class "Default")
      (node (ref "D53") (pin "1") (pinfunction "C_1") (pintype "passive"))
      (node (ref "U$54") (pin "1") (pinfunction "C_1") (pintype "bidirectional"))
    )
    (net (code "115") (name "Net-(D54-C)") (class "Default")
      (node (ref "D54") (pin "1") (pinfunction "C_1") (pintype "passive"))
      (node (ref "U$55") (pin "1") (pinfunction "C_1") (pintype "bidirectional"))
    )
    (net (code "116") (name "Net-(D55-C)") (class "Default")
      (node (ref "D55") (pin "1") (pinfunction "C_1") (pintype "passive"))
      (node (ref "U$56") (pin "1") (pinfunction "C_1") (pintype "bidirectional"))
    )
    (net (code "117") (name "Net-(D56-C)") (class "Default")
      (node (ref "D56") (pin "1") (pinfunction "C_1") (pintype "passive"))
      (node (ref "U$57") (pin "1") (pinfunction "C_1") (pintype "bidirectional"))
    )
    (net (code "118") (name "Net-(D57-C)") (class "Default")
      (node (ref "D57") (pin "1") (pinfunction "C_1") (pintype "passive"))
      (node (ref "U$58") (pin "1") (pinfunction "C_1") (pintype "bidirectional"))
    )
    (net (code "119") (name "Net-(D58-C)") (class "Default")
      (node (ref "D58") (pin "1") (pinfunction "C_1") (pintype "passive"))
      (node (ref "U$59") (pin "1") (pinfunction "C_1") (pintype "bidirectional"))
    )
    (net (code "120") (name "Net-(D59-C)") (class "Default")
      (node (ref "D59") (pin "1") (pinfunction "C_1") (pintype "passive"))
      (node (ref "U$60") (pin "1") (pinfunction "C_1") (pintype "bidirectional"))
    )
    (net (code "121") (name "Net-(D60-C)") (class "Default")
      (node (ref "D60") (pin "1") (pinfunction "C_1") (pintype "passive"))
      (node (ref "U$61") (pin "1") (pinfunction "C_1") (pintype "bidirectional"))
    )
    (net (code "122") (name "Net-(D61-C)") (class "Default")
      (node (ref "D61") (pin "1") (pinfunction "C_1") (pintype "passive"))
      (node (ref "U$62") (pin "1") (pinfunction "C_1") (pintype "bidirectional"))
    )
    (net (code "123") (name "Net-(D62-C)") (class "Default")
      (node (ref "D62") (pin "1") (pinfunction "C_1") (pintype "passive"))
      (node (ref "U$63") (pin "1") (pinfunction "C_1") (pintype "bidirectional"))
    )
    (net (code "124") (name "Net-(D63-C)") (class "Default")
      (node (ref "D63") (pin "1") (pinfunction "C_1") (pintype "passive"))
      (node (ref "U$64") (pin "1") (pinfunction "C_1") (pintype "bidirectional"))
    )
    (net (code "125") (name "Net-(D64-C)") (class "Default")
      (node (ref "D64") (pin "1") (pinfunction "C_1") (pintype "passive"))
      (node (ref "U$65") (pin "1") (pinfunction "C_1") (pintype "bidirectional"))
    )
    (net (code "126") (name "Net-(D65-C)") (class "Default")
      (node (ref "D65") (pin "1") (pinfunction "C_1") (pintype "passive"))
      (node (ref "U$66") (pin "1") (pinfunction "C_1") (pintype "bidirectional"))
    )
    (net (code "127") (name "Net-(D66-C)") (class "Default")
      (node (ref "D66") (pin "1") (pinfunction "C_1") (pintype "passive"))
      (node (ref "U$67") (pin "1") (pinfunction "C_1") (pintype "bidirectional"))
    )
    (net (code "128") (name "Net-(D67-C)") (class "Default")
      (node (ref "D67") (pin "1") (pinfunction "C_1") (pintype "passive"))
      (node (ref "U$68") (pin "1") (pinfunction "C_1") (pintype "bidirectional"))
    )
    (net (code "129") (name "Net-(D68-C)") (class "Default")
      (node (ref "D68") (pin "1") (pinfunction "C_1") (pintype "passive"))
      (node (ref "U$69") (pin "1") (pinfunction "C_1") (pintype "bidirectional"))
    )
    (net (code "130") (name "Net-(D69-C)") (class "Default")
      (node (ref "D69") (pin "1") (pinfunction "C_1") (pintype "passive"))
      (node (ref "U$70") (pin "1") (pinfunction "C_1") (pintype "bidirectional"))
    )
    (net (code "131") (name "Net-(D70-C)") (class "Default")
      (node (ref "D70") (pin "1") (pinfunction "C_1") (pintype "passive"))
      (node (ref "U$71") (pin "1") (pinfunction "C_1") (pintype "bidirectional"))
    )
    (net (code "132") (name "Net-(D71-C)") (class "Default")
      (node (ref "D71") (pin "1") (pinfunction "C_1") (pintype "passive"))
      (node (ref "U$72") (pin "1") (pinfunction "C_1") (pintype "bidirectional"))
    )
    (net (code "133") (name "Net-(D72-C)") (class "Default")
      (node (ref "D72") (pin "1") (pinfunction "C_1") (pintype "passive"))
      (node (ref "U$73") (pin "1") (pinfunction "C_1") (pintype "bidirectional"))
    )
    (net (code "134") (name "Net-(D73-C)") (class "Default")
      (node (ref "D73") (pin "1") (pinfunction "C_1") (pintype "passive"))
      (node (ref "U$74") (pin "1") (pinfunction "C_1") (pintype "bidirectional"))
    )
    (net (code "135") (name "Net-(D74-C)") (class "Default")
      (node (ref "D74") (pin "1") (pinfunction "C_1") (pintype "passive"))
      (node (ref "U$75") (pin "1") (pinfunction "C_1") (pintype "bidirectional"))
    )
    (net (code "136") (name "Net-(D75-C)") (class "Default")
      (node (ref "D75") (pin "1") (pinfunction "C_1") (pintype "passive"))
      (node (ref "U$76") (pin "1") (pinfunction "C_1") (pintype "bidirectional"))
    )
    (net (code "137") (name "Net-(D76-C)") (class "Default")
      (node (ref "D76") (pin "1") (pinfunction "C_1") (pintype "passive"))
      (node (ref "U$77") (pin "1") (pinfunction "C_1") (pintype "bidirectional"))
    )
    (net (code "138") (name "Net-(D77-C)") (class "Default")
      (node (ref "D77") (pin "1") (pinfunction "C_1") (pintype "passive"))
      (node (ref "U$78") (pin "1") (pinfunction "C_1") (pintype "bidirectional"))
    )
    (net (code "139") (name "Net-(D78-C)") (class "Default")
      (node (ref "D78") (pin "1") (pinfunction "C_1") (pintype "passive"))
      (node (ref "U$79") (pin "1") (pinfunction "C_1") (pintype "bidirectional"))
    )
    (net (code "140") (name "Net-(D79-C)") (class "Default")
      (node (ref "D79") (pin "1") (pinfunction "C_1") (pintype "passive"))
      (node (ref "U$80") (pin "1") (pinfunction "C_1") (pintype "bidirectional"))
    )
    (net (code "141") (name "Net-(D80-C)") (class "Default")
      (node (ref "D80") (pin "1") (pinfunction "C_1") (pintype "passive"))
      (node (ref "U$81") (pin "1") (pinfunction "C_1") (pintype "bidirectional"))
    )
    (net (code "142") (name "Net-(D81-C)") (class "Default")
      (node (ref "D81") (pin "1") (pinfunction "C_1") (pintype "passive"))
      (node (ref "U$82") (pin "1") (pinfunction "C_1") (pintype "bidirectional"))
    )
    (net (code "143") (name "Net-(D82-C)") (class "Default")
      (node (ref "D82") (pin "1") (pinfunction "C_1") (pintype "passive"))
      (node (ref "U$83") (pin "1") (pinfunction "C_1") (pintype "bidirectional"))
    )
    (net (code "144") (name "Net-(D83-C)") (class "Default")
      (node (ref "D83") (pin "1") (pinfunction "C_1") (pintype "passive"))
      (node (ref "U$84") (pin "1") (pinfunction "C_1") (pintype "bidirectional"))
    )
    (net (code "145") (name "Net-(D84-C)") (class "Default")
      (node (ref "D84") (pin "1") (pinfunction "C_1") (pintype "passive"))
      (node (ref "U$85") (pin "1") (pinfunction "C_1") (pintype "bidirectional"))
    )
    (net (code "146") (name "Net-(D85-C)") (class "Default")
      (node (ref "D85") (pin "1") (pinfunction "C_1") (pintype "passive"))
      (node (ref "U$86") (pin "1") (pinfunction "C_1") (pintype "bidirectional"))
    )
    (net (code "147") (name "Net-(D86-C)") (class "Default")
      (node (ref "D86") (pin "1") (pinfunction "C_1") (pintype "passive"))
      (node (ref "U$87") (pin "1") (pinfunction "C_1") (pintype "bidirectional"))
    )
    (net (code "148") (name "Net-(D87-C)") (class "Default")
      (node (ref "D87") (pin "1") (pinfunction "C_1") (pintype "passive"))
      (node (ref "U$88") (pin "1") (pinfunction "C_1") (pintype "bidirectional"))
    )
    (net (code "149") (name "Net-(D88-C)") (class "Default")
      (node (ref "D88") (pin "1") (pinfunction "C_1") (pintype "passive"))
      (node (ref "U$89") (pin "1") (pinfunction "C_1") (pintype "bidirectional"))
    )
    (net (code "150") (name "Net-(D89-C)") (class "Default")
      (node (ref "D89") (pin "1") (pinfunction "C_1") (pintype "passive"))
      (node (ref "U$90") (pin "1") (pinfunction "C_1") (pintype "bidirectional"))
    )
    (net (code "151") (name "Net-(D90-C)") (class "Default")
      (node (ref "D90") (pin "1") (pinfunction "C_1") (pintype "passive"))
      (node (ref "U$91") (pin "1") (pinfunction "C_1") (pintype "bidirectional"))
    )
    (net (code "152") (name "Net-(D91-C)") (class "Default")
      (node (ref "D91") (pin "1") (pinfunction "C_1") (pintype "passive"))
      (node (ref "U$92") (pin "1") (pinfunction "C_1") (pintype "bidirectional"))
    )
    (net (code "153") (name "Net-(D92-C)") (class "Default")
      (node (ref "D92") (pin "1") (pinfunction "C_1") (pintype "passive"))
      (node (ref "U$93") (pin "1") (pinfunction "C_1") (pintype "bidirectional"))
    )
    (net (code "154") (name "Net-(D93-C)") (class "Default")
      (node (ref "D93") (pin "1") (pinfunction "C_1") (pintype "passive"))
      (node (ref "U$94") (pin "1") (pinfunction "C_1") (pintype "bidirectional"))
    )
    (net (code "155") (name "Net-(D94-C)") (class "Default")
      (node (ref "D94") (pin "1") (pinfunction "C_1") (pintype "passive"))
      (node (ref "U$95") (pin "1") (pinfunction "C_1") (pintype "bidirectional"))
    )
    (net (code "156") (name "Net-(D95-C)") (class "Default")
      (node (ref "D95") (pin "1") (pinfunction "C_1") (pintype "passive"))
      (node (ref "U$96") (pin "1") (pinfunction "C_1") (pintype "bidirectional"))
    )
    (net (code "157") (name "Net-(D96-C)") (class "Default")
      (node (ref "D96") (pin "1") (pinfunction "C_1") (pintype "passive"))
      (node (ref "U$97") (pin "1") (pinfunction "C_1") (pintype "bidirectional"))
    )
    (net (code "158") (name "Net-(D97-C)") (class "Default")
      (node (ref "D97") (pin "1") (pinfunction "C_1") (pintype "passive"))
      (node (ref "U$98") (pin "1") (pinfunction "C_1") (pintype "bidirectional"))
    )
    (net (code "159") (name "Net-(D98-C)") (class "Default")
      (node (ref "D98") (pin "1") (pinfunction "C_1") (pintype "passive"))
      (node (ref "U$99") (pin "1") (pinfunction "C_1") (pintype "bidirectional"))
    )
    (net (code "160") (name "Net-(D99-C)") (class "Default")
      (node (ref "D99") (pin "1") (pinfunction "C_1") (pintype "passive"))
      (node (ref "U$100") (pin "1") (pinfunction "C_1") (pintype "bidirectional"))
    )
    (net (code "161") (name "Net-(D100-C)") (class "Default")
      (node (ref "D100") (pin "1") (pinfunction "C_1") (pintype "passive"))
      (node (ref "U$101") (pin "1") (pinfunction "C_1") (pintype "bidirectional"))
    )
    (net (code "162") (name "Net-(D101-C)") (class "Default")
      (node (ref "D101") (pin "1") (pinfunction "C_1") (pintype "passive"))
      (node (ref "U$102") (pin "1") (pinfunction "C_1") (pintype "bidirectional"))
    )
    (net (code "163") (name "Net-(D102-C)") (class "Default")
      (node (ref "D102") (pin "1") (pinfunction "C_1") (pintype "passive"))
      (node (ref "U$103") (pin "1") (pinfunction "C_1") (pintype "bidirectional"))
    )
    (net (code "164") (name "Net-(D103-C)") (class "Default")
      (node (ref "D103") (pin "1") (pinfunction "C_1") (pintype "passive"))
      (node (ref "U$104") (pin "1") (pinfunction "C_1") (pintype "bidirectional"))
    )
    (net (code "165") (name "Net-(D104-C)") (class "Default")
      (node (ref "D104") (pin "1") (pinfunction "C_1") (pintype "passive"))
      (node (ref "U$105") (pin "1") (pinfunction "C_1") (pintype "bidirectional"))
    )
    (net (code "166") (name "Net-(D105-C)") (class "Default")
      (node (ref "D105") (pin "1") (pinfunction "C_1") (pintype "passive"))
      (node (ref "U$106") (pin "1") (pinfunction "C_1") (pintype "bidirectional"))
    )
    (net (code "167") (name "Net-(D106-C)") (class "Default")
      (node (ref "D106") (pin "1") (pinfunction "C_1") (pintype "passive"))
      (node (ref "U$107") (pin "1") (pinfunction "C_1") (pintype "bidirectional"))
    )
    (net (code "168") (name "Net-(D107-C)") (class "Default")
      (node (ref "D107") (pin "1") (pinfunction "C_1") (pintype "passive"))
      (node (ref "U$108") (pin "1") (pinfunction "C_1") (pintype "bidirectional"))
    )
    (net (code "169") (name "Net-(D108-C)") (class "Default")
      (node (ref "D108") (pin "1") (pinfunction "C_1") (pintype "passive"))
      (node (ref "U$109") (pin "1") (pinfunction "C_1") (pintype "bidirectional"))
    )
    (net (code "170") (name "Net-(D109-C)") (class "Default")
      (node (ref "D109") (pin "1") (pinfunction "C_1") (pintype "passive"))
      (node (ref "U$110") (pin "1") (pinfunction "C_1") (pintype "bidirectional"))
    )
    (net (code "171") (name "Net-(D110-C)") (class "Default")
      (node (ref "D110") (pin "1") (pinfunction "C_1") (pintype "passive"))
      (node (ref "U$111") (pin "1") (pinfunction "C_1") (pintype "bidirectional"))
    )
    (net (code "172") (name "Net-(D111-C)") (class "Default")
      (node (ref "D111") (pin "1") (pinfunction "C_1") (pintype "passive"))
      (node (ref "U$112") (pin "1") (pinfunction "C_1") (pintype "bidirectional"))
    )
    (net (code "173") (name "Net-(D112-C)") (class "Default")
      (node (ref "D112") (pin "1") (pinfunction "C_1") (pintype "passive"))
      (node (ref "U$113") (pin "1") (pinfunction "C_1") (pintype "bidirectional"))
    )
    (net (code "174") (name "Net-(D113-C)") (class "Default")
      (node (ref "D113") (pin "1") (pinfunction "C_1") (pintype "passive"))
      (node (ref "U$114") (pin "1") (pinfunction "C_1") (pintype "bidirectional"))
    )
    (net (code "175") (name "Net-(D114-C)") (class "Default")
      (node (ref "D114") (pin "1") (pinfunction "C_1") (pintype "passive"))
      (node (ref "U$115") (pin "1") (pinfunction "C_1") (pintype "bidirectional"))
    )
    (net (code "176") (name "Net-(D115-C)") (class "Default")
      (node (ref "D115") (pin "1") (pinfunction "C_1") (pintype "passive"))
      (node (ref "U$116") (pin "1") (pinfunction "C_1") (pintype "bidirectional"))
    )
    (net (code "177") (name "Net-(D116-C)") (class "Default")
      (node (ref "D116") (pin "1") (pinfunction "C_1") (pintype "passive"))
      (node (ref "U$117") (pin "1") (pinfunction "C_1") (pintype "bidirectional"))
    )
    (net (code "178") (name "Net-(D117-C)") (class "Default")
      (node (ref "D117") (pin "1") (pinfunction "C_1") (pintype "passive"))
      (node (ref "U$118") (pin "1") (pinfunction "C_1") (pintype "bidirectional"))
    )
    (net (code "179") (name "Net-(D118-C)") (class "Default")
      (node (ref "D118") (pin "1") (pinfunction "C_1") (pintype "passive"))
      (node (ref "U$119") (pin "1") (pinfunction "C_1") (pintype "bidirectional"))
    )
    (net (code "180") (name "Net-(D119-C)") (class "Default")
      (node (ref "D119") (pin "1") (pinfunction "C_1") (pintype "passive"))
      (node (ref "U$120") (pin "1") (pinfunction "C_1") (pintype "bidirectional"))
    )
    (net (code "181") (name "Net-(D120-C)") (class "Default")
      (node (ref "D120") (pin "1") (pinfunction "C_1") (pintype "passive"))
      (node (ref "U$121") (pin "1") (pinfunction "C_1") (pintype "bidirectional"))
    )
    (net (code "182") (name "Net-(D121-C)") (class "Default")
      (node (ref "D121") (pin "1") (pinfunction "C_1") (pintype "passive"))
      (node (ref "U$122") (pin "1") (pinfunction "C_1") (pintype "bidirectional"))
    )
    (net (code "183") (name "Net-(D122-C)") (class "Default")
      (node (ref "D122") (pin "1") (pinfunction "C_1") (pintype "passive"))
      (node (ref "U$123") (pin "1") (pinfunction "C_1") (pintype "bidirectional"))
    )
    (net (code "184") (name "Net-(D123-C)") (class "Default")
      (node (ref "D123") (pin "1") (pinfunction "C_1") (pintype "passive"))
      (node (ref "U$124") (pin "1") (pinfunction "C_1") (pintype "bidirectional"))
    )
    (net (code "185") (name "Net-(D124-C)") (class "Default")
      (node (ref "D124") (pin "1") (pinfunction "C_1") (pintype "passive"))
      (node (ref "U$125") (pin "1") (pinfunction "C_1") (pintype "bidirectional"))
    )
    (net (code "186") (name "Net-(D125-C)") (class "Default")
      (node (ref "D125") (pin "1") (pinfunction "C_1") (pintype "passive"))
      (node (ref "U$126") (pin "1") (pinfunction "C_1") (pintype "bidirectional"))
    )
    (net (code "187") (name "Net-(D126-C)") (class "Default")
      (node (ref "D126") (pin "1") (pinfunction "C_1") (pintype "passive"))
      (node (ref "U$127") (pin "1") (pinfunction "C_1") (pintype "bidirectional"))
    )
    (net (code "188") (name "Net-(D127-C)") (class "Default")
      (node (ref "D127") (pin "1") (pinfunction "C_1") (pintype "passive"))
      (node (ref "U$128") (pin "1") (pinfunction "C_1") (pintype "bidirectional"))
    )
    (net (code "189") (name "Net-(D128-C)") (class "Default")
      (node (ref "D128") (pin "1") (pinfunction "C_1") (pintype "passive"))
      (node (ref "U$129") (pin "1") (pinfunction "C_1") (pintype "bidirectional"))
    )
    (net (code "190") (name "Net-(D129-C)") (class "Default")
      (node (ref "D129") (pin "1") (pinfunction "C_1") (pintype "passive"))
      (node (ref "U$130") (pin "1") (pinfunction "C_1") (pintype "bidirectional"))
    )
    (net (code "191") (name "Net-(D130-C)") (class "Default")
      (node (ref "D130") (pin "1") (pinfunction "C_1") (pintype "passive"))
      (node (ref "U$131") (pin "1") (pinfunction "C_1") (pintype "bidirectional"))
    )
    (net (code "192") (name "Net-(D131-C)") (class "Default")
      (node (ref "D131") (pin "1") (pinfunction "C_1") (pintype "passive"))
      (node (ref "U$132") (pin "1") (pinfunction "C_1") (pintype "bidirectional"))
    )
    (net (code "193") (name "Net-(D132-C)") (class "Default")
      (node (ref "D132") (pin "1") (pinfunction "C_1") (pintype "passive"))
      (node (ref "U$133") (pin "1") (pinfunction "C_1") (pintype "bidirectional"))
    )
    (net (code "194") (name "Net-(D133-C)") (class "Default")
      (node (ref "D133") (pin "1") (pinfunction "C_1") (pintype "passive"))
      (node (ref "U$134") (pin "1") (pinfunction "C_1") (pintype "bidirectional"))
    )
    (net (code "195") (name "Net-(D134-C)") (class "Default")
      (node (ref "D134") (pin "1") (pinfunction "C_1") (pintype "passive"))
      (node (ref "U$135") (pin "1") (pinfunction "C_1") (pintype "bidirectional"))
    )
    (net (code "196") (name "Net-(D135-C)") (class "Default")
      (node (ref "D135") (pin "1") (pinfunction "C_1") (pintype "passive"))
      (node (ref "U$136") (pin "1") (pinfunction "C_1") (pintype "bidirectional"))
    )
    (net (code "197") (name "Net-(D136-C)") (class "Default")
      (node (ref "D136") (pin "1") (pinfunction "C_1") (pintype "passive"))
      (node (ref "U$137") (pin "1") (pinfunction "C_1") (pintype "bidirectional"))
    )
    (net (code "198") (name "Net-(D137-C)") (class "Default")
      (node (ref "D137") (pin "1") (pinfunction "C_1") (pintype "passive"))
      (node (ref "U$138") (pin "1") (pinfunction "C_1") (pintype "bidirectional"))
    )
    (net (code "199") (name "Net-(D138-C)") (class "Default")
      (node (ref "D138") (pin "1") (pinfunction "C_1") (pintype "passive"))
      (node (ref "U$139") (pin "1") (pinfunction "C_1") (pintype "bidirectional"))
    )
    (net (code "200") (name "Net-(D139-C)") (class "Default")
      (node (ref "D139") (pin "1") (pinfunction "C_1") (pintype "passive"))
      (node (ref "U$140") (pin "1") (pinfunction "C_1") (pintype "bidirectional"))
    )
    (net (code "201") (name "Net-(D140-C)") (class "Default")
      (node (ref "D140") (pin "1") (pinfunction "C_1") (pintype "passive"))
      (node (ref "U$141") (pin "1") (pinfunction "C_1") (pintype "bidirectional"))
    )
    (net (code "202") (name "Net-(D141-C)") (class "Default")
      (node (ref "D141") (pin "1") (pinfunction "C_1") (pintype "passive"))
      (node (ref "U$142") (pin "1") (pinfunction "C_1") (pintype "bidirectional"))
    )
    (net (code "203") (name "Net-(D142-C)") (class "Default")
      (node (ref "D142") (pin "1") (pinfunction "C_1") (pintype "passive"))
      (node (ref "U$143") (pin "1") (pinfunction "C_1") (pintype "bidirectional"))
    )
    (net (code "204") (name "Net-(D143-C)") (class "Default")
      (node (ref "D143") (pin "1") (pinfunction "C_1") (pintype "passive"))
      (node (ref "U$144") (pin "1") (pinfunction "C_1") (pintype "bidirectional"))
    )
    (net (code "205") (name "Net-(D144-C)") (class "Default")
      (node (ref "D144") (pin "1") (pinfunction "C_1") (pintype "passive"))
      (node (ref "U$145") (pin "1") (pinfunction "C_1") (pintype "bidirectional"))
    )
    (net (code "206") (name "Net-(D145-C)") (class "Default")
      (node (ref "D145") (pin "1") (pinfunction "C_1") (pintype "passive"))
      (node (ref "U$146") (pin "1") (pinfunction "C_1") (pintype "bidirectional"))
    )
    (net (code "207") (name "Net-(D146-C)") (class "Default")
      (node (ref "D146") (pin "1") (pinfunction "C_1") (pintype "passive"))
      (node (ref "U$147") (pin "1") (pinfunction "C_1") (pintype "bidirectional"))
    )
    (net (code "208") (name "Net-(D147-C)") (class "Default")
      (node (ref "D147") (pin "1") (pinfunction "C_1") (pintype "passive"))
      (node (ref "U$148") (pin "1") (pinfunction "C_1") (pintype "bidirectional"))
    )
    (net (code "209") (name "Net-(D148-C)") (class "Default")
      (node (ref "D148") (pin "1") (pinfunction "C_1") (pintype "passive"))
      (node (ref "U$149") (pin "1") (pinfunction "C_1") (pintype "bidirectional"))
    )
    (net (code "210") (name "Net-(D149-C)") (class "Default")
      (node (ref "D149") (pin "1") (pinfunction "C_1") (pintype "passive"))
      (node (ref "U$150") (pin "1") (pinfunction "C_1") (pintype "bidirectional"))
    )
    (net (code "211") (name "Net-(D150-C)") (class "Default")
      (node (ref "D150") (pin "1") (pinfunction "C_1") (pintype "passive"))
      (node (ref "U$151") (pin "1") (pinfunction "C_1") (pintype "bidirectional"))
    )
    (net (code "212") (name "Net-(D151-C)") (class "Default")
      (node (ref "D151") (pin "1") (pinfunction "C_1") (pintype "passive"))
      (node (ref "U$152") (pin "1") (pinfunction "C_1") (pintype "bidirectional"))
    )
    (net (code "213") (name "Net-(D152-C)") (class "Default")
      (node (ref "D152") (pin "1") (pinfunction "C_1") (pintype "passive"))
      (node (ref "U$153") (pin "1") (pinfunction "C_1") (pintype "bidirectional"))
    )
    (net (code "214") (name "Net-(D153-C)") (class "Default")
      (node (ref "D153") (pin "1") (pinfunction "C_1") (pintype "passive"))
      (node (ref "U$154") (pin "1") (pinfunction "C_1") (pintype "bidirectional"))
    )
    (net (code "215") (name "Net-(D154-C)") (class "Default")
      (node (ref "D154") (pin "1") (pinfunction "C_1") (pintype "passive"))
      (node (ref "U$155") (pin "1") (pinfunction "C_1") (pintype "bidirectional"))
    )
    (net (code "216") (name "Net-(D155-C)") (class "Default")
      (node (ref "D155") (pin "1") (pinfunction "C_1") (pintype "passive"))
      (node (ref "U$156") (pin "1") (pinfunction "C_1") (pintype "bidirectional"))
    )
    (net (code "217") (name "Net-(D156-C)") (class "Default")
      (node (ref "D156") (pin "1") (pinfunction "C_1") (pintype "passive"))
      (node (ref "U$157") (pin "1") (pinfunction "C_1") (pintype "bidirectional"))
    )
    (net (code "218") (name "Net-(D157-C)") (class "Default")
      (node (ref "D157") (pin "1") (pinfunction "C_1") (pintype "passive"))
      (node (ref "U$158") (pin "1") (pinfunction "C_1") (pintype "bidirectional"))
    )
    (net (code "219") (name "Net-(D158-C)") (class "Default")
      (node (ref "D158") (pin "1") (pinfunction "C_1") (pintype "passive"))
      (node (ref "U$159") (pin "1") (pinfunction "C_1") (pintype "bidirectional"))
    )
    (net (code "220") (name "Net-(D159-C)") (class "Default")
      (node (ref "D159") (pin "1") (pinfunction "C_1") (pintype "passive"))
      (node (ref "U$160") (pin "1") (pinfunction "C_1") (pintype "bidirectional"))
    )
    (net (code "221") (name "Net-(D160-C)") (class "Default")
      (node (ref "D160") (pin "1") (pinfunction "C_1") (pintype "passive"))
      (node (ref "U$161") (pin "1") (pinfunction "C_1") (pintype "bidirectional"))
    )
    (net (code "222") (name "Net-(D161-C)") (class "Default")
      (node (ref "D161") (pin "1") (pinfunction "C_1") (pintype "passive"))
      (node (ref "U$162") (pin "1") (pinfunction "C_1") (pintype "bidirectional"))
    )
    (net (code "223") (name "Net-(D162-C)") (class "Default")
      (node (ref "D162") (pin "1") (pinfunction "C_1") (pintype "passive"))
      (node (ref "U$163") (pin "1") (pinfunction "C_1") (pintype "bidirectional"))
    )
    (net (code "224") (name "Net-(D163-C)") (class "Default")
      (node (ref "D163") (pin "1") (pinfunction "C_1") (pintype "passive"))
      (node (ref "U$164") (pin "1") (pinfunction "C_1") (pintype "bidirectional"))
    )
    (net (code "225") (name "Net-(D164-C)") (class "Default")
      (node (ref "D164") (pin "1") (pinfunction "C_1") (pintype "passive"))
      (node (ref "U$165") (pin "1") (pinfunction "C_1") (pintype "bidirectional"))
    )
    (net (code "226") (name "Net-(D165-C)") (class "Default")
      (node (ref "D165") (pin "1") (pinfunction "C_1") (pintype "passive"))
      (node (ref "U$166") (pin "1") (pinfunction "C_1") (pintype "bidirectional"))
    )
    (net (code "227") (name "Net-(D166-C)") (class "Default")
      (node (ref "D166") (pin "1") (pinfunction "C_1") (pintype "passive"))
      (node (ref "U$167") (pin "1") (pinfunction "C_1") (pintype "bidirectional"))
    )
    (net (code "228") (name "Net-(D167-C)") (class "Default")
      (node (ref "D167") (pin "1") (pinfunction "C_1") (pintype "passive"))
      (node (ref "U$168") (pin "1") (pinfunction "C_1") (pintype "bidirectional"))
    )
    (net (code "229") (name "Net-(D168-C)") (class "Default")
      (node (ref "D168") (pin "1") (pinfunction "C_1") (pintype "passive"))
      (node (ref "U$169") (pin "1") (pinfunction "C_1") (pintype "bidirectional"))
    )
    (net (code "230") (name "Net-(D169-C)") (class "Default")
      (node (ref "D169") (pin "1") (pinfunction "C_1") (pintype "passive"))
      (node (ref "U$170") (pin "1") (pinfunction "C_1") (pintype "bidirectional"))
    )
    (net (code "231") (name "Net-(D170-C)") (class "Default")
      (node (ref "D170") (pin "1") (pinfunction "C_1") (pintype "passive"))
      (node (ref "U$171") (pin "1") (pinfunction "C_1") (pintype "bidirectional"))
    )
    (net (code "232") (name "Net-(D171-C)") (class "Default")
      (node (ref "D171") (pin "1") (pinfunction "C_1") (pintype "passive"))
      (node (ref "U$172") (pin "1") (pinfunction "C_1") (pintype "bidirectional"))
    )
    (net (code "233") (name "Net-(D172-C)") (class "Default")
      (node (ref "D172") (pin "1") (pinfunction "C_1") (pintype "passive"))
      (node (ref "U$173") (pin "1") (pinfunction "C_1") (pintype "bidirectional"))
    )
    (net (code "234") (name "Net-(D173-C)") (class "Default")
      (node (ref "D173") (pin "1") (pinfunction "C_1") (pintype "passive"))
      (node (ref "U$174") (pin "1") (pinfunction "C_1") (pintype "bidirectional"))
    )
    (net (code "235") (name "Net-(D174-C)") (class "Default")
      (node (ref "D174") (pin "1") (pinfunction "C_1") (pintype "passive"))
      (node (ref "U$175") (pin "1") (pinfunction "C_1") (pintype "bidirectional"))
    )
    (net (code "236") (name "Net-(D175-C)") (class "Default")
      (node (ref "D175") (pin "1") (pinfunction "C_1") (pintype "passive"))
      (node (ref "U$176") (pin "1") (pinfunction "C_1") (pintype "bidirectional"))
    )
    (net (code "237") (name "Net-(D176-C)") (class "Default")
      (node (ref "D176") (pin "1") (pinfunction "C_1") (pintype "passive"))
      (node (ref "U$177") (pin "1") (pinfunction "C_1") (pintype "bidirectional"))
    )
    (net (code "238") (name "Net-(D177-C)") (class "Default")
      (node (ref "D177") (pin "1") (pinfunction "C_1") (pintype "passive"))
      (node (ref "U$178") (pin "1") (pinfunction "C_1") (pintype "bidirectional"))
    )
    (net (code "239") (name "Net-(D178-C)") (class "Default")
      (node (ref "D178") (pin "1") (pinfunction "C_1") (pintype "passive"))
      (node (ref "U$179") (pin "1") (pinfunction "C_1") (pintype "bidirectional"))
    )
    (net (code "240") (name "Net-(D179-C)") (class "Default")
      (node (ref "D179") (pin "1") (pinfunction "C_1") (pintype "passive"))
      (node (ref "U$180") (pin "1") (pinfunction "C_1") (pintype "bidirectional"))
    )
    (net (code "241") (name "Net-(D180-C)") (class "Default")
      (node (ref "D180") (pin "1") (pinfunction "C_1") (pintype "passive"))
      (node (ref "U$181") (pin "1") (pinfunction "C_1") (pintype "bidirectional"))
    )
    (net (code "242") (name "Net-(D181-C)") (class "Default")
      (node (ref "D181") (pin "1") (pinfunction "C_1") (pintype "passive"))
      (node (ref "U$182") (pin "1") (pinfunction "C_1") (pintype "bidirectional"))
    )
    (net (code "243") (name "Net-(D182-C)") (class "Default")
      (node (ref "D182") (pin "1") (pinfunction "C_1") (pintype "passive"))
      (node (ref "U$183") (pin "1") (pinfunction "C_1") (pintype "bidirectional"))
    )
    (net (code "244") (name "Net-(D183-C)") (class "Default")
      (node (ref "D183") (pin "1") (pinfunction "C_1") (pintype "passive"))
      (node (ref "U$184") (pin "1") (pinfunction "C_1") (pintype "bidirectional"))
    )
    (net (code "245") (name "Net-(D184-C)") (class "Default")
      (node (ref "D184") (pin "1") (pinfunction "C_1") (pintype "passive"))
      (node (ref "U$185") (pin "1") (pinfunction "C_1") (pintype "bidirectional"))
    )
    (net (code "246") (name "Net-(D185-C)") (class "Default")
      (node (ref "D185") (pin "1") (pinfunction "C_1") (pintype "passive"))
      (node (ref "U$186") (pin "1") (pinfunction "C_1") (pintype "bidirectional"))
    )
    (net (code "247") (name "Net-(D186-C)") (class "Default")
      (node (ref "D186") (pin "1") (pinfunction "C_1") (pintype "passive"))
      (node (ref "U$187") (pin "1") (pinfunction "C_1") (pintype "bidirectional"))
    )
    (net (code "248") (name "Net-(D187-C)") (class "Default")
      (node (ref "D187") (pin "1") (pinfunction "C_1") (pintype "passive"))
      (node (ref "U$188") (pin "1") (pinfunction "C_1") (pintype "bidirectional"))
    )
    (net (code "249") (name "Net-(D188-C)") (class "Default")
      (node (ref "D188") (pin "1") (pinfunction "C_1") (pintype "passive"))
      (node (ref "U$189") (pin "1") (pinfunction "C_1") (pintype "bidirectional"))
    )
    (net (code "250") (name "Net-(D189-C)") (class "Default")
      (node (ref "D189") (pin "1") (pinfunction "C_1") (pintype "passive"))
      (node (ref "U$190") (pin "1") (pinfunction "C_1") (pintype "bidirectional"))
    )
    (net (code "251") (name "Net-(D190-C)") (class "Default")
      (node (ref "D190") (pin "1") (pinfunction "C_1") (pintype "passive"))
      (node (ref "U$191") (pin "1") (pinfunction "C_1") (pintype "bidirectional"))
    )
    (net (code "252") (name "Net-(D191-C)") (class "Default")
      (node (ref "D191") (pin "1") (pinfunction "C_1") (pintype "passive"))
      (node (ref "U$192") (pin "1") (pinfunction "C_1") (pintype "bidirectional"))
    )
    (net (code "253") (name "Net-(D192-C)") (class "Default")
      (node (ref "D192") (pin "1") (pinfunction "C_1") (pintype "passive"))
      (node (ref "U$193") (pin "1") (pinfunction "C_1") (pintype "bidirectional"))
    )
    (net (code "254") (name "Net-(D193-C)") (class "Default")
      (node (ref "D193") (pin "1") (pinfunction "C_1") (pintype "passive"))
      (node (ref "U$194") (pin "1") (pinfunction "C_1") (pintype "bidirectional"))
    )
    (net (code "255") (name "Net-(D194-C)") (class "Default")
      (node (ref "D194") (pin "1") (pinfunction "C_1") (pintype "passive"))
      (node (ref "U$195") (pin "1") (pinfunction "C_1") (pintype "bidirectional"))
    )
    (net (code "256") (name "Net-(D195-C)") (class "Default")
      (node (ref "D195") (pin "1") (pinfunction "C_1") (pintype "passive"))
      (node (ref "U$196") (pin "1") (pinfunction "C_1") (pintype "bidirectional"))
    )
    (net (code "257") (name "Net-(D196-C)") (class "Default")
      (node (ref "D196") (pin "1") (pinfunction "C_1") (pintype "passive"))
      (node (ref "U$197") (pin "1") (pinfunction "C_1") (pintype "bidirectional"))
    )
    (net (code "258") (name "Net-(D197-C)") (class "Default")
      (node (ref "D197") (pin "1") (pinfunction "C_1") (pintype "passive"))
      (node (ref "U$198") (pin "1") (pinfunction "C_1") (pintype "bidirectional"))
    )
    (net (code "259") (name "Net-(D198-C)") (class "Default")
      (node (ref "D198") (pin "1") (pinfunction "C_1") (pintype "passive"))
      (node (ref "U$199") (pin "1") (pinfunction "C_1") (pintype "bidirectional"))
    )
    (net (code "260") (name "Net-(D199-C)") (class "Default")
      (node (ref "D199") (pin "1") (pinfunction "C_1") (pintype "passive"))
      (node (ref "U$200") (pin "1") (pinfunction "C_1") (pintype "bidirectional"))
    )
    (net (code "261") (name "Net-(D200-C)") (class "Default")
      (node (ref "D200") (pin "1") (pinfunction "C_1") (pintype "passive"))
      (node (ref "U$201") (pin "1") (pinfunction "C_1") (pintype "bidirectional"))
    )
    (net (code "262") (name "Net-(D201-C)") (class "Default")
      (node (ref "D201") (pin "1") (pinfunction "C_1") (pintype "passive"))
      (node (ref "U$202") (pin "1") (pinfunction "C_1") (pintype "bidirectional"))
    )
    (net (code "263") (name "Net-(D202-C)") (class "Default")
      (node (ref "D202") (pin "1") (pinfunction "C_1") (pintype "passive"))
      (node (ref "U$203") (pin "1") (pinfunction "C_1") (pintype "bidirectional"))
    )
    (net (code "264") (name "Net-(D203-C)") (class "Default")
      (node (ref "D203") (pin "1") (pinfunction "C_1") (pintype "passive"))
      (node (ref "U$204") (pin "1") (pinfunction "C_1") (pintype "bidirectional"))
    )
    (net (code "265") (name "Net-(D204-C)") (class "Default")
      (node (ref "D204") (pin "1") (pinfunction "C_1") (pintype "passive"))
      (node (ref "U$205") (pin "1") (pinfunction "C_1") (pintype "bidirectional"))
    )
    (net (code "266") (name "Net-(D205-C)") (class "Default")
      (node (ref "D205") (pin "1") (pinfunction "C_1") (pintype "passive"))
      (node (ref "U$206") (pin "1") (pinfunction "C_1") (pintype "bidirectional"))
    )
    (net (code "267") (name "Net-(D206-C)") (class "Default")
      (node (ref "D206") (pin "1") (pinfunction "C_1") (pintype "passive"))
      (node (ref "U$207") (pin "1") (pinfunction "C_1") (pintype "bidirectional"))
    )
    (net (code "268") (name "Net-(D207-C)") (class "Default")
      (node (ref "D207") (pin "1") (pinfunction "C_1") (pintype "passive"))
      (node (ref "U$208") (pin "1") (pinfunction "C_1") (pintype "bidirectional"))
    )
    (net (code "269") (name "Net-(D208-C)") (class "Default")
      (node (ref "D208") (pin "1") (pinfunction "C_1") (pintype "passive"))
      (node (ref "U$209") (pin "1") (pinfunction "C_1") (pintype "bidirectional"))
    )
    (net (code "270") (name "Net-(D209-C)") (class "Default")
      (node (ref "D209") (pin "1") (pinfunction "C_1") (pintype "passive"))
      (node (ref "U$210") (pin "1") (pinfunction "C_1") (pintype "bidirectional"))
    )
    (net (code "271") (name "Net-(D210-C)") (class "Default")
      (node (ref "D210") (pin "1") (pinfunction "C_1") (pintype "passive"))
      (node (ref "U$211") (pin "1") (pinfunction "C_1") (pintype "bidirectional"))
    )
    (net (code "272") (name "Net-(D211-C)") (class "Default")
      (node (ref "D211") (pin "1") (pinfunction "C_1") (pintype "passive"))
      (node (ref "U$212") (pin "1") (pinfunction "C_1") (pintype "bidirectional"))
    )
    (net (code "273") (name "Net-(D212-C)") (class "Default")
      (node (ref "D212") (pin "1") (pinfunction "C_1") (pintype "passive"))
      (node (ref "U$213") (pin "1") (pinfunction "C_1") (pintype "bidirectional"))
    )
    (net (code "274") (name "Net-(D213-C)") (class "Default")
      (node (ref "D213") (pin "1") (pinfunction "C_1") (pintype "passive"))
      (node (ref "U$214") (pin "1") (pinfunction "C_1") (pintype "bidirectional"))
    )
    (net (code "275") (name "Net-(D214-C)") (class "Default")
      (node (ref "D214") (pin "1") (pinfunction "C_1") (pintype "passive"))
      (node (ref "U$215") (pin "1") (pinfunction "C_1") (pintype "bidirectional"))
    )
    (net (code "276") (name "Net-(D215-C)") (class "Default")
      (node (ref "D215") (pin "1") (pinfunction "C_1") (pintype "passive"))
      (node (ref "U$216") (pin "1") (pinfunction "C_1") (pintype "bidirectional"))
    )
    (net (code "277") (name "Net-(D216-C)") (class "Default")
      (node (ref "D216") (pin "1") (pinfunction "C_1") (pintype "passive"))
      (node (ref "U$217") (pin "1") (pinfunction "C_1") (pintype "bidirectional"))
    )
    (net (code "278") (name "Net-(D217-C)") (class "Default")
      (node (ref "D217") (pin "1") (pinfunction "C_1") (pintype "passive"))
      (node (ref "U$218") (pin "1") (pinfunction "C_1") (pintype "bidirectional"))
    )
    (net (code "279") (name "Net-(D218-C)") (class "Default")
      (node (ref "D218") (pin "1") (pinfunction "C_1") (pintype "passive"))
      (node (ref "U$219") (pin "1") (pinfunction "C_1") (pintype "bidirectional"))
    )
    (net (code "280") (name "Net-(D219-C)") (class "Default")
      (node (ref "D219") (pin "1") (pinfunction "C_1") (pintype "passive"))
      (node (ref "U$220") (pin "1") (pinfunction "C_1") (pintype "bidirectional"))
    )
    (net (code "281") (name "Net-(D220-C)") (class "Default")
      (node (ref "D220") (pin "1") (pinfunction "C_1") (pintype "passive"))
      (node (ref "U$221") (pin "1") (pinfunction "C_1") (pintype "bidirectional"))
    )
    (net (code "282") (name "Net-(D221-C)") (class "Default")
      (node (ref "D221") (pin "1") (pinfunction "C_1") (pintype "passive"))
      (node (ref "U$222") (pin "1") (pinfunction "C_1") (pintype "bidirectional"))
    )
    (net (code "283") (name "Net-(D222-C)") (class "Default")
      (node (ref "D222") (pin "1") (pinfunction "C_1") (pintype "passive"))
      (node (ref "U$223") (pin "1") (pinfunction "C_1") (pintype "bidirectional"))
    )
    (net (code "284") (name "Net-(D223-C)") (class "Default")
      (node (ref "D223") (pin "1") (pinfunction "C_1") (pintype "passive"))
      (node (ref "U$224") (pin "1") (pinfunction "C_1") (pintype "bidirectional"))
    )
    (net (code "285") (name "Net-(D224-C)") (class "Default")
      (node (ref "D224") (pin "1") (pinfunction "C_1") (pintype "passive"))
      (node (ref "U$225") (pin "1") (pinfunction "C_1") (pintype "bidirectional"))
    )
    (net (code "286") (name "Net-(D225-C)") (class "Default")
      (node (ref "D225") (pin "1") (pinfunction "C_1") (pintype "passive"))
      (node (ref "U$226") (pin "1") (pinfunction "C_1") (pintype "bidirectional"))
    )
    (net (code "287") (name "Net-(D226-C)") (class "Default")
      (node (ref "D226") (pin "1") (pinfunction "C_1") (pintype "passive"))
      (node (ref "U$227") (pin "1") (pinfunction "C_1") (pintype "bidirectional"))
    )
    (net (code "288") (name "Net-(D227-C)") (class "Default")
      (node (ref "D227") (pin "1") (pinfunction "C_1") (pintype "passive"))
      (node (ref "U$228") (pin "1") (pinfunction "C_1") (pintype "bidirectional"))
    )
    (net (code "289") (name "Net-(D228-C)") (class "Default")
      (node (ref "D228") (pin "1") (pinfunction "C_1") (pintype "passive"))
      (node (ref "U$229") (pin "1") (pinfunction "C_1") (pintype "bidirectional"))
    )
    (net (code "290") (name "Net-(D229-C)") (class "Default")
      (node (ref "D229") (pin "1") (pinfunction "C_1") (pintype "passive"))
      (node (ref "U$230") (pin "1") (pinfunction "C_1") (pintype "bidirectional"))
    )
    (net (code "291") (name "Net-(D230-C)") (class "Default")
      (node (ref "D230") (pin "1") (pinfunction "C_1") (pintype "passive"))
      (node (ref "U$231") (pin "1") (pinfunction "C_1") (pintype "bidirectional"))
    )
    (net (code "292") (name "Net-(D231-C)") (class "Default")
      (node (ref "D231") (pin "1") (pinfunction "C_1") (pintype "passive"))
      (node (ref "U$232") (pin "1") (pinfunction "C_1") (pintype "bidirectional"))
    )
    (net (code "293") (name "Net-(D232-C)") (class "Default")
      (node (ref "D232") (pin "1") (pinfunction "C_1") (pintype "passive"))
      (node (ref "U$233") (pin "1") (pinfunction "C_1") (pintype "bidirectional"))
    )
    (net (code "294") (name "Net-(D233-C)") (class "Default")
      (node (ref "D233") (pin "1") (pinfunction "C_1") (pintype "passive"))
      (node (ref "U$234") (pin "1") (pinfunction "C_1") (pintype "bidirectional"))
    )
    (net (code "295") (name "Net-(D234-C)") (class "Default")
      (node (ref "D234") (pin "1") (pinfunction "C_1") (pintype "passive"))
      (node (ref "U$235") (pin "1") (pinfunction "C_1") (pintype "bidirectional"))
    )
    (net (code "296") (name "Net-(D235-C)") (class "Default")
      (node (ref "D235") (pin "1") (pinfunction "C_1") (pintype "passive"))
      (node (ref "U$236") (pin "1") (pinfunction "C_1") (pintype "bidirectional"))
    )
    (net (code "297") (name "Net-(D236-C)") (class "Default")
      (node (ref "D236") (pin "1") (pinfunction "C_1") (pintype "passive"))
      (node (ref "U$237") (pin "1") (pinfunction "C_1") (pintype "bidirectional"))
    )
    (net (code "298") (name "Net-(D237-C)") (class "Default")
      (node (ref "D237") (pin "1") (pinfunction "C_1") (pintype "passive"))
      (node (ref "U$238") (pin "1") (pinfunction "C_1") (pintype "bidirectional"))
    )
    (net (code "299") (name "Net-(D238-C)") (class "Default")
      (node (ref "D238") (pin "1") (pinfunction "C_1") (pintype "passive"))
      (node (ref "U$239") (pin "1") (pinfunction "C_1") (pintype "bidirectional"))
    )
    (net (code "300") (name "Net-(D239-C)") (class "Default")
      (node (ref "D239") (pin "1") (pinfunction "C_1") (pintype "passive"))
      (node (ref "U$240") (pin "1") (pinfunction "C_1") (pintype "bidirectional"))
    )
    (net (code "301") (name "Net-(D240-C)") (class "Default")
      (node (ref "D240") (pin "1") (pinfunction "C_1") (pintype "passive"))
      (node (ref "U$241") (pin "1") (pinfunction "C_1") (pintype "bidirectional"))
    )
    (net (code "302") (name "Net-(D241-C)") (class "Default")
      (node (ref "D241") (pin "1") (pinfunction "C_1") (pintype "passive"))
      (node (ref "U$242") (pin "1") (pinfunction "C_1") (pintype "bidirectional"))
    )
    (net (code "303") (name "Net-(D242-C)") (class "Default")
      (node (ref "D242") (pin "1") (pinfunction "C_1") (pintype "passive"))
      (node (ref "U$243") (pin "1") (pinfunction "C_1") (pintype "bidirectional"))
    )
    (net (code "304") (name "Net-(D243-C)") (class "Default")
      (node (ref "D243") (pin "1") (pinfunction "C_1") (pintype "passive"))
      (node (ref "U$244") (pin "1") (pinfunction "C_1") (pintype "bidirectional"))
    )
    (net (code "305") (name "Net-(D244-C)") (class "Default")
      (node (ref "D244") (pin "1") (pinfunction "C_1") (pintype "passive"))
      (node (ref "U$245") (pin "1") (pinfunction "C_1") (pintype "bidirectional"))
    )
    (net (code "306") (name "Net-(D245-C)") (class "Default")
      (node (ref "D245") (pin "1") (pinfunction "C_1") (pintype "passive"))
      (node (ref "U$246") (pin "1") (pinfunction "C_1") (pintype "bidirectional"))
    )
    (net (code "307") (name "Net-(D246-C)") (class "Default")
      (node (ref "D246") (pin "1") (pinfunction "C_1") (pintype "passive"))
      (node (ref "U$247") (pin "1") (pinfunction "C_1") (pintype "bidirectional"))
    )
    (net (code "308") (name "Net-(D247-C)") (class "Default")
      (node (ref "D247") (pin "1") (pinfunction "C_1") (pintype "passive"))
      (node (ref "U$248") (pin "1") (pinfunction "C_1") (pintype "bidirectional"))
    )
    (net (code "309") (name "Net-(D248-C)") (class "Default")
      (node (ref "D248") (pin "1") (pinfunction "C_1") (pintype "passive"))
      (node (ref "U$249") (pin "1") (pinfunction "C_1") (pintype "bidirectional"))
    )
    (net (code "310") (name "Net-(D249-C)") (class "Default")
      (node (ref "D249") (pin "1") (pinfunction "C_1") (pintype "passive"))
      (node (ref "U$250") (pin "1") (pinfunction "C_1") (pintype "bidirectional"))
    )
    (net (code "311") (name "Net-(D250-C)") (class "Default")
      (node (ref "D250") (pin "1") (pinfunction "C_1") (pintype "passive"))
      (node (ref "U$251") (pin "1") (pinfunction "C_1") (pintype "bidirectional"))
    )
    (net (code "312") (name "Net-(D251-C)") (class "Default")
      (node (ref "D251") (pin "1") (pinfunction "C_1") (pintype "passive"))
      (node (ref "U$252") (pin "1") (pinfunction "C_1") (pintype "bidirectional"))
    )
    (net (code "313") (name "Net-(D252-C)") (class "Default")
      (node (ref "D252") (pin "1") (pinfunction "C_1") (pintype "passive"))
      (node (ref "U$253") (pin "1") (pinfunction "C_1") (pintype "bidirectional"))
    )
    (net (code "314") (name "Net-(D253-C)") (class "Default")
      (node (ref "D253") (pin "1") (pinfunction "C_1") (pintype "passive"))
      (node (ref "U$254") (pin "1") (pinfunction "C_1") (pintype "bidirectional"))
    )
    (net (code "315") (name "Net-(D254-C)") (class "Default")
      (node (ref "D254") (pin "1") (pinfunction "C_1") (pintype "passive"))
      (node (ref "U$255") (pin "1") (pinfunction "C_1") (pintype "bidirectional"))
    )
    (net (code "316") (name "Net-(D255-C)") (class "Default")
      (node (ref "D255") (pin "1") (pinfunction "C_1") (pintype "passive"))
      (node (ref "U$256") (pin "1") (pinfunction "C_1") (pintype "bidirectional"))
    )
    (net (code "317") (name "Net-(D256-C)") (class "Default")
      (node (ref "D256") (pin "1") (pinfunction "C_1") (pintype "passive"))
      (node (ref "U$257") (pin "1") (pinfunction "C_1") (pintype "bidirectional"))
    )
    (net (code "318") (name "Net-(IC1A--IN1)") (class "Default")
      (node (ref "IC1") (pin "2") (pinfunction "-IN1_2") (pintype "input"))
      (node (ref "U$5") (pin "1") (pinfunction "COM_1") (pintype "bidirectional"))
    )
    (net (code "319") (name "Net-(Q1-B)") (class "Default")
      (node (ref "Q1") (pin "1") (pinfunction "B_1") (pintype "passive"))
      (node (ref "R19") (pin "2") (pinfunction "2_2") (pintype "passive"))
    )
    (net (code "320") (name "Net-(Q2-B)") (class "Default")
      (node (ref "Q2") (pin "1") (pinfunction "B_1") (pintype "passive"))
      (node (ref "R20") (pin "2") (pinfunction "2_2") (pintype "passive"))
    )
    (net (code "321") (name "Net-(Q3-B)") (class "Default")
      (node (ref "Q3") (pin "1") (pinfunction "B_1") (pintype "passive"))
      (node (ref "R21") (pin "2") (pinfunction "2_2") (pintype "passive"))
    )
    (net (code "322") (name "Net-(Q4-B)") (class "Default")
      (node (ref "Q4") (pin "1") (pinfunction "B_1") (pintype "passive"))
      (node (ref "R22") (pin "2") (pinfunction "2_2") (pintype "passive"))
    )
    (net (code "323") (name "Net-(Q5-B)") (class "Default")
      (node (ref "Q5") (pin "1") (pinfunction "B_1") (pintype "passive"))
      (node (ref "R23") (pin "2") (pinfunction "2_2") (pintype "passive"))
    )
    (net (code "324") (name "Net-(Q6-B)") (class "Default")
      (node (ref "Q6") (pin "1") (pinfunction "B_1") (pintype "passive"))
      (node (ref "R24") (pin "2") (pinfunction "2_2") (pintype "passive"))
    )
    (net (code "325") (name "Net-(Q7-B)") (class "Default")
      (node (ref "Q7") (pin "1") (pinfunction "B_1") (pintype "passive"))
      (node (ref "R25") (pin "2") (pinfunction "2_2") (pintype "passive"))
    )
    (net (code "326") (name "Net-(Q8-B)") (class "Default")
      (node (ref "Q8") (pin "1") (pinfunction "B_1") (pintype "passive"))
      (node (ref "R26") (pin "2") (pinfunction "2_2") (pintype "passive"))
    )
    (net (code "327") (name "Net-(Q9-B)") (class "Default")
      (node (ref "Q9") (pin "1") (pinfunction "B_1") (pintype "passive"))
      (node (ref "R27") (pin "2") (pinfunction "2_2") (pintype "passive"))
    )
    (net (code "328") (name "Net-(Q10-B)") (class "Default")
      (node (ref "Q10") (pin "1") (pinfunction "B_1") (pintype "passive"))
      (node (ref "R28") (pin "2") (pinfunction "2_2") (pintype "passive"))
    )
    (net (code "329") (name "Net-(Q11-B)") (class "Default")
      (node (ref "Q11") (pin "1") (pinfunction "B_1") (pintype "passive"))
      (node (ref "R29") (pin "2") (pinfunction "2_2") (pintype "passive"))
    )
    (net (code "330") (name "Net-(Q12-B)") (class "Default")
      (node (ref "Q12") (pin "1") (pinfunction "B_1") (pintype "passive"))
      (node (ref "R30") (pin "2") (pinfunction "2_2") (pintype "passive"))
    )
    (net (code "331") (name "Net-(Q13-B)") (class "Default")
      (node (ref "Q13") (pin "1") (pinfunction "B_1") (pintype "passive"))
      (node (ref "R31") (pin "2") (pinfunction "2_2") (pintype "passive"))
    )
    (net (code "332") (name "Net-(Q14-B)") (class "Default")
      (node (ref "Q14") (pin "1") (pinfunction "B_1") (pintype "passive"))
      (node (ref "R32") (pin "2") (pinfunction "2_2") (pintype "passive"))
    )
    (net (code "333") (name "Net-(Q15-B)") (class "Default")
      (node (ref "Q15") (pin "1") (pinfunction "B_1") (pintype "passive"))
      (node (ref "R33") (pin "2") (pinfunction "2_2") (pintype "passive"))
    )
    (net (code "334") (name "Net-(Q16-B)") (class "Default")
      (node (ref "Q16") (pin "1") (pinfunction "B_1") (pintype "passive"))
      (node (ref "R34") (pin "2") (pinfunction "2_2") (pintype "passive"))
    )
    (net (code "335") (name "VCC") (class "Default")
      (node (ref "C1") (pin "A") (pinfunction "+_A") (pintype "passive"))
      (node (ref "C2") (pin "A") (pinfunction "+_A") (pintype "passive"))
      (node (ref "C4") (pin "A") (pinfunction "+_A") (pintype "passive"))
      (node (ref "IC1") (pin "8") (pinfunction "+V_8") (pintype "power_in"))
      (node (ref "IC2") (pin "24") (pinfunction "VCC_24") (pintype "power_in"))
      (node (ref "Q1") (pin "2") (pinfunction "E_2") (pintype "passive"))
      (node (ref "Q10") (pin "2") (pinfunction "E_2") (pintype "passive"))
      (node (ref "Q11") (pin "2") (pinfunction "E_2") (pintype "passive"))
      (node (ref "Q12") (pin "2") (pinfunction "E_2") (pintype "passive"))
      (node (ref "Q13") (pin "2") (pinfunction "E_2") (pintype "passive"))
      (node (ref "Q14") (pin "2") (pinfunction "E_2") (pintype "passive"))
      (node (ref "Q15") (pin "2") (pinfunction "E_2") (pintype "passive"))
      (node (ref "Q16") (pin "2") (pinfunction "E_2") (pintype "passive"))
      (node (ref "Q2") (pin "2") (pinfunction "E_2") (pintype "passive"))
      (node (ref "Q3") (pin "2") (pinfunction "E_2") (pintype "passive"))
      (node (ref "Q4") (pin "2") (pinfunction "E_2") (pintype "passive"))
      (node (ref "Q5") (pin "2") (pinfunction "E_2") (pintype "passive"))
      (node (ref "Q6") (pin "2") (pinfunction "E_2") (pintype "passive"))
      (node (ref "Q7") (pin "2") (pinfunction "E_2") (pintype "passive"))
      (node (ref "Q8") (pin "2") (pinfunction "E_2") (pintype "passive"))
      (node (ref "Q9") (pin "2") (pinfunction "E_2") (pintype "passive"))
      (node (ref "R18") (pin "2") (pinfunction "2_2") (pintype "passive"))
      (node (ref "U$5") (pin "24") (pinfunction "VCC_24") (pintype "bidirectional"))
    )
    (net (code "336") (name "unconnected-(IC2A-G1-Pad18)") (class "Default")
      (node (ref "IC2") (pin "18") (pinfunction "G1_18") (pintype "input"))
    )
    (net (code "337") (name "unconnected-(IC2A-G2-Pad19)") (class "Default")
      (node (ref "IC2") (pin "19") (pinfunction "G2_19") (pintype "input"))
    )
  )
)
